# Titan_Servo_v1p01c_r.net
KiCad netlist of a schematic drawn in EAGLE
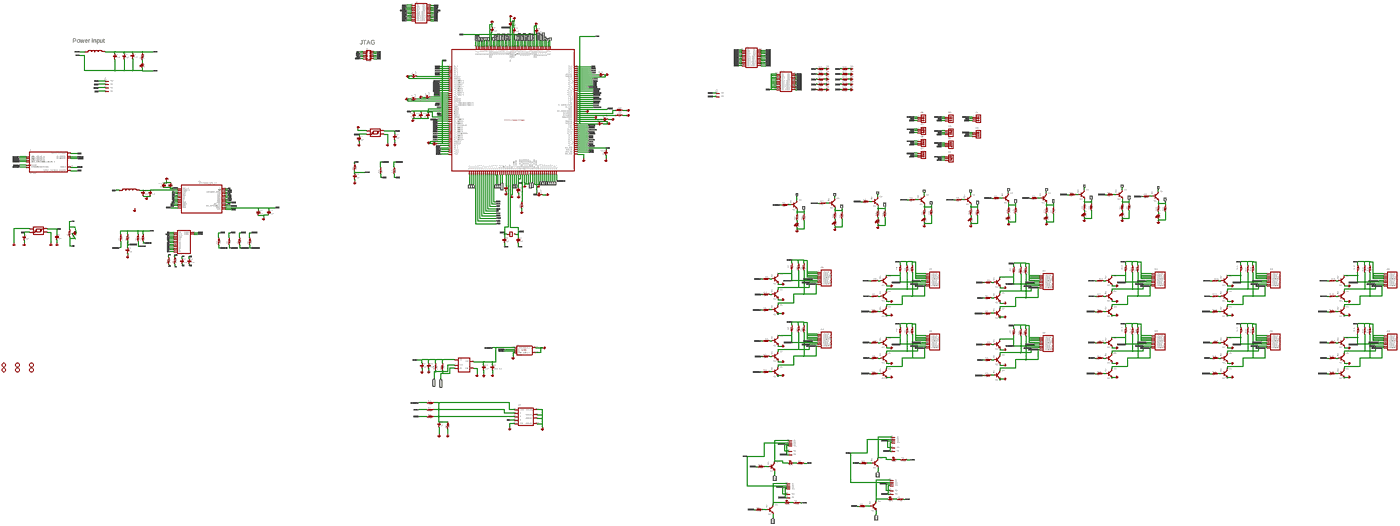
[diagram p0: schematic, sheet 1, overview]
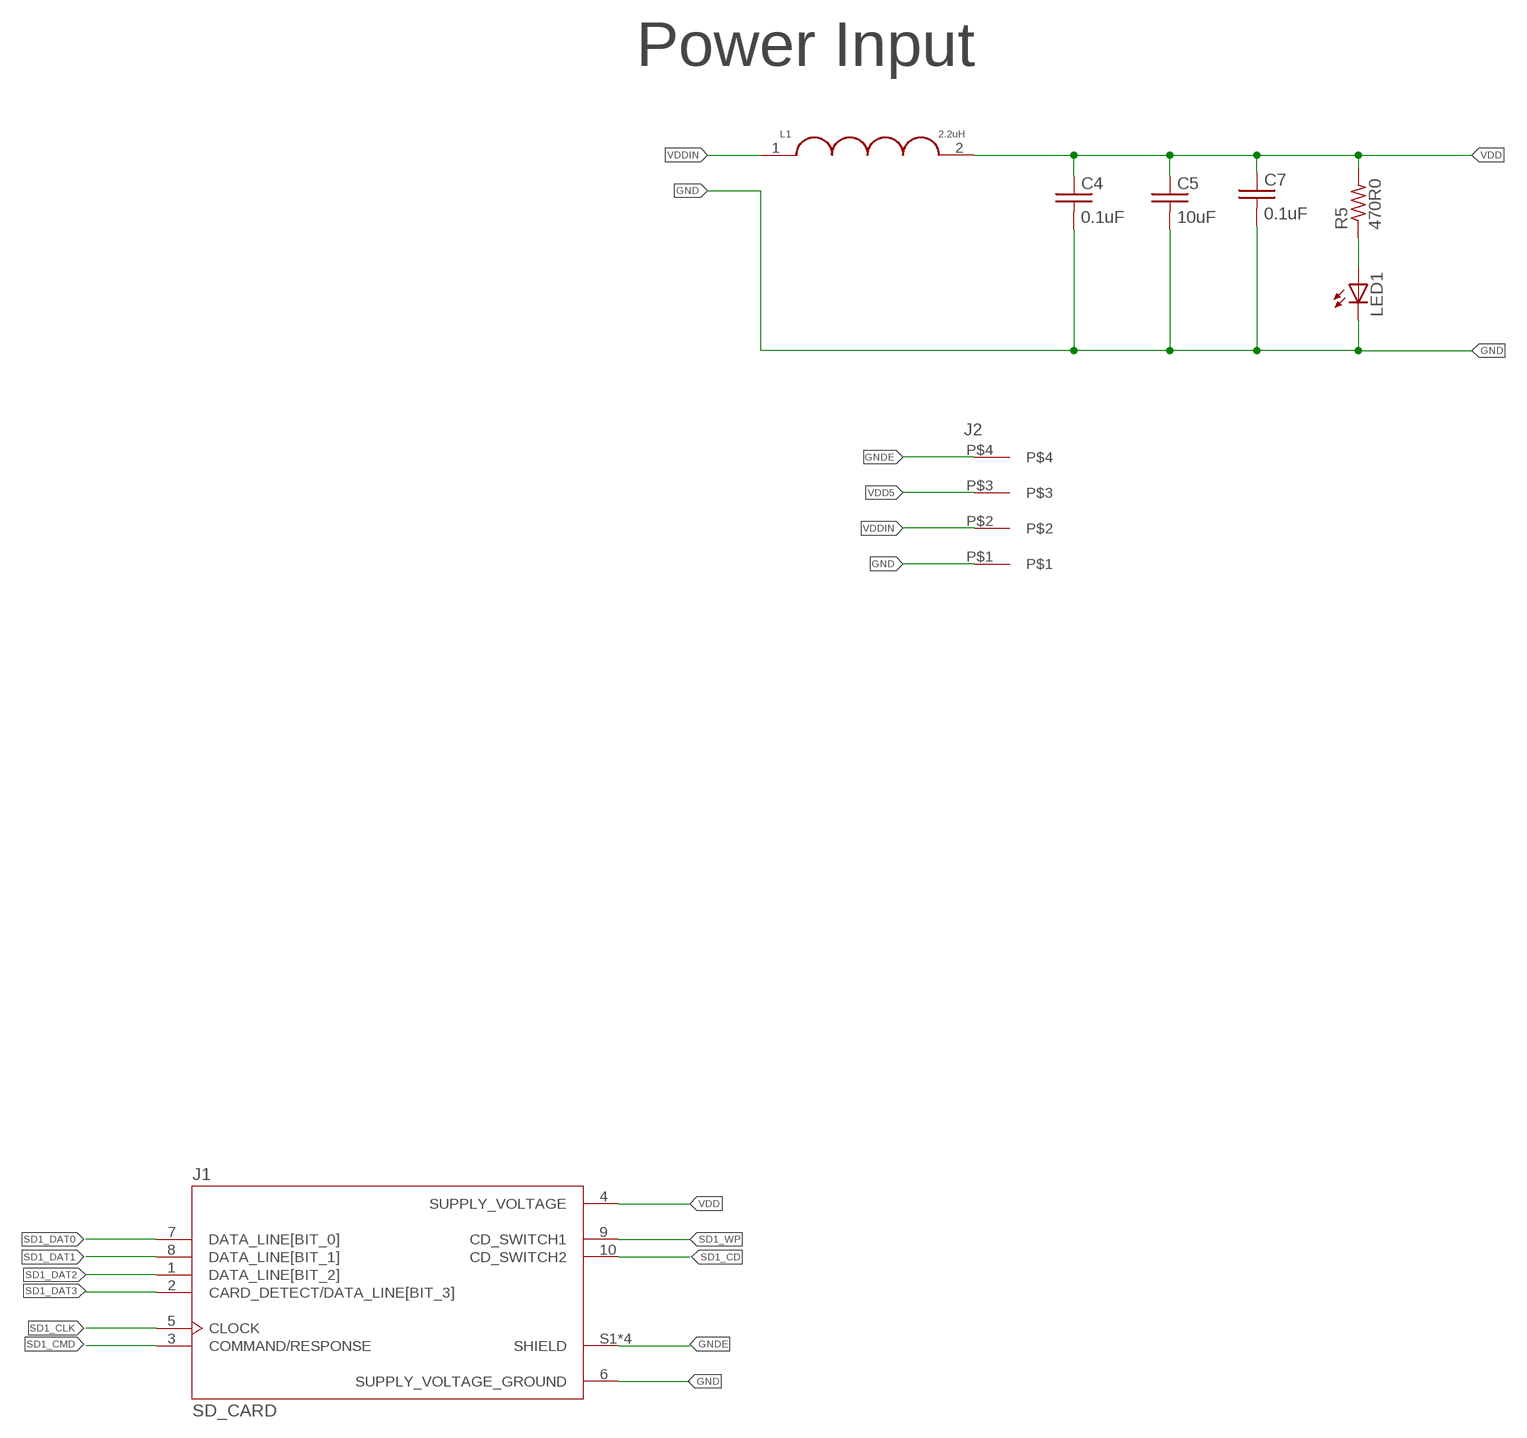
[diagram p1: schematic, sheet 1, part 1 of 9]
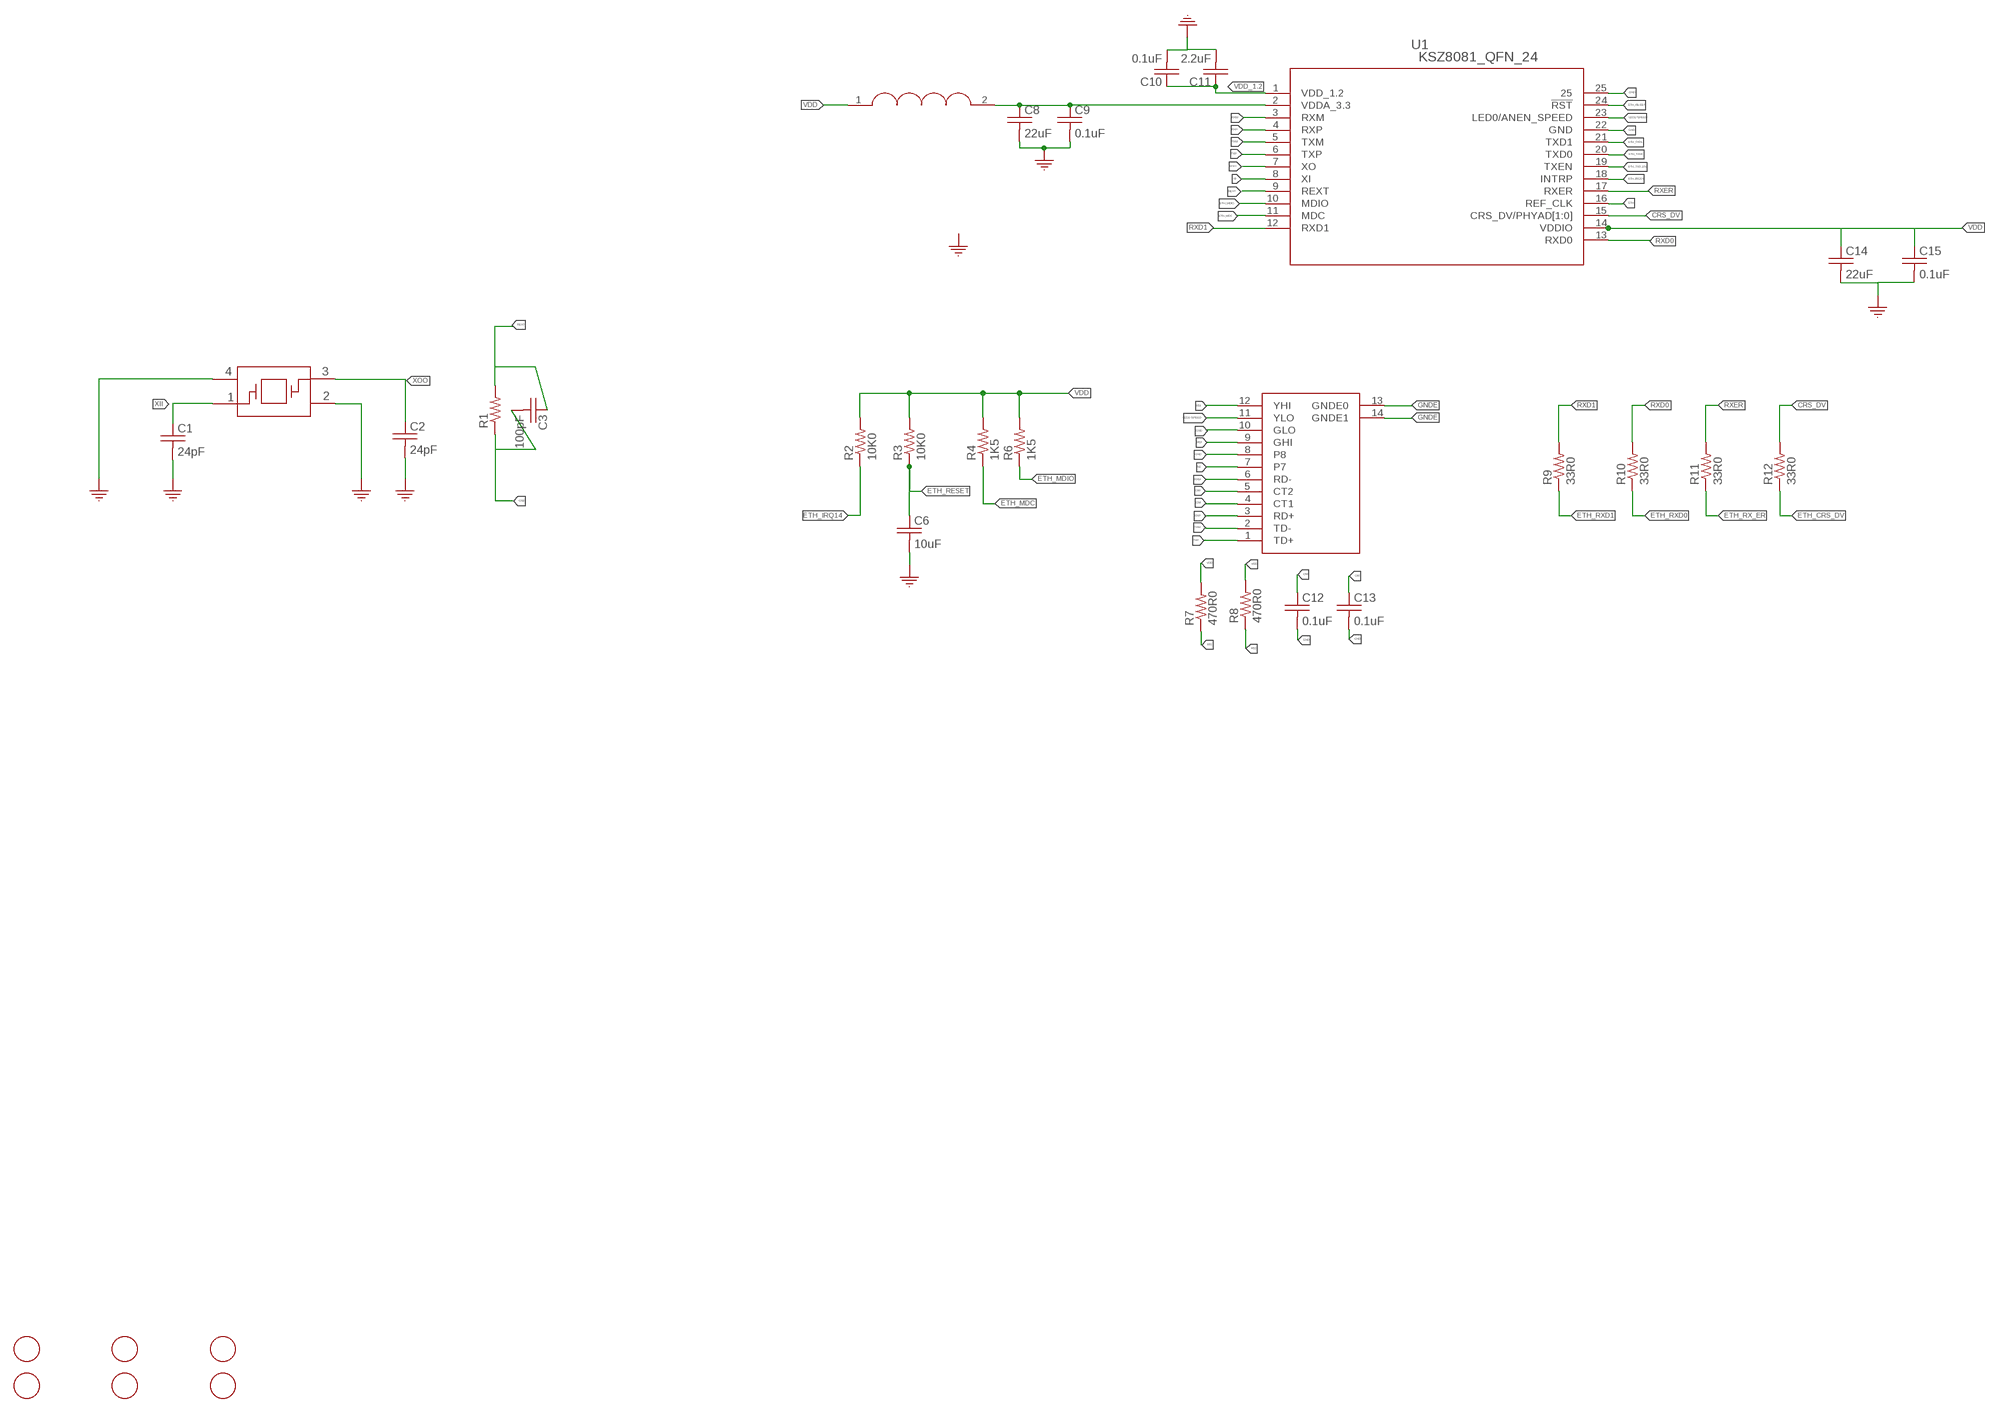
[diagram p2: schematic, sheet 1, part 2 of 9]
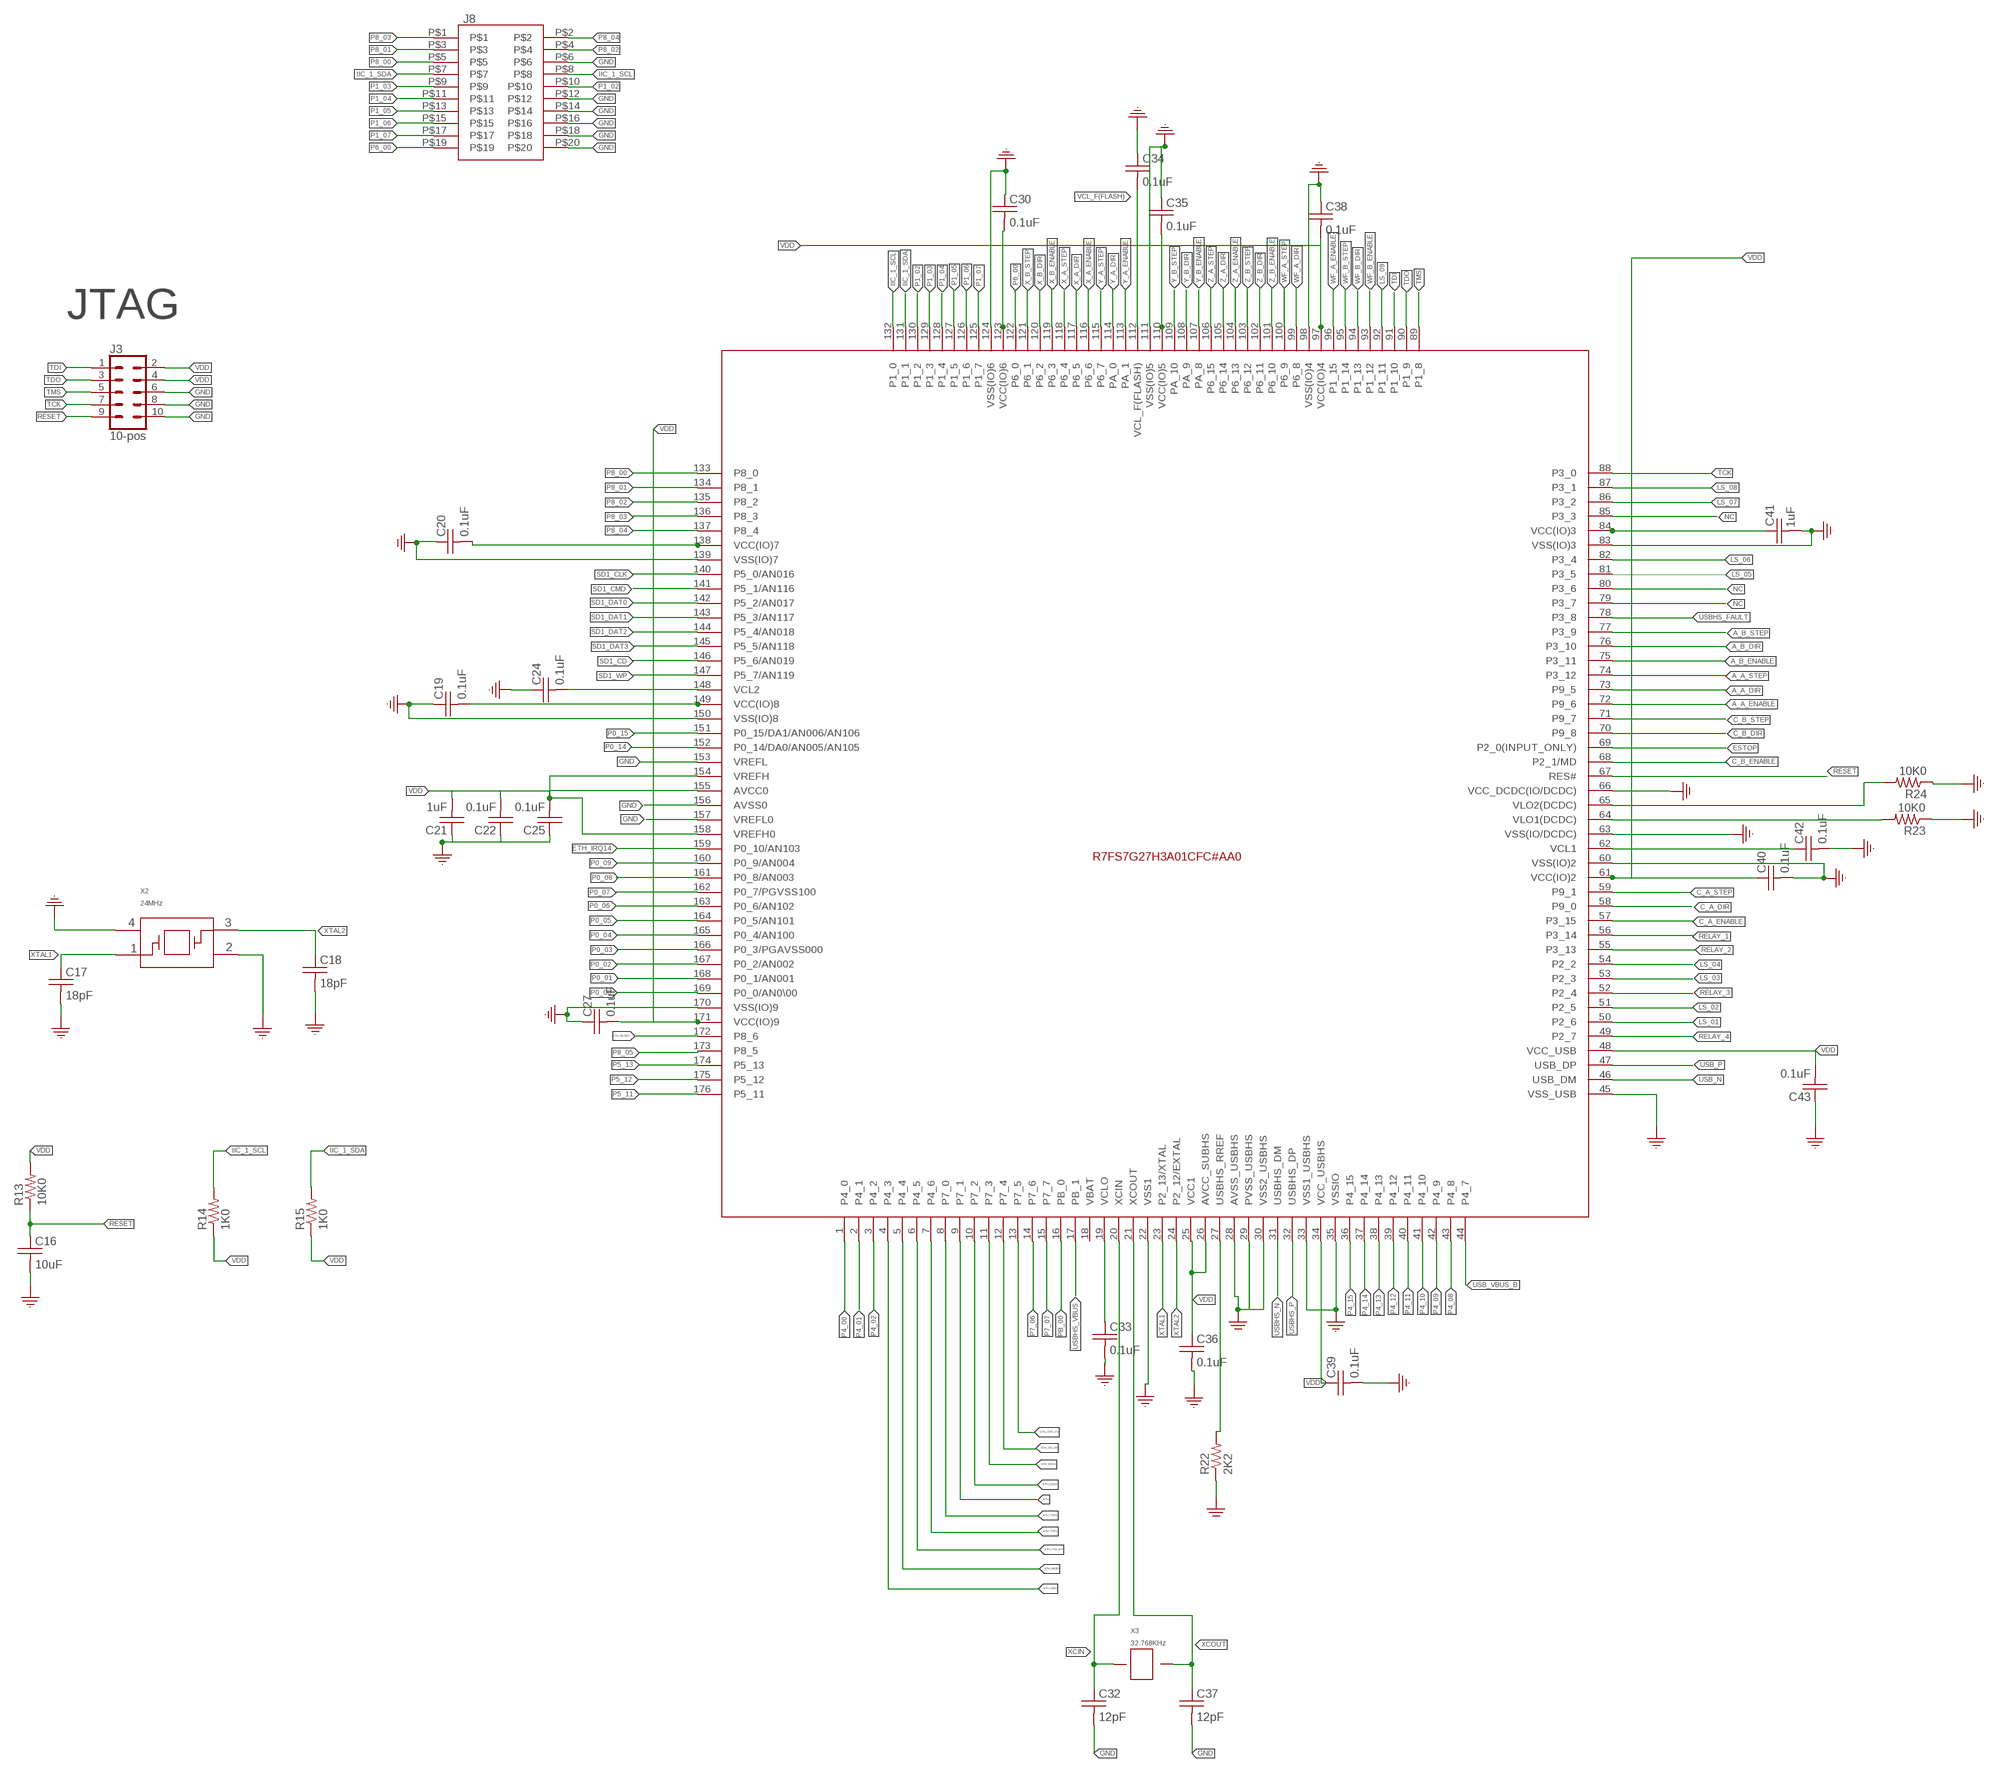
[diagram p3: schematic, sheet 1, part 3 of 9]
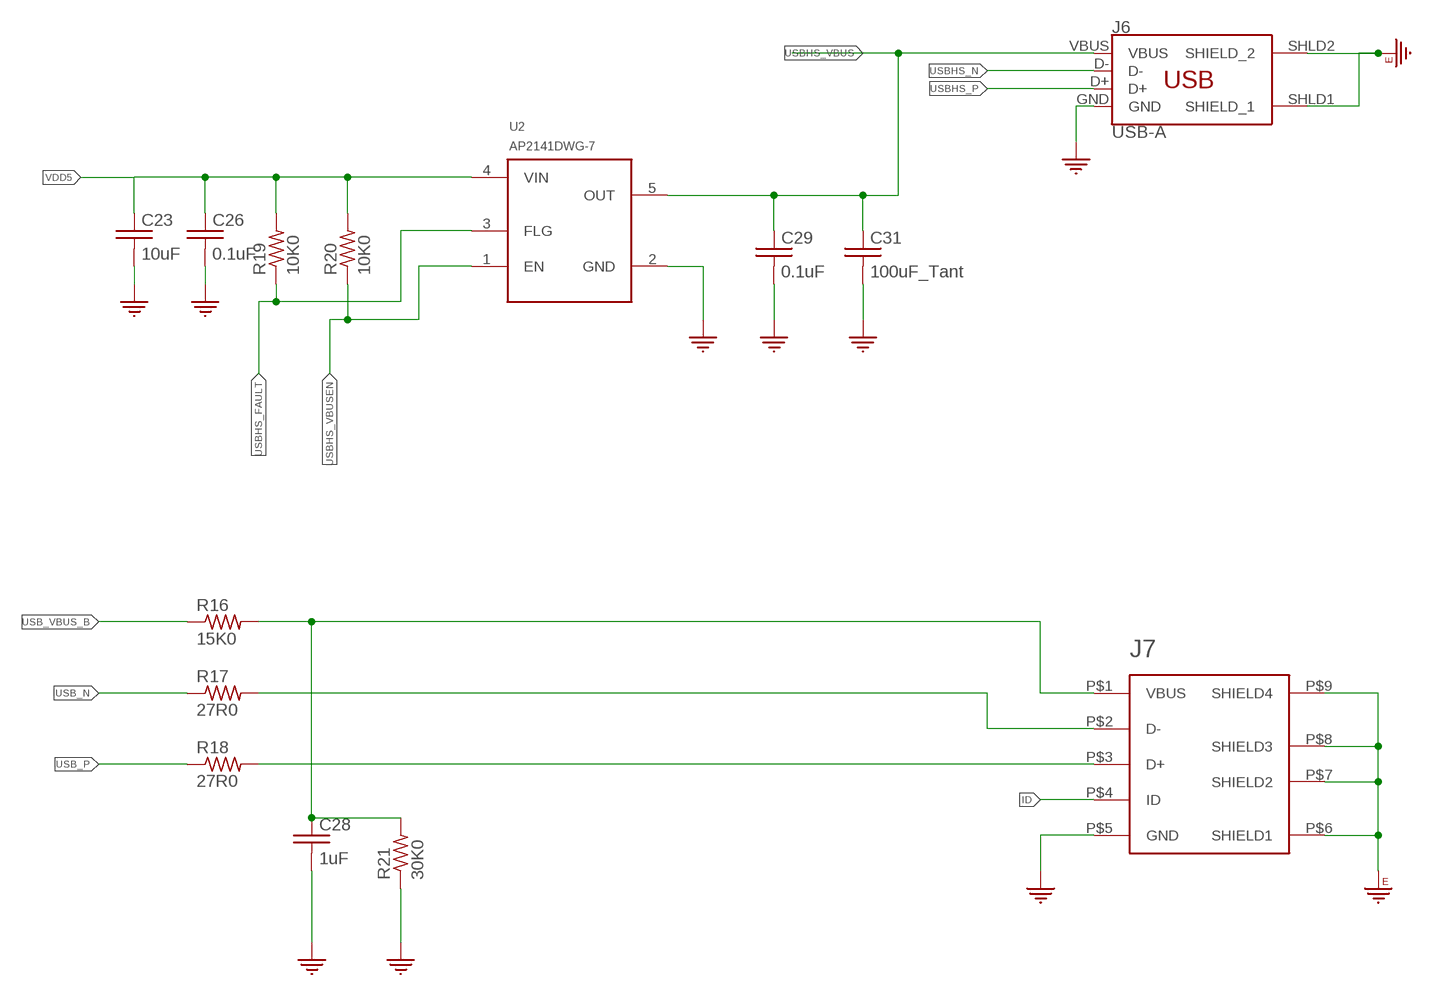
[diagram p4: schematic, sheet 1, part 4 of 9]
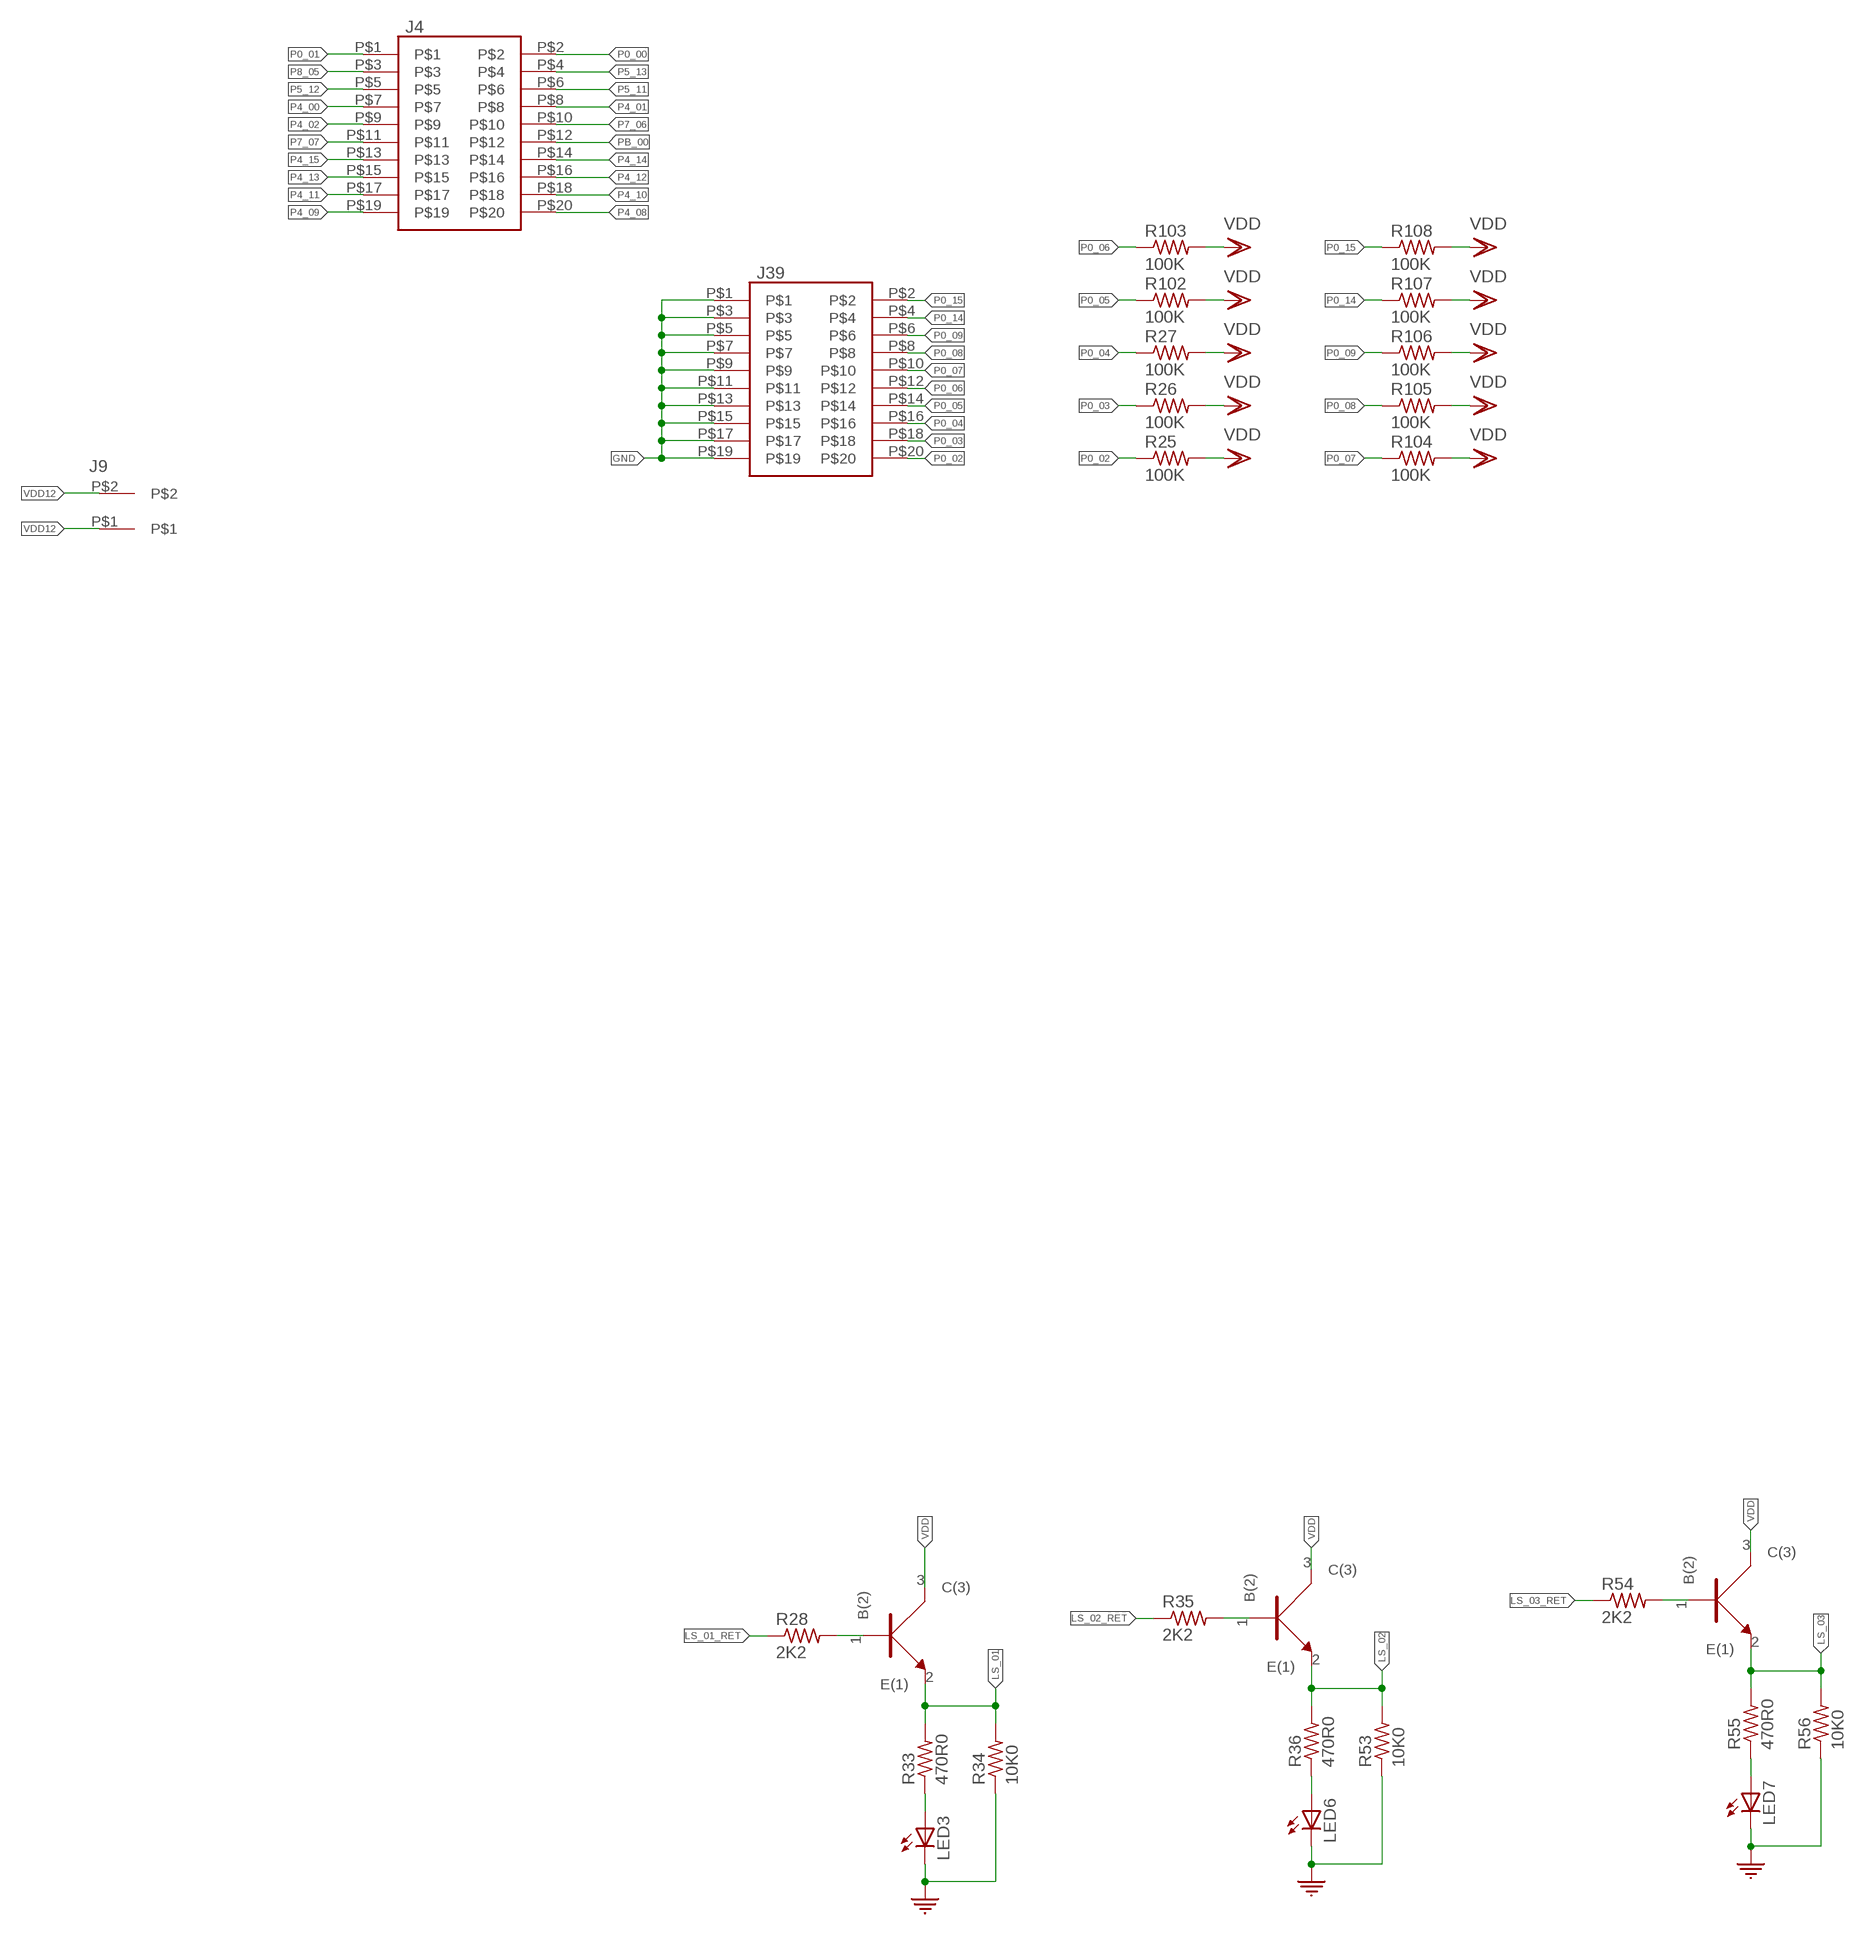
[diagram p5: schematic, sheet 1, part 5 of 9]
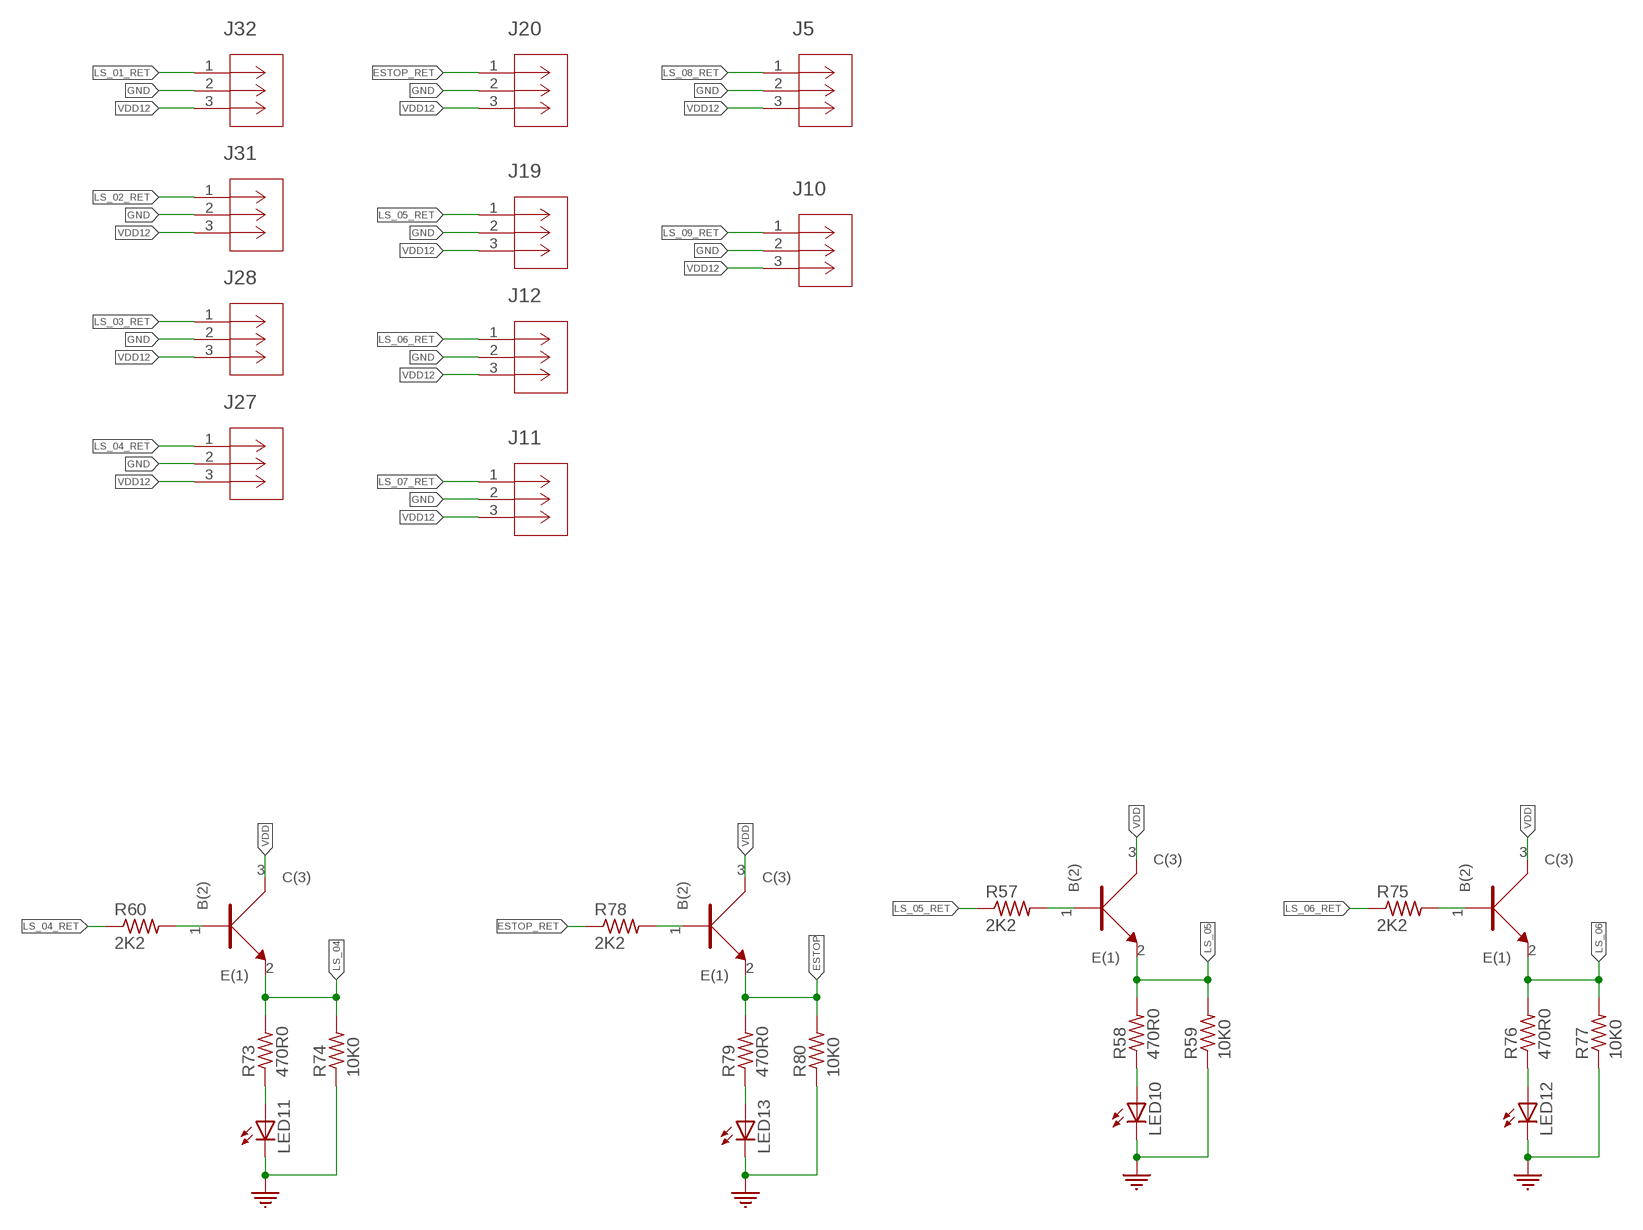
[diagram p6: schematic, sheet 1, part 6 of 9]
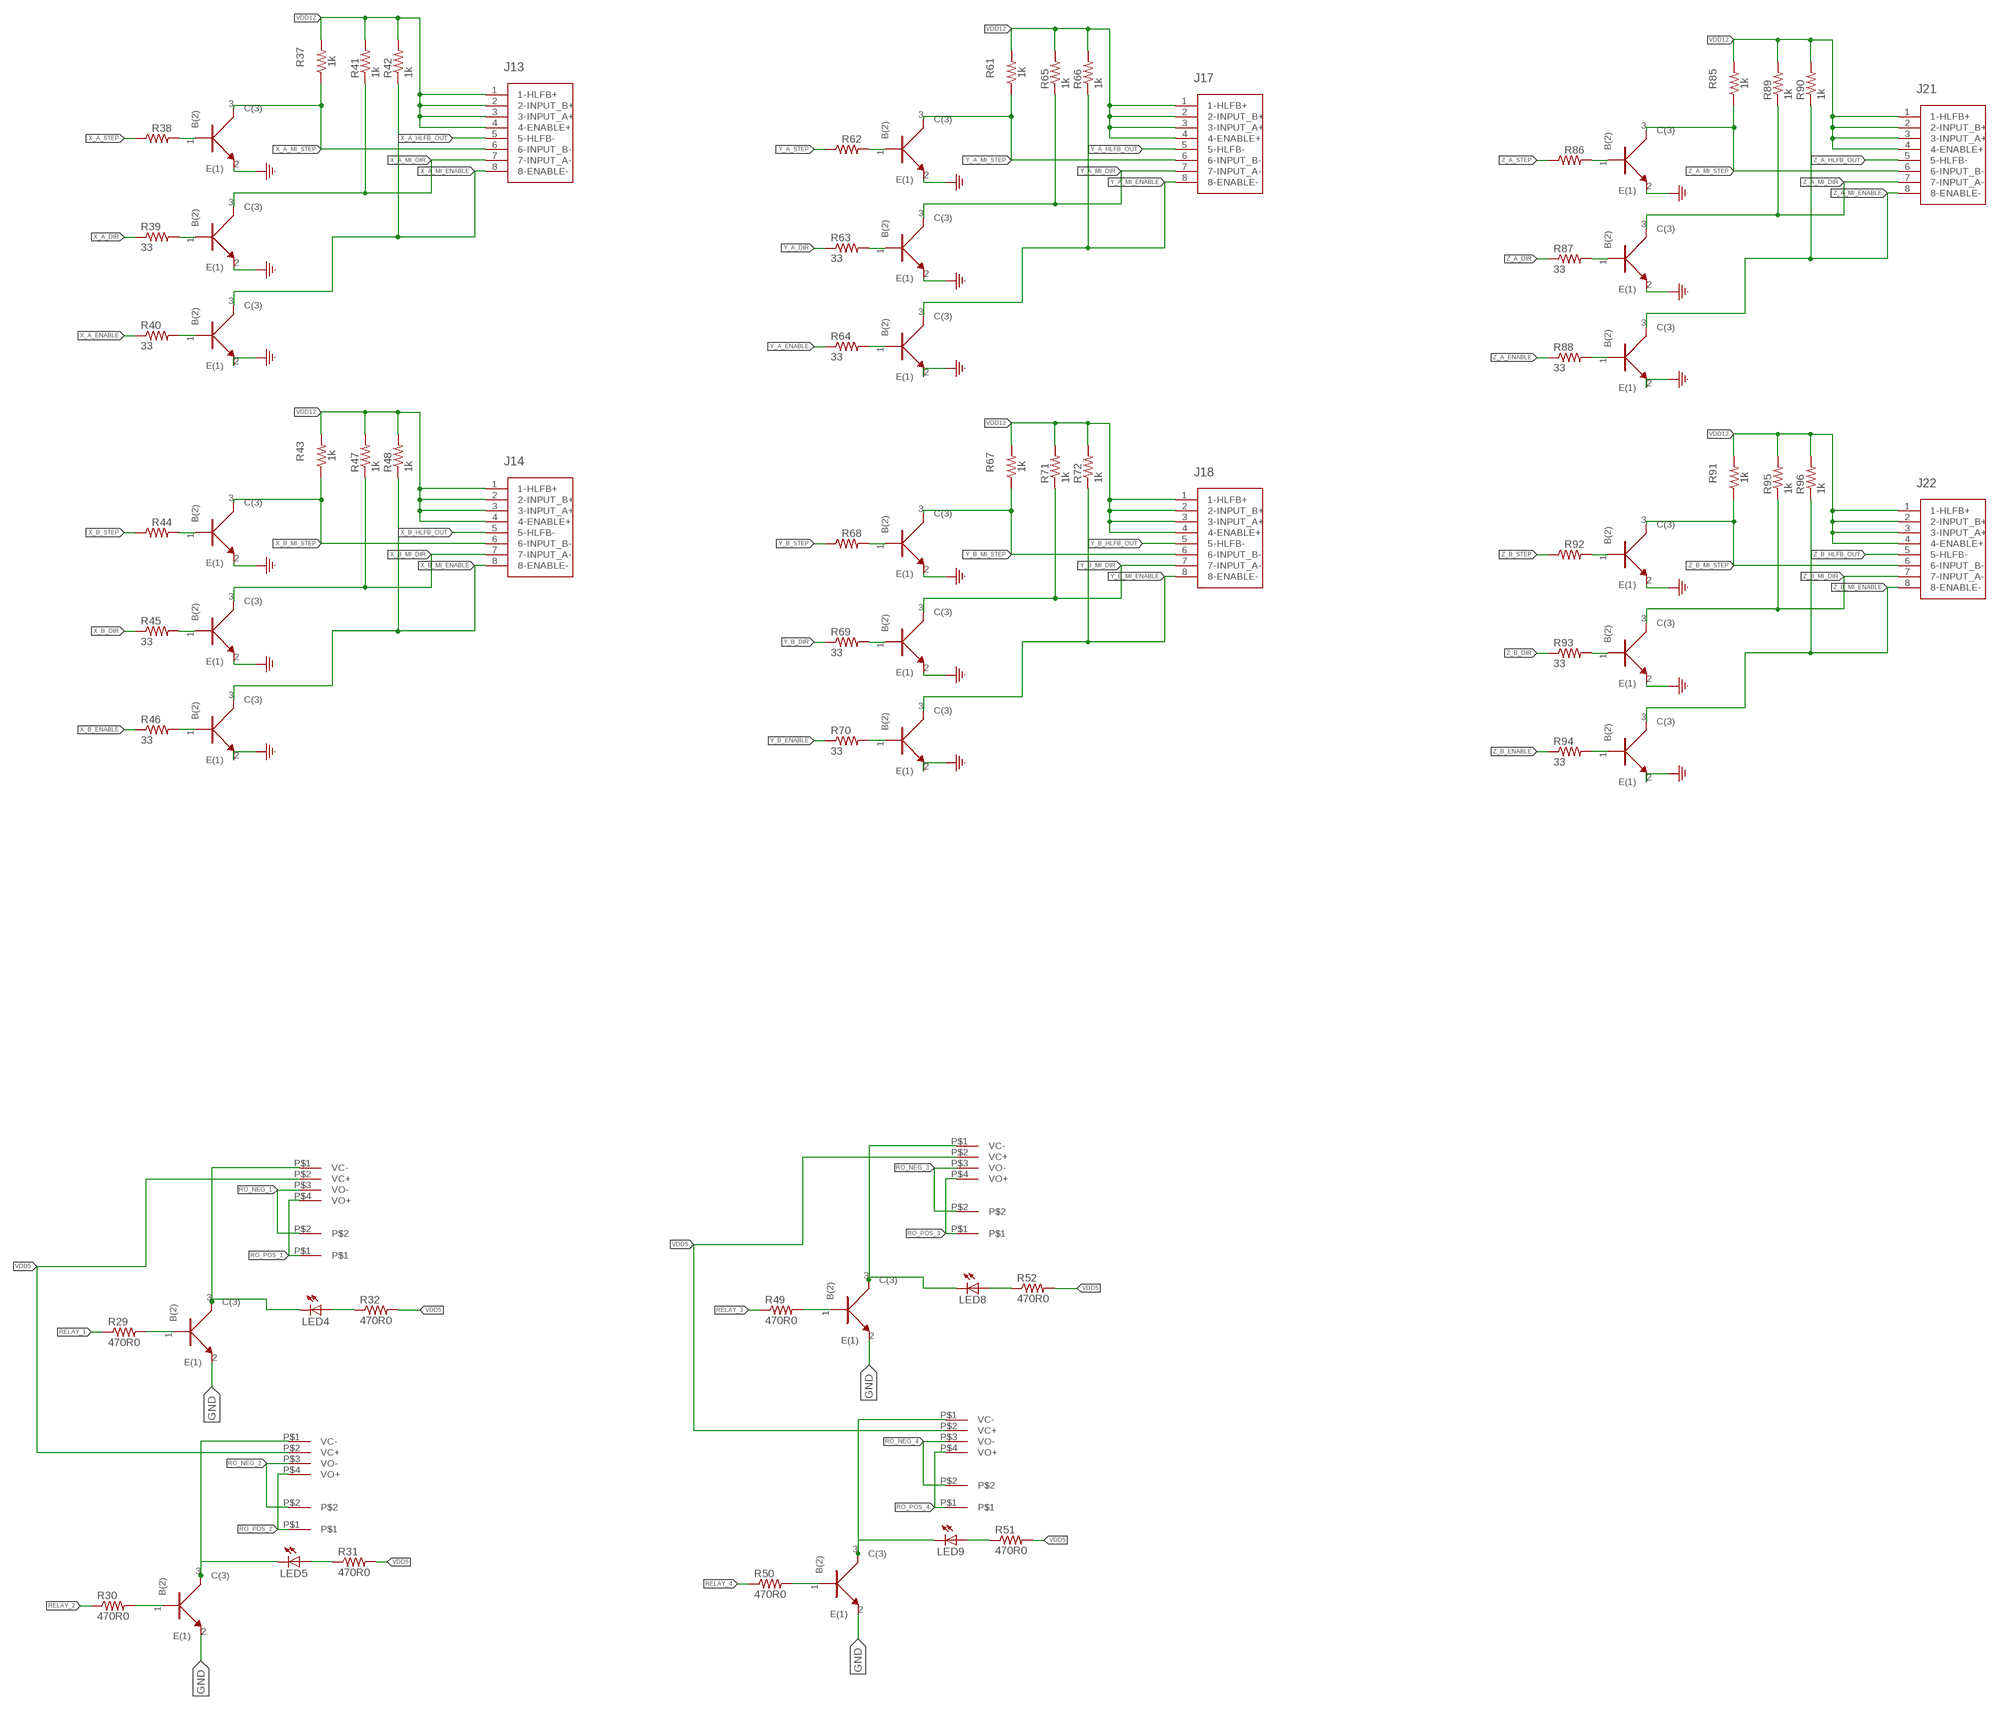
[diagram p7: schematic, sheet 1, part 7 of 9]
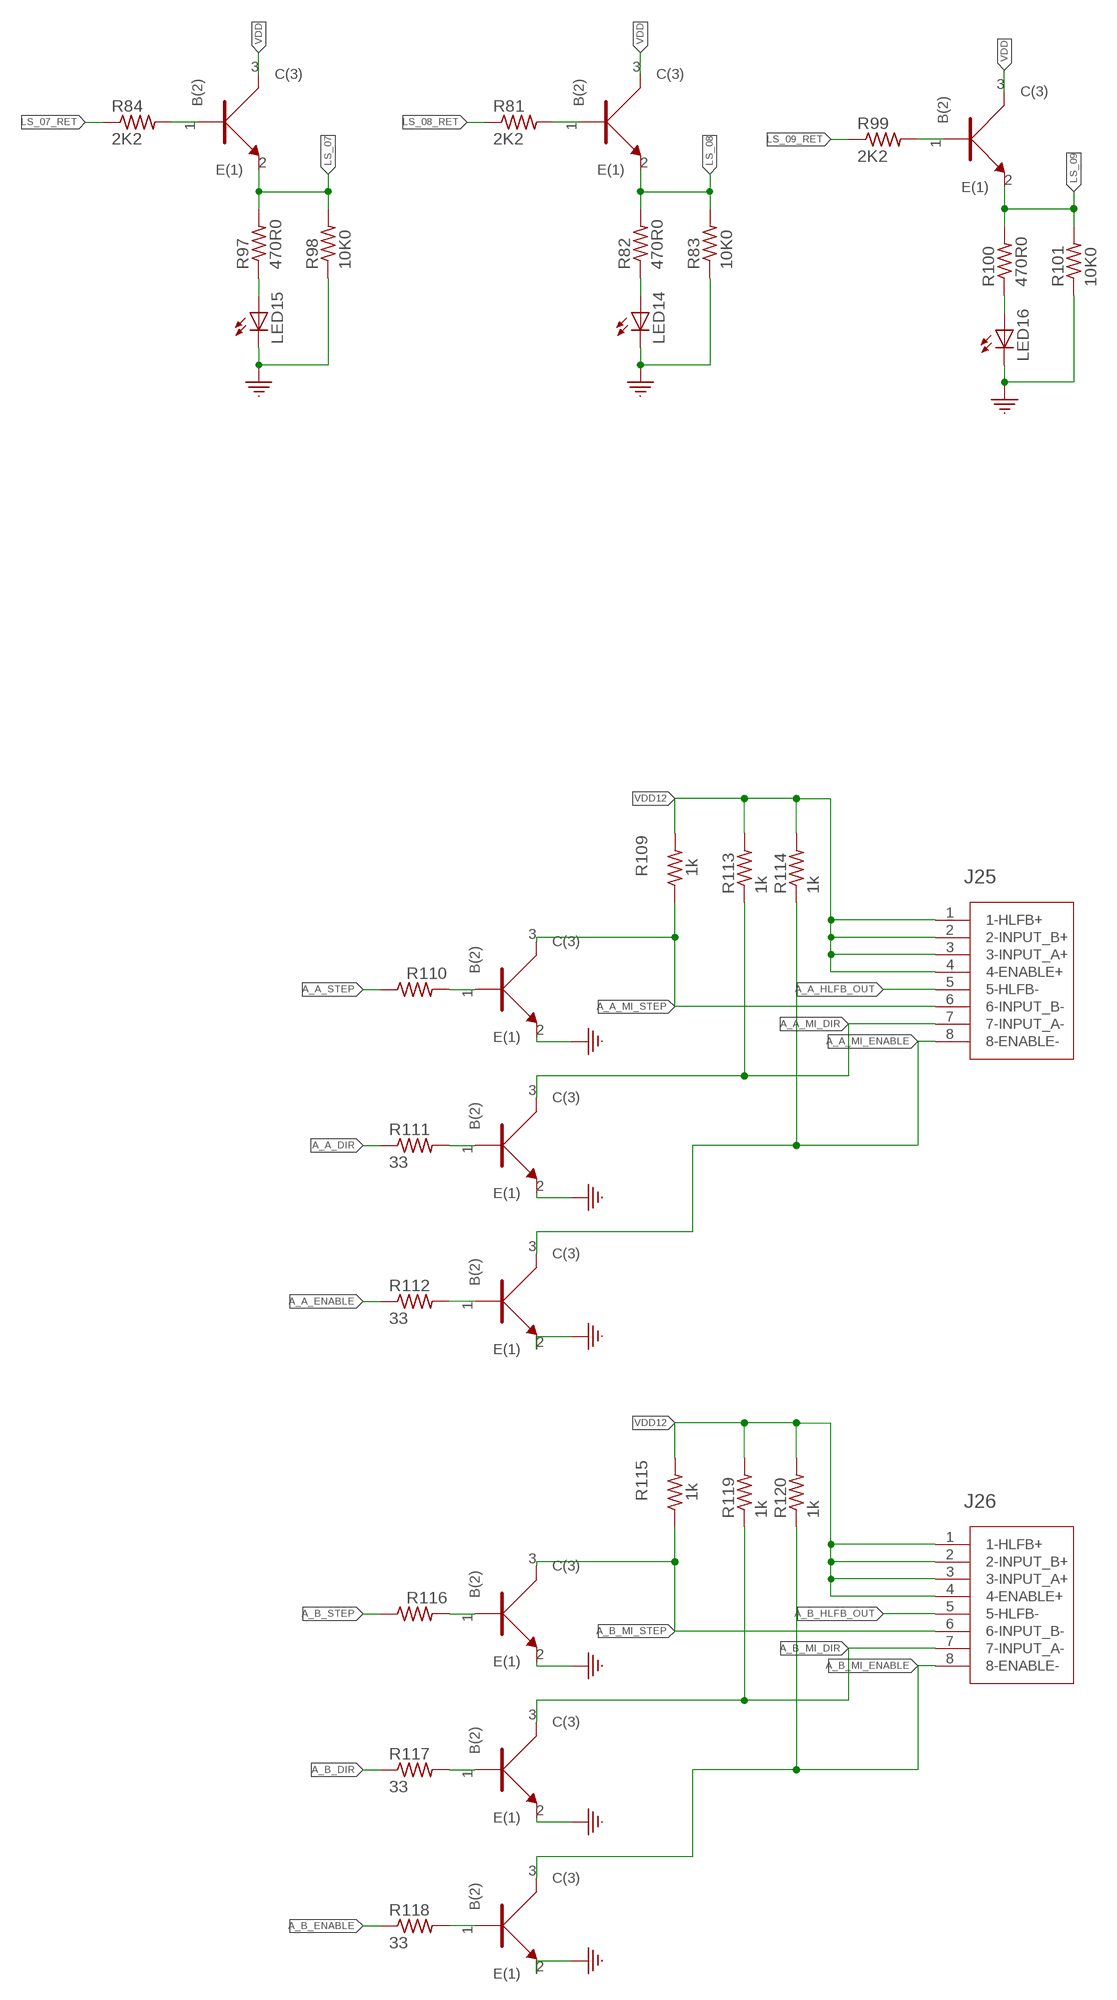
[diagram p8: schematic, sheet 1, part 8 of 9]
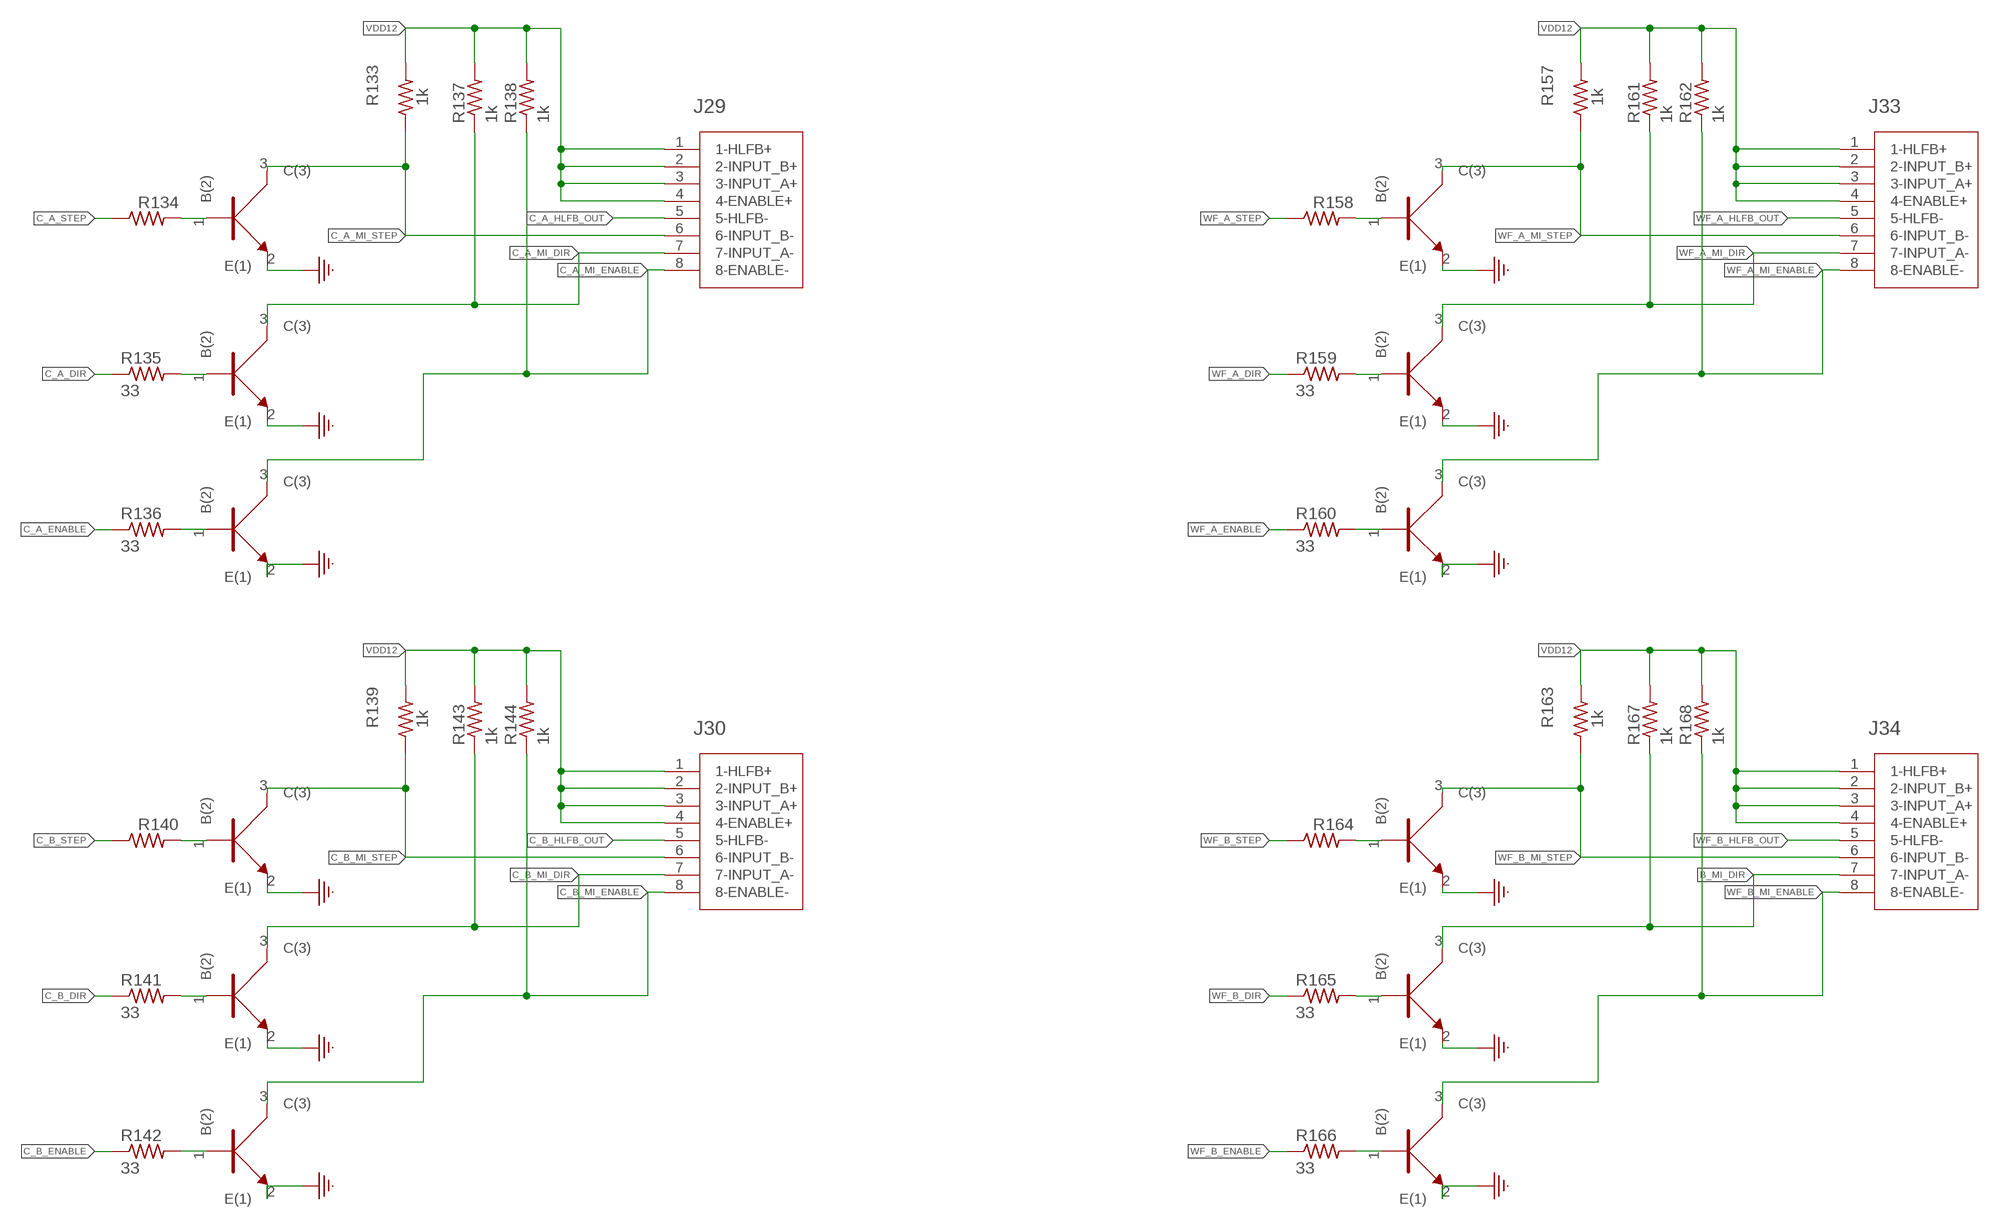
[diagram p9: schematic, sheet 1, part 9 of 9]

(export (version "E")
  (design (tool "Eeschema 10.0.6"))
  (components
    (comp (ref "AFID1")
      (value "FIDUCIAL_1MM")
      (footprint "eagle-import:FIDUCIAL_1MM")
      (libsource (lib "eagle-import") (part "FIDUCIAL_1MM"))
    )
    (comp (ref "AFID2")
      (value "FIDUCIAL_1MM")
      (footprint "eagle-import:FIDUCIAL_1MM")
      (libsource (lib "eagle-import") (part "FIDUCIAL_1MM"))
    )
    (comp (ref "AFID3")
      (value "FIDUCIAL_1MM")
      (footprint "eagle-import:FIDUCIAL_1MM")
      (libsource (lib "eagle-import") (part "FIDUCIAL_1MM"))
    )
    (comp (ref "AFID4")
      (value "FIDUCIAL_1MM")
      (footprint "eagle-import:FIDUCIAL_1MM")
      (libsource (lib "eagle-import") (part "FIDUCIAL_1MM"))
    )
    (comp (ref "AFID5")
      (value "FIDUCIAL_1MM")
      (footprint "eagle-import:FIDUCIAL_1MM")
      (libsource (lib "eagle-import") (part "FIDUCIAL_1MM"))
    )
    (comp (ref "AFID6")
      (value "FIDUCIAL_1MM")
      (footprint "eagle-import:FIDUCIAL_1MM")
      (libsource (lib "eagle-import") (part "FIDUCIAL_1MM"))
    )
    (comp (ref "C1")
      (value "24pF")
      (footprint "eagle-import:0402")
      (fields (field (name "PARTNO") "CC0402GRNPO9BN240"))
      (libsource (lib "eagle-import") (part "C_0402_24PF"))
    )
    (comp (ref "C2")
      (value "24pF")
      (footprint "eagle-import:0402")
      (fields (field (name "PARTNO") "CC0402GRNPO9BN240"))
      (libsource (lib "eagle-import") (part "C_0402_24PF"))
    )
    (comp (ref "C3")
      (value "100pF")
      (footprint "eagle-import:0402")
      (fields (field (name "PARTNO") "CL05C101JB5NNNC"))
      (libsource (lib "eagle-import") (part "C_0402_100PF"))
    )
    (comp (ref "C4")
      (value "0.1uF")
      (footprint "eagle-import:0402")
      (fields (field (name "PARTNO") "CL05F104ZO5NNNC"))
      (libsource (lib "eagle-import") (part "C_0402_0.1UF"))
    )
    (comp (ref "C5")
      (value "10uF")
      (footprint "eagle-import:0402")
      (fields (field (name "PARTNO") "CL05A106MP8NUB8"))
      (libsource (lib "eagle-import") (part "C_0402_10UF"))
    )
    (comp (ref "C6")
      (value "10uF")
      (footprint "eagle-import:0402")
      (fields (field (name "PARTNO") "CL05A106MP8NUB8"))
      (libsource (lib "eagle-import") (part "C_0402_10UF"))
    )
    (comp (ref "C7")
      (value "0.1uF")
      (footprint "eagle-import:0402")
      (fields (field (name "PARTNO") "CL05F104ZO5NNNC"))
      (libsource (lib "eagle-import") (part "C_0402_0.1UF"))
    )
    (comp (ref "C8")
      (value "22uF")
      (footprint "eagle-import:0402")
      (fields (field (name "PARTNO") "CL05A226MQ5N6J8"))
      (libsource (lib "eagle-import") (part "C_0402_22UF"))
    )
    (comp (ref "C9")
      (value "0.1uF")
      (footprint "eagle-import:0402")
      (fields (field (name "PARTNO") "CL05F104ZO5NNNC"))
      (libsource (lib "eagle-import") (part "C_0402_0.1UF"))
    )
    (comp (ref "C10")
      (value "0.1uF")
      (footprint "eagle-import:0402")
      (fields (field (name "PARTNO") "CL05F104ZO5NNNC"))
      (libsource (lib "eagle-import") (part "C_0402_0.1UF"))
    )
    (comp (ref "C11")
      (value "2.2uF")
      (footprint "eagle-import:0402")
      (fields (field (name "PARTNO") "GRM155C81C225ME15D"))
      (libsource (lib "eagle-import") (part "C_0402_2.2UF"))
    )
    (comp (ref "C12")
      (value "0.1uF")
      (footprint "eagle-import:0402")
      (fields (field (name "PARTNO") "CL05F104ZO5NNNC"))
      (libsource (lib "eagle-import") (part "C_0402_0.1UF"))
    )
    (comp (ref "C13")
      (value "0.1uF")
      (footprint "eagle-import:0402")
      (fields (field (name "PARTNO") "CL05F104ZO5NNNC"))
      (libsource (lib "eagle-import") (part "C_0402_0.1UF"))
    )
    (comp (ref "C14")
      (value "22uF")
      (footprint "eagle-import:0402")
      (fields (field (name "PARTNO") "CL05A226MQ5N6J8"))
      (libsource (lib "eagle-import") (part "C_0402_22UF"))
    )
    (comp (ref "C15")
      (value "0.1uF")
      (footprint "eagle-import:0402")
      (fields (field (name "PARTNO") "CL05F104ZO5NNNC"))
      (libsource (lib "eagle-import") (part "C_0402_0.1UF"))
    )
    (comp (ref "C16")
      (value "10uF")
      (footprint "eagle-import:0402")
      (fields (field (name "PARTNO") "CL05A106MP8NUB8"))
      (libsource (lib "eagle-import") (part "C_0402_10UF"))
    )
    (comp (ref "C17")
      (value "18pF")
      (footprint "eagle-import:0402")
      (fields (field (name "PARTNO") "UMK105CG180JV-F"))
      (libsource (lib "eagle-import") (part "C_0402_18PF"))
    )
    (comp (ref "C18")
      (value "18pF")
      (footprint "eagle-import:0402")
      (fields (field (name "PARTNO") "UMK105CG180JV-F"))
      (libsource (lib "eagle-import") (part "C_0402_18PF"))
    )
    (comp (ref "C19")
      (value "0.1uF")
      (footprint "eagle-import:0402")
      (fields (field (name "PARTNO") "CL05F104ZO5NNNC"))
      (libsource (lib "eagle-import") (part "C_0402_0.1UF"))
    )
    (comp (ref "C20")
      (value "0.1uF")
      (footprint "eagle-import:0402")
      (fields (field (name "PARTNO") "CL05F104ZO5NNNC"))
      (libsource (lib "eagle-import") (part "C_0402_0.1UF"))
    )
    (comp (ref "C21")
      (value "1uF")
      (footprint "eagle-import:0402")
      (fields (field (name "PARTNO") "CL05A105KO5NNNC"))
      (libsource (lib "eagle-import") (part "C_0402_1UF"))
    )
    (comp (ref "C22")
      (value "0.1uF")
      (footprint "eagle-import:0402")
      (fields (field (name "PARTNO") "CL05F104ZO5NNNC"))
      (libsource (lib "eagle-import") (part "C_0402_0.1UF"))
    )
    (comp (ref "C23")
      (value "10uF")
      (footprint "eagle-import:0402")
      (fields (field (name "PARTNO") "CL05A106MP8NUB8"))
      (libsource (lib "eagle-import") (part "C_0402_10UF"))
    )
    (comp (ref "C24")
      (value "0.1uF")
      (footprint "eagle-import:0402")
      (fields (field (name "PARTNO") "CL05F104ZO5NNNC"))
      (libsource (lib "eagle-import") (part "C_0402_0.1UF"))
    )
    (comp (ref "C25")
      (value "0.1uF")
      (footprint "eagle-import:0402")
      (fields (field (name "PARTNO") "CL05F104ZO5NNNC"))
      (libsource (lib "eagle-import") (part "C_0402_0.1UF"))
    )
    (comp (ref "C26")
      (value "0.1uF")
      (footprint "eagle-import:0402")
      (fields (field (name "PARTNO") "CL05F104ZO5NNNC"))
      (libsource (lib "eagle-import") (part "C_0402_0.1UF"))
    )
    (comp (ref "C27")
      (value "0.1uF")
      (footprint "eagle-import:0402")
      (fields (field (name "PARTNO") "CL05F104ZO5NNNC"))
      (libsource (lib "eagle-import") (part "C_0402_0.1UF"))
    )
    (comp (ref "C28")
      (value "1uF")
      (footprint "eagle-import:0402")
      (fields (field (name "PARTNO") "CL05A105KO5NNNC"))
      (libsource (lib "eagle-import") (part "C_0402_1UF"))
    )
    (comp (ref "C29")
      (value "0.1uF")
      (footprint "eagle-import:0402")
      (fields (field (name "PARTNO") "CL05F104ZO5NNNC"))
      (libsource (lib "eagle-import") (part "C_0402_0.1UF"))
    )
    (comp (ref "C30")
      (value "0.1uF")
      (footprint "eagle-import:0402")
      (fields (field (name "PARTNO") "CL05F104ZO5NNNC"))
      (libsource (lib "eagle-import") (part "C_0402_0.1UF"))
    )
    (comp (ref "C31")
      (value "100uF_Tant")
      (footprint "eagle-import:C1210")
      (fields (field (name "PARTNO") "TLJT107M010R0900"))
      (libsource (lib "eagle-import") (part "C_1210_100UF_TANT"))
    )
    (comp (ref "C32")
      (value "12pF")
      (footprint "eagle-import:0402")
      (fields (field (name "PARTNO") "CL05C120JB5NNNC"))
      (libsource (lib "eagle-import") (part "C_0402_12PF"))
    )
    (comp (ref "C33")
      (value "0.1uF")
      (footprint "eagle-import:0402")
      (fields (field (name "PARTNO") "CL05F104ZO5NNNC"))
      (libsource (lib "eagle-import") (part "C_0402_0.1UF"))
    )
    (comp (ref "C34")
      (value "0.1uF")
      (footprint "eagle-import:0402")
      (fields (field (name "PARTNO") "CL05F104ZO5NNNC"))
      (libsource (lib "eagle-import") (part "C_0402_0.1UF"))
    )
    (comp (ref "C35")
      (value "0.1uF")
      (footprint "eagle-import:0402")
      (fields (field (name "PARTNO") "CL05F104ZO5NNNC"))
      (libsource (lib "eagle-import") (part "C_0402_0.1UF"))
    )
    (comp (ref "C36")
      (value "0.1uF")
      (footprint "eagle-import:0402")
      (fields (field (name "PARTNO") "CL05F104ZO5NNNC"))
      (libsource (lib "eagle-import") (part "C_0402_0.1UF"))
    )
    (comp (ref "C37")
      (value "12pF")
      (footprint "eagle-import:0402")
      (fields (field (name "PARTNO") "CL05C120JB5NNNC"))
      (libsource (lib "eagle-import") (part "C_0402_12PF"))
    )
    (comp (ref "C38")
      (value "0.1uF")
      (footprint "eagle-import:0402")
      (fields (field (name "PARTNO") "CL05F104ZO5NNNC"))
      (libsource (lib "eagle-import") (part "C_0402_0.1UF"))
    )
    (comp (ref "C39")
      (value "0.1uF")
      (footprint "eagle-import:0402")
      (fields (field (name "PARTNO") "CL05F104ZO5NNNC"))
      (libsource (lib "eagle-import") (part "C_0402_0.1UF"))
    )
    (comp (ref "C40")
      (value "0.1uF")
      (footprint "eagle-import:0402")
      (fields (field (name "PARTNO") "CL05F104ZO5NNNC"))
      (libsource (lib "eagle-import") (part "C_0402_0.1UF"))
    )
    (comp (ref "C41")
      (value "1uF")
      (footprint "eagle-import:0402")
      (fields (field (name "PARTNO") "CL05A105KO5NNNC"))
      (libsource (lib "eagle-import") (part "C_0402_1UF"))
    )
    (comp (ref "C42")
      (value "0.1uF")
      (footprint "eagle-import:0402")
      (fields (field (name "PARTNO") "CL05F104ZO5NNNC"))
      (libsource (lib "eagle-import") (part "C_0402_0.1UF"))
    )
    (comp (ref "C43")
      (value "0.1uF")
      (footprint "eagle-import:0402")
      (fields (field (name "PARTNO") "CL05F104ZO5NNNC"))
      (libsource (lib "eagle-import") (part "C_0402_0.1UF"))
    )
    (comp (ref "FB1")
      (value "FB2_603")
      (footprint "eagle-import:0603")
      (fields (field (name "PARTNO") "BLM18PG121SN1D"))
      (libsource (lib "eagle-import") (part "FB_0603_120_OHM0603"))
    )
    (comp (ref "J1")
      (value "SD_CARD")
      (footprint "eagle-import:SD_CARD")
      (fields (field (name "MF") "Amphenol ICC") (field (name "PARTNO") "114-00841-68"))
      (libsource (lib "eagle-import") (part "SD_CARD_1140084168"))
    )
    (comp (ref "J2")
      (value "4-pos")
      (footprint "eagle-import:1X4_3.81MM_PITCH")
      (fields (field (name "PARTNO") "691322310004"))
      (libsource (lib "eagle-import") (part "3.81MM_1_X_4_RT_ANGLE_PLUG_HEADER"))
    )
    (comp (ref "J3")
      (value "10-pos")
      (footprint "eagle-import:2X5")
      (fields (field (name "PARTNO") "PH2RA-10-UA"))
      (libsource (lib "eagle-import") (part "CONN_05X2_RAPTH"))
    )
    (comp (ref "J4")
      (value "20-pos")
      (footprint "eagle-import:2_X_10_.1_INCH")
      (fields (field (name "PARTNO") "67996-420HLF"))
      (libsource (lib "eagle-import") (part "2_X_10_HEADER_GENERIC"))
    )
    (comp (ref "J5")
      (value "CONN_530470310_PICOBLADE_X_3")
      (footprint "eagle-import:CON_530470310_MOL")
      (fields
        (field (name "MANUFACTURER_PART_NUMBER") "530470310")
        (field (name "COPYRIGHT") "Copyright (C) 2022 Ultra Librarian. All rights reserved.")
      )
      (libsource (lib "eagle-import") (part "CONN_530470310_PICOBLADE_X_3"))
    )
    (comp (ref "J6")
      (value "USB-A")
      (footprint "eagle-import:USB_A_SMT")
      (fields (field (name "PARTNO") "87583-3010RPALF"))
      (libsource (lib "eagle-import") (part "USB_A"))
    )
    (comp (ref "J7")
      (value "USB-B-Micro")
      (footprint "eagle-import:USB_MICRO-B")
      (fields (field (name "PARTNO") "10118192-0002LF"))
      (libsource (lib "eagle-import") (part "USB_MICRO-B"))
    )
    (comp (ref "J8")
      (value "2_X_10_HEADER_GENERIC")
      (footprint "eagle-import:2_X_10_.1_INCH")
      (fields (field (name "PARTNO") "67996-420HLF"))
      (libsource (lib "eagle-import") (part "2_X_10_HEADER_GENERIC"))
    )
    (comp (ref "J9")
      (value "2-pos")
      (footprint "eagle-import:2_3.81MM_PITCH")
      (fields (field (name "PARTNO") "691322310002"))
      (libsource (lib "eagle-import") (part "3.81MM_1_X_2_RT_ANGLE_PLUG_HEADER"))
    )
    (comp (ref "J10")
      (value "CONN_530470310_PICOBLADE_X_3")
      (footprint "eagle-import:CON_530470310_MOL")
      (fields
        (field (name "MANUFACTURER_PART_NUMBER") "530470310")
        (field (name "COPYRIGHT") "Copyright (C) 2022 Ultra Librarian. All rights reserved.")
      )
      (libsource (lib "eagle-import") (part "CONN_530470310_PICOBLADE_X_3"))
    )
    (comp (ref "J11")
      (value "CONN_530470310_PICOBLADE_X_3")
      (footprint "eagle-import:CON_530470310_MOL")
      (fields
        (field (name "MANUFACTURER_PART_NUMBER") "530470310")
        (field (name "COPYRIGHT") "Copyright (C) 2022 Ultra Librarian. All rights reserved.")
      )
      (libsource (lib "eagle-import") (part "CONN_530470310_PICOBLADE_X_3"))
    )
    (comp (ref "J12")
      (value "CONN_530470310_PICOBLADE_X_3")
      (footprint "eagle-import:CON_530470310_MOL")
      (fields
        (field (name "MANUFACTURER_PART_NUMBER") "530470310")
        (field (name "COPYRIGHT") "Copyright (C) 2022 Ultra Librarian. All rights reserved.")
      )
      (libsource (lib "eagle-import") (part "CONN_530470310_PICOBLADE_X_3"))
    )
    (comp (ref "J13")
      (value "TEKNIC_MOTOR_8PIN")
      (footprint "eagle-import:CON_39281083")
      (fields
        (field (name "MANUFACTURER_PART_NUMBER") "39281083")
        (field (name "COPYRIGHT") "Copyright (C) 2022 Ultra Librarian. All rights reserved.")
      )
      (libsource (lib "eagle-import") (part "TEKNIC_MOTOR_8PIN"))
    )
    (comp (ref "J14")
      (value "TEKNIC_MOTOR_8PIN")
      (footprint "eagle-import:CON_39281083")
      (fields
        (field (name "MANUFACTURER_PART_NUMBER") "39281083")
        (field (name "COPYRIGHT") "Copyright (C) 2022 Ultra Librarian. All rights reserved.")
      )
      (libsource (lib "eagle-import") (part "TEKNIC_MOTOR_8PIN"))
    )
    (comp (ref "J15")
      (value "2-pos")
      (footprint "eagle-import:2_3.81MM_PITCH")
      (fields (field (name "PARTNO") "691322310002"))
      (libsource (lib "eagle-import") (part "3.81MM_1_X_2_RT_ANGLE_PLUG_HEADER"))
    )
    (comp (ref "J16")
      (value "2-pos")
      (footprint "eagle-import:2_3.81MM_PITCH")
      (fields (field (name "PARTNO") "691322310002"))
      (libsource (lib "eagle-import") (part "3.81MM_1_X_2_RT_ANGLE_PLUG_HEADER"))
    )
    (comp (ref "J17")
      (value "TEKNIC_MOTOR_8PIN")
      (footprint "eagle-import:CON_39281083")
      (fields
        (field (name "MANUFACTURER_PART_NUMBER") "39281083")
        (field (name "COPYRIGHT") "Copyright (C) 2022 Ultra Librarian. All rights reserved.")
      )
      (libsource (lib "eagle-import") (part "TEKNIC_MOTOR_8PIN"))
    )
    (comp (ref "J18")
      (value "TEKNIC_MOTOR_8PIN")
      (footprint "eagle-import:CON_39281083")
      (fields
        (field (name "MANUFACTURER_PART_NUMBER") "39281083")
        (field (name "COPYRIGHT") "Copyright (C) 2022 Ultra Librarian. All rights reserved.")
      )
      (libsource (lib "eagle-import") (part "TEKNIC_MOTOR_8PIN"))
    )
    (comp (ref "J19")
      (value "CONN_530470310_PICOBLADE_X_3")
      (footprint "eagle-import:CON_530470310_MOL")
      (fields
        (field (name "MANUFACTURER_PART_NUMBER") "530470310")
        (field (name "COPYRIGHT") "Copyright (C) 2022 Ultra Librarian. All rights reserved.")
      )
      (libsource (lib "eagle-import") (part "CONN_530470310_PICOBLADE_X_3"))
    )
    (comp (ref "J20")
      (value "CONN_530470310_PICOBLADE_X_3")
      (footprint "eagle-import:CON_530470310_MOL")
      (fields
        (field (name "MANUFACTURER_PART_NUMBER") "530470310")
        (field (name "COPYRIGHT") "Copyright (C) 2022 Ultra Librarian. All rights reserved.")
      )
      (libsource (lib "eagle-import") (part "CONN_530470310_PICOBLADE_X_3"))
    )
    (comp (ref "J21")
      (value "TEKNIC_MOTOR_8PIN")
      (footprint "eagle-import:CON_39281083")
      (fields
        (field (name "MANUFACTURER_PART_NUMBER") "39281083")
        (field (name "COPYRIGHT") "Copyright (C) 2022 Ultra Librarian. All rights reserved.")
      )
      (libsource (lib "eagle-import") (part "TEKNIC_MOTOR_8PIN"))
    )
    (comp (ref "J22")
      (value "TEKNIC_MOTOR_8PIN")
      (footprint "eagle-import:CON_39281083")
      (fields
        (field (name "MANUFACTURER_PART_NUMBER") "39281083")
        (field (name "COPYRIGHT") "Copyright (C) 2022 Ultra Librarian. All rights reserved.")
      )
      (libsource (lib "eagle-import") (part "TEKNIC_MOTOR_8PIN"))
    )
    (comp (ref "J23")
      (value "2-pos")
      (footprint "eagle-import:2_3.81MM_PITCH")
      (fields (field (name "PARTNO") "691322310002"))
      (libsource (lib "eagle-import") (part "3.81MM_1_X_2_RT_ANGLE_PLUG_HEADER"))
    )
    (comp (ref "J24")
      (value "2-pos")
      (footprint "eagle-import:2_3.81MM_PITCH")
      (fields (field (name "PARTNO") "691322310002"))
      (libsource (lib "eagle-import") (part "3.81MM_1_X_2_RT_ANGLE_PLUG_HEADER"))
    )
    (comp (ref "J25")
      (value "TEKNIC_MOTOR_8PIN")
      (footprint "eagle-import:CON_39281083")
      (fields
        (field (name "MANUFACTURER_PART_NUMBER") "39281083")
        (field (name "COPYRIGHT") "Copyright (C) 2022 Ultra Librarian. All rights reserved.")
      )
      (libsource (lib "eagle-import") (part "TEKNIC_MOTOR_8PIN"))
    )
    (comp (ref "J26")
      (value "TEKNIC_MOTOR_8PIN")
      (footprint "eagle-import:CON_39281083")
      (fields
        (field (name "MANUFACTURER_PART_NUMBER") "39281083")
        (field (name "COPYRIGHT") "Copyright (C) 2022 Ultra Librarian. All rights reserved.")
      )
      (libsource (lib "eagle-import") (part "TEKNIC_MOTOR_8PIN"))
    )
    (comp (ref "J27")
      (value "CONN_530470310_PICOBLADE_X_3")
      (footprint "eagle-import:CON_530470310_MOL")
      (fields
        (field (name "MANUFACTURER_PART_NUMBER") "530470310")
        (field (name "COPYRIGHT") "Copyright (C) 2022 Ultra Librarian. All rights reserved.")
      )
      (libsource (lib "eagle-import") (part "CONN_530470310_PICOBLADE_X_3"))
    )
    (comp (ref "J28")
      (value "CONN_530470310_PICOBLADE_X_3")
      (footprint "eagle-import:CON_530470310_MOL")
      (fields
        (field (name "MANUFACTURER_PART_NUMBER") "530470310")
        (field (name "COPYRIGHT") "Copyright (C) 2022 Ultra Librarian. All rights reserved.")
      )
      (libsource (lib "eagle-import") (part "CONN_530470310_PICOBLADE_X_3"))
    )
    (comp (ref "J29")
      (value "TEKNIC_MOTOR_8PIN")
      (footprint "eagle-import:CON_39281083")
      (fields
        (field (name "MANUFACTURER_PART_NUMBER") "39281083")
        (field (name "COPYRIGHT") "Copyright (C) 2022 Ultra Librarian. All rights reserved.")
      )
      (libsource (lib "eagle-import") (part "TEKNIC_MOTOR_8PIN"))
    )
    (comp (ref "J30")
      (value "TEKNIC_MOTOR_8PIN")
      (footprint "eagle-import:CON_39281083")
      (fields
        (field (name "MANUFACTURER_PART_NUMBER") "39281083")
        (field (name "COPYRIGHT") "Copyright (C) 2022 Ultra Librarian. All rights reserved.")
      )
      (libsource (lib "eagle-import") (part "TEKNIC_MOTOR_8PIN"))
    )
    (comp (ref "J31")
      (value "CONN_530470310_PICOBLADE_X_3")
      (footprint "eagle-import:CON_530470310_MOL")
      (fields
        (field (name "MANUFACTURER_PART_NUMBER") "530470310")
        (field (name "COPYRIGHT") "Copyright (C) 2022 Ultra Librarian. All rights reserved.")
      )
      (libsource (lib "eagle-import") (part "CONN_530470310_PICOBLADE_X_3"))
    )
    (comp (ref "J32")
      (value "CONN_530470310_PICOBLADE_X_3")
      (footprint "eagle-import:CON_530470310_MOL")
      (fields
        (field (name "MANUFACTURER_PART_NUMBER") "530470310")
        (field (name "COPYRIGHT") "Copyright (C) 2022 Ultra Librarian. All rights reserved.")
      )
      (libsource (lib "eagle-import") (part "CONN_530470310_PICOBLADE_X_3"))
    )
    (comp (ref "J33")
      (value "TEKNIC_MOTOR_8PIN")
      (footprint "eagle-import:CON_39281083")
      (fields
        (field (name "MANUFACTURER_PART_NUMBER") "39281083")
        (field (name "COPYRIGHT") "Copyright (C) 2022 Ultra Librarian. All rights reserved.")
      )
      (libsource (lib "eagle-import") (part "TEKNIC_MOTOR_8PIN"))
    )
    (comp (ref "J34")
      (value "TEKNIC_MOTOR_8PIN")
      (footprint "eagle-import:CON_39281083")
      (fields
        (field (name "MANUFACTURER_PART_NUMBER") "39281083")
        (field (name "COPYRIGHT") "Copyright (C) 2022 Ultra Librarian. All rights reserved.")
      )
      (libsource (lib "eagle-import") (part "TEKNIC_MOTOR_8PIN"))
    )
    (comp (ref "J39")
      (value "2_X_10_HEADER_GENERIC")
      (footprint "eagle-import:2_X_10_.1_INCH")
      (fields (field (name "PARTNO") "67996-420HLF"))
      (libsource (lib "eagle-import") (part "2_X_10_HEADER_GENERIC"))
    )
    (comp (ref "L1")
      (value "2.2uH")
      (footprint "eagle-import:1008")
      (fields (field (name "PARTNO") "LQM2HPN2R2MG0L"))
      (libsource (lib "eagle-import") (part "INDUCTOR_1008_2.2_MH_1.3A"))
    )
    (comp (ref "LED1")
      (value "Green")
      (footprint "eagle-import:0805")
      (fields (field (name "PARTNO") "LG R971-KN-1"))
      (libsource (lib "eagle-import") (part "LED_0805_GREEN"))
    )
    (comp (ref "LED3")
      (value "Green")
      (footprint "eagle-import:0805")
      (fields (field (name "PARTNO") "LG R971-KN-1"))
      (libsource (lib "eagle-import") (part "LED_0805_GREEN"))
    )
    (comp (ref "LED4")
      (value "Green")
      (footprint "eagle-import:0805")
      (fields (field (name "PARTNO") "LG R971-KN-1"))
      (libsource (lib "eagle-import") (part "LED_0805_GREEN"))
    )
    (comp (ref "LED5")
      (value "Green")
      (footprint "eagle-import:0805")
      (fields (field (name "PARTNO") "LG R971-KN-1"))
      (libsource (lib "eagle-import") (part "LED_0805_GREEN"))
    )
    (comp (ref "LED6")
      (value "Green")
      (footprint "eagle-import:0805")
      (fields (field (name "PARTNO") "LG R971-KN-1"))
      (libsource (lib "eagle-import") (part "LED_0805_GREEN"))
    )
    (comp (ref "LED7")
      (value "Green")
      (footprint "eagle-import:0805")
      (fields (field (name "PARTNO") "LG R971-KN-1"))
      (libsource (lib "eagle-import") (part "LED_0805_GREEN"))
    )
    (comp (ref "LED8")
      (value "Green")
      (footprint "eagle-import:0805")
      (fields (field (name "PARTNO") "LG R971-KN-1"))
      (libsource (lib "eagle-import") (part "LED_0805_GREEN"))
    )
    (comp (ref "LED9")
      (value "Green")
      (footprint "eagle-import:0805")
      (fields (field (name "PARTNO") "LG R971-KN-1"))
      (libsource (lib "eagle-import") (part "LED_0805_GREEN"))
    )
    (comp (ref "LED10")
      (value "Green")
      (footprint "eagle-import:0805")
      (fields (field (name "PARTNO") "LG R971-KN-1"))
      (libsource (lib "eagle-import") (part "LED_0805_GREEN"))
    )
    (comp (ref "LED11")
      (value "Green")
      (footprint "eagle-import:0805")
      (fields (field (name "PARTNO") "LG R971-KN-1"))
      (libsource (lib "eagle-import") (part "LED_0805_GREEN"))
    )
    (comp (ref "LED12")
      (value "Green")
      (footprint "eagle-import:0805")
      (fields (field (name "PARTNO") "LG R971-KN-1"))
      (libsource (lib "eagle-import") (part "LED_0805_GREEN"))
    )
    (comp (ref "LED13")
      (value "Green")
      (footprint "eagle-import:0805")
      (fields (field (name "PARTNO") "LG R971-KN-1"))
      (libsource (lib "eagle-import") (part "LED_0805_GREEN"))
    )
    (comp (ref "LED14")
      (value "Green")
      (footprint "eagle-import:0805")
      (fields (field (name "PARTNO") "LG R971-KN-1"))
      (libsource (lib "eagle-import") (part "LED_0805_GREEN"))
    )
    (comp (ref "LED15")
      (value "Green")
      (footprint "eagle-import:0805")
      (fields (field (name "PARTNO") "LG R971-KN-1"))
      (libsource (lib "eagle-import") (part "LED_0805_GREEN"))
    )
    (comp (ref "LED16")
      (value "Green")
      (footprint "eagle-import:0805")
      (fields (field (name "PARTNO") "LG R971-KN-1"))
      (libsource (lib "eagle-import") (part "LED_0805_GREEN"))
    )
    (comp (ref "R1")
      (value "6K49")
      (footprint "eagle-import:0402")
      (fields (field (name "PARTNO") "RMCF0402FT6K49"))
      (libsource (lib "eagle-import") (part "R_0402_6K49"))
    )
    (comp (ref "R2")
      (value "10K0")
      (footprint "eagle-import:0402")
      (fields (field (name "PARTNO") "RMCF0402JT10K0"))
      (libsource (lib "eagle-import") (part "R_0402_10K0"))
    )
    (comp (ref "R3")
      (value "10K0")
      (footprint "eagle-import:0402")
      (fields (field (name "PARTNO") "RMCF0402JT10K0"))
      (libsource (lib "eagle-import") (part "R_0402_10K0"))
    )
    (comp (ref "R4")
      (value "1K5")
      (footprint "eagle-import:0402")
      (fields (field (name "PARTNO") "RMCF0402JT1K50"))
      (libsource (lib "eagle-import") (part "R_0402_1K5"))
    )
    (comp (ref "R5")
      (value "470R0")
      (footprint "eagle-import:0402")
      (fields (field (name "PARTNO") "RMCF0402JT470R"))
      (libsource (lib "eagle-import") (part "R_0402_470R0"))
    )
    (comp (ref "R6")
      (value "1K5")
      (footprint "eagle-import:0402")
      (fields (field (name "PARTNO") "RMCF0402JT1K50"))
      (libsource (lib "eagle-import") (part "R_0402_1K5"))
    )
    (comp (ref "R7")
      (value "470R0")
      (footprint "eagle-import:0402")
      (fields (field (name "PARTNO") "RMCF0402JT470R"))
      (libsource (lib "eagle-import") (part "R_0402_470R0"))
    )
    (comp (ref "R8")
      (value "470R0")
      (footprint "eagle-import:0402")
      (fields (field (name "PARTNO") "RMCF0402JT470R"))
      (libsource (lib "eagle-import") (part "R_0402_470R0"))
    )
    (comp (ref "R9")
      (value "33R0")
      (footprint "eagle-import:0402")
      (fields (field (name "PARTNO") "RMCF0402JT33R0"))
      (libsource (lib "eagle-import") (part "R_0402_33R0"))
    )
    (comp (ref "R10")
      (value "33R0")
      (footprint "eagle-import:0402")
      (fields (field (name "PARTNO") "RMCF0402JT33R0"))
      (libsource (lib "eagle-import") (part "R_0402_33R0"))
    )
    (comp (ref "R11")
      (value "33R0")
      (footprint "eagle-import:0402")
      (fields (field (name "PARTNO") "RMCF0402JT33R0"))
      (libsource (lib "eagle-import") (part "R_0402_33R0"))
    )
    (comp (ref "R12")
      (value "33R0")
      (footprint "eagle-import:0402")
      (fields (field (name "PARTNO") "RMCF0402JT33R0"))
      (libsource (lib "eagle-import") (part "R_0402_33R0"))
    )
    (comp (ref "R13")
      (value "10K0")
      (footprint "eagle-import:0402")
      (fields (field (name "PARTNO") "RMCF0402JT10K0"))
      (libsource (lib "eagle-import") (part "R_0402_10K0"))
    )
    (comp (ref "R14")
      (value "1K0")
      (footprint "eagle-import:0402")
      (fields (field (name "PARTNO") "CRG0402J1K0"))
      (libsource (lib "eagle-import") (part "R_0402_1K0"))
    )
    (comp (ref "R15")
      (value "1K0")
      (footprint "eagle-import:0402")
      (fields (field (name "PARTNO") "CRG0402J1K0"))
      (libsource (lib "eagle-import") (part "R_0402_1K0"))
    )
    (comp (ref "R16")
      (value "15K0")
      (footprint "eagle-import:0402")
      (fields (field (name "PARTNO") "RMCF0402JT15K0"))
      (libsource (lib "eagle-import") (part "R_0402_15K0"))
    )
    (comp (ref "R17")
      (value "27R0")
      (footprint "eagle-import:0402")
      (fields (field (name "PARTNO") "RMCF0402JT27R0"))
      (libsource (lib "eagle-import") (part "R_0402_27R0"))
    )
    (comp (ref "R18")
      (value "27R0")
      (footprint "eagle-import:0402")
      (fields (field (name "PARTNO") "RMCF0402JT27R0"))
      (libsource (lib "eagle-import") (part "R_0402_27R0"))
    )
    (comp (ref "R19")
      (value "10K0")
      (footprint "eagle-import:0402")
      (fields (field (name "PARTNO") "RMCF0402JT10K0"))
      (libsource (lib "eagle-import") (part "R_0402_10K0"))
    )
    (comp (ref "R20")
      (value "10K0")
      (footprint "eagle-import:0402")
      (fields (field (name "PARTNO") "RMCF0402JT10K0"))
      (libsource (lib "eagle-import") (part "R_0402_10K0"))
    )
    (comp (ref "R21")
      (value "30K0")
      (footprint "eagle-import:0402")
      (fields (field (name "PARTNO") "RC0402JR-0730KL"))
      (libsource (lib "eagle-import") (part "R_0402_30K0"))
    )
    (comp (ref "R22")
      (value "2K2")
      (footprint "eagle-import:0402")
      (fields (field (name "PARTNO") "RMCF0402JT2K20"))
      (libsource (lib "eagle-import") (part "R_0402_2K2"))
    )
    (comp (ref "R23")
      (value "10K0")
      (footprint "eagle-import:0402")
      (fields (field (name "PARTNO") "RMCF0402JT10K0"))
      (libsource (lib "eagle-import") (part "R_0402_10K0"))
    )
    (comp (ref "R24")
      (value "10K0")
      (footprint "eagle-import:0402")
      (fields (field (name "PARTNO") "RMCF0402JT10K0"))
      (libsource (lib "eagle-import") (part "R_0402_10K0"))
    )
    (comp (ref "R25")
      (value "100K")
      (footprint "eagle-import:0402")
      (libsource (lib "eagle-import") (part "R_0402"))
    )
    (comp (ref "R26")
      (value "100K")
      (footprint "eagle-import:0402")
      (libsource (lib "eagle-import") (part "R_0402"))
    )
    (comp (ref "R27")
      (value "100K")
      (footprint "eagle-import:0402")
      (libsource (lib "eagle-import") (part "R_0402"))
    )
    (comp (ref "R28")
      (value "2K2")
      (footprint "eagle-import:0402")
      (libsource (lib "eagle-import") (part "R_0402"))
    )
    (comp (ref "R29")
      (value "470R0")
      (footprint "eagle-import:0402")
      (libsource (lib "eagle-import") (part "R_0402"))
    )
    (comp (ref "R30")
      (value "470R0")
      (footprint "eagle-import:0402")
      (libsource (lib "eagle-import") (part "R_0402"))
    )
    (comp (ref "R31")
      (value "470R0")
      (footprint "eagle-import:0402")
      (fields (field (name "PARTNO") "RMCF0402JT470R"))
      (libsource (lib "eagle-import") (part "R_0402_470R0"))
    )
    (comp (ref "R32")
      (value "470R0")
      (footprint "eagle-import:0402")
      (fields (field (name "PARTNO") "RMCF0402JT470R"))
      (libsource (lib "eagle-import") (part "R_0402_470R0"))
    )
    (comp (ref "R33")
      (value "470R0")
      (footprint "eagle-import:0402")
      (fields (field (name "PARTNO") "RMCF0402JT470R"))
      (libsource (lib "eagle-import") (part "R_0402_470R0"))
    )
    (comp (ref "R34")
      (value "10K0")
      (footprint "eagle-import:0402")
      (fields (field (name "PARTNO") "RMCF0402JT10K0"))
      (libsource (lib "eagle-import") (part "R_0402_10K0"))
    )
    (comp (ref "R35")
      (value "2K2")
      (footprint "eagle-import:0402")
      (libsource (lib "eagle-import") (part "R_0402"))
    )
    (comp (ref "R36")
      (value "470R0")
      (footprint "eagle-import:0402")
      (fields (field (name "PARTNO") "RMCF0402JT470R"))
      (libsource (lib "eagle-import") (part "R_0402_470R0"))
    )
    (comp (ref "R37")
      (value "1k")
      (footprint "eagle-import:0805")
      (libsource (lib "eagle-import") (part "R_0805"))
    )
    (comp (ref "R38")
      (value "33")
      (footprint "eagle-import:0805")
      (libsource (lib "eagle-import") (part "R_0805"))
    )
    (comp (ref "R39")
      (value "33")
      (footprint "eagle-import:0805")
      (libsource (lib "eagle-import") (part "R_0805"))
    )
    (comp (ref "R40")
      (value "33")
      (footprint "eagle-import:0805")
      (libsource (lib "eagle-import") (part "R_0805"))
    )
    (comp (ref "R41")
      (value "1k")
      (footprint "eagle-import:0805")
      (libsource (lib "eagle-import") (part "R_0805"))
    )
    (comp (ref "R42")
      (value "1k")
      (footprint "eagle-import:0805")
      (libsource (lib "eagle-import") (part "R_0805"))
    )
    (comp (ref "R43")
      (value "1k")
      (footprint "eagle-import:0805")
      (libsource (lib "eagle-import") (part "R_0805"))
    )
    (comp (ref "R44")
      (value "33")
      (footprint "eagle-import:0805")
      (libsource (lib "eagle-import") (part "R_0805"))
    )
    (comp (ref "R45")
      (value "33")
      (footprint "eagle-import:0805")
      (libsource (lib "eagle-import") (part "R_0805"))
    )
    (comp (ref "R46")
      (value "33")
      (footprint "eagle-import:0805")
      (libsource (lib "eagle-import") (part "R_0805"))
    )
    (comp (ref "R47")
      (value "1k")
      (footprint "eagle-import:0805")
      (libsource (lib "eagle-import") (part "R_0805"))
    )
    (comp (ref "R48")
      (value "1k")
      (footprint "eagle-import:0805")
      (libsource (lib "eagle-import") (part "R_0805"))
    )
    (comp (ref "R49")
      (value "470R0")
      (footprint "eagle-import:0402")
      (libsource (lib "eagle-import") (part "R_0402"))
    )
    (comp (ref "R50")
      (value "470R0")
      (footprint "eagle-import:0402")
      (libsource (lib "eagle-import") (part "R_0402"))
    )
    (comp (ref "R51")
      (value "470R0")
      (footprint "eagle-import:0402")
      (fields (field (name "PARTNO") "RMCF0402JT470R"))
      (libsource (lib "eagle-import") (part "R_0402_470R0"))
    )
    (comp (ref "R52")
      (value "470R0")
      (footprint "eagle-import:0402")
      (fields (field (name "PARTNO") "RMCF0402JT470R"))
      (libsource (lib "eagle-import") (part "R_0402_470R0"))
    )
    (comp (ref "R53")
      (value "10K0")
      (footprint "eagle-import:0402")
      (fields (field (name "PARTNO") "RMCF0402JT10K0"))
      (libsource (lib "eagle-import") (part "R_0402_10K0"))
    )
    (comp (ref "R54")
      (value "2K2")
      (footprint "eagle-import:0402")
      (libsource (lib "eagle-import") (part "R_0402"))
    )
    (comp (ref "R55")
      (value "470R0")
      (footprint "eagle-import:0402")
      (fields (field (name "PARTNO") "RMCF0402JT470R"))
      (libsource (lib "eagle-import") (part "R_0402_470R0"))
    )
    (comp (ref "R56")
      (value "10K0")
      (footprint "eagle-import:0402")
      (fields (field (name "PARTNO") "RMCF0402JT10K0"))
      (libsource (lib "eagle-import") (part "R_0402_10K0"))
    )
    (comp (ref "R57")
      (value "2K2")
      (footprint "eagle-import:0402")
      (libsource (lib "eagle-import") (part "R_0402"))
    )
    (comp (ref "R58")
      (value "470R0")
      (footprint "eagle-import:0402")
      (fields (field (name "PARTNO") "RMCF0402JT470R"))
      (libsource (lib "eagle-import") (part "R_0402_470R0"))
    )
    (comp (ref "R59")
      (value "10K0")
      (footprint "eagle-import:0402")
      (fields (field (name "PARTNO") "RMCF0402JT10K0"))
      (libsource (lib "eagle-import") (part "R_0402_10K0"))
    )
    (comp (ref "R60")
      (value "2K2")
      (footprint "eagle-import:0402")
      (libsource (lib "eagle-import") (part "R_0402"))
    )
    (comp (ref "R61")
      (value "1k")
      (footprint "eagle-import:0805")
      (libsource (lib "eagle-import") (part "R_0805"))
    )
    (comp (ref "R62")
      (value "33")
      (footprint "eagle-import:0805")
      (libsource (lib "eagle-import") (part "R_0805"))
    )
    (comp (ref "R63")
      (value "33")
      (footprint "eagle-import:0805")
      (libsource (lib "eagle-import") (part "R_0805"))
    )
    (comp (ref "R64")
      (value "33")
      (footprint "eagle-import:0805")
      (libsource (lib "eagle-import") (part "R_0805"))
    )
    (comp (ref "R65")
      (value "1k")
      (footprint "eagle-import:0805")
      (libsource (lib "eagle-import") (part "R_0805"))
    )
    (comp (ref "R66")
      (value "1k")
      (footprint "eagle-import:0805")
      (libsource (lib "eagle-import") (part "R_0805"))
    )
    (comp (ref "R67")
      (value "1k")
      (footprint "eagle-import:0805")
      (libsource (lib "eagle-import") (part "R_0805"))
    )
    (comp (ref "R68")
      (value "33")
      (footprint "eagle-import:0805")
      (libsource (lib "eagle-import") (part "R_0805"))
    )
    (comp (ref "R69")
      (value "33")
      (footprint "eagle-import:0805")
      (libsource (lib "eagle-import") (part "R_0805"))
    )
    (comp (ref "R70")
      (value "33")
      (footprint "eagle-import:0805")
      (libsource (lib "eagle-import") (part "R_0805"))
    )
    (comp (ref "R71")
      (value "1k")
      (footprint "eagle-import:0805")
      (libsource (lib "eagle-import") (part "R_0805"))
    )
    (comp (ref "R72")
      (value "1k")
      (footprint "eagle-import:0805")
      (libsource (lib "eagle-import") (part "R_0805"))
    )
    (comp (ref "R73")
      (value "470R0")
      (footprint "eagle-import:0402")
      (fields (field (name "PARTNO") "RMCF0402JT470R"))
      (libsource (lib "eagle-import") (part "R_0402_470R0"))
    )
    (comp (ref "R74")
      (value "10K0")
      (footprint "eagle-import:0402")
      (fields (field (name "PARTNO") "RMCF0402JT10K0"))
      (libsource (lib "eagle-import") (part "R_0402_10K0"))
    )
    (comp (ref "R75")
      (value "2K2")
      (footprint "eagle-import:0402")
      (libsource (lib "eagle-import") (part "R_0402"))
    )
    (comp (ref "R76")
      (value "470R0")
      (footprint "eagle-import:0402")
      (fields (field (name "PARTNO") "RMCF0402JT470R"))
      (libsource (lib "eagle-import") (part "R_0402_470R0"))
    )
    (comp (ref "R77")
      (value "10K0")
      (footprint "eagle-import:0402")
      (fields (field (name "PARTNO") "RMCF0402JT10K0"))
      (libsource (lib "eagle-import") (part "R_0402_10K0"))
    )
    (comp (ref "R78")
      (value "2K2")
      (footprint "eagle-import:0402")
      (libsource (lib "eagle-import") (part "R_0402"))
    )
    (comp (ref "R79")
      (value "470R0")
      (footprint "eagle-import:0402")
      (fields (field (name "PARTNO") "RMCF0402JT470R"))
      (libsource (lib "eagle-import") (part "R_0402_470R0"))
    )
    (comp (ref "R80")
      (value "10K0")
      (footprint "eagle-import:0402")
      (fields (field (name "PARTNO") "RMCF0402JT10K0"))
      (libsource (lib "eagle-import") (part "R_0402_10K0"))
    )
    (comp (ref "R81")
      (value "2K2")
      (footprint "eagle-import:0402")
      (libsource (lib "eagle-import") (part "R_0402"))
    )
    (comp (ref "R82")
      (value "470R0")
      (footprint "eagle-import:0402")
      (fields (field (name "PARTNO") "RMCF0402JT470R"))
      (libsource (lib "eagle-import") (part "R_0402_470R0"))
    )
    (comp (ref "R83")
      (value "10K0")
      (footprint "eagle-import:0402")
      (fields (field (name "PARTNO") "RMCF0402JT10K0"))
      (libsource (lib "eagle-import") (part "R_0402_10K0"))
    )
    (comp (ref "R84")
      (value "2K2")
      (footprint "eagle-import:0402")
      (libsource (lib "eagle-import") (part "R_0402"))
    )
    (comp (ref "R85")
      (value "1k")
      (footprint "eagle-import:0805")
      (libsource (lib "eagle-import") (part "R_0805"))
    )
    (comp (ref "R86")
      (value "33")
      (footprint "eagle-import:0805")
      (libsource (lib "eagle-import") (part "R_0805"))
    )
    (comp (ref "R87")
      (value "33")
      (footprint "eagle-import:0805")
      (libsource (lib "eagle-import") (part "R_0805"))
    )
    (comp (ref "R88")
      (value "33")
      (footprint "eagle-import:0805")
      (libsource (lib "eagle-import") (part "R_0805"))
    )
    (comp (ref "R89")
      (value "1k")
      (footprint "eagle-import:0805")
      (libsource (lib "eagle-import") (part "R_0805"))
    )
    (comp (ref "R90")
      (value "1k")
      (footprint "eagle-import:0805")
      (libsource (lib "eagle-import") (part "R_0805"))
    )
    (comp (ref "R91")
      (value "1k")
      (footprint "eagle-import:0805")
      (libsource (lib "eagle-import") (part "R_0805"))
    )
    (comp (ref "R92")
      (value "33")
      (footprint "eagle-import:0805")
      (libsource (lib "eagle-import") (part "R_0805"))
    )
    (comp (ref "R93")
      (value "33")
      (footprint "eagle-import:0805")
      (libsource (lib "eagle-import") (part "R_0805"))
    )
    (comp (ref "R94")
      (value "33")
      (footprint "eagle-import:0805")
      (libsource (lib "eagle-import") (part "R_0805"))
    )
    (comp (ref "R95")
      (value "1k")
      (footprint "eagle-import:0805")
      (libsource (lib "eagle-import") (part "R_0805"))
    )
    (comp (ref "R96")
      (value "1k")
      (footprint "eagle-import:0805")
      (libsource (lib "eagle-import") (part "R_0805"))
    )
    (comp (ref "R97")
      (value "470R0")
      (footprint "eagle-import:0402")
      (fields (field (name "PARTNO") "RMCF0402JT470R"))
      (libsource (lib "eagle-import") (part "R_0402_470R0"))
    )
    (comp (ref "R98")
      (value "10K0")
      (footprint "eagle-import:0402")
      (fields (field (name "PARTNO") "RMCF0402JT10K0"))
      (libsource (lib "eagle-import") (part "R_0402_10K0"))
    )
    (comp (ref "R99")
      (value "2K2")
      (footprint "eagle-import:0402")
      (libsource (lib "eagle-import") (part "R_0402"))
    )
    (comp (ref "R100")
      (value "470R0")
      (footprint "eagle-import:0402")
      (fields (field (name "PARTNO") "RMCF0402JT470R"))
      (libsource (lib "eagle-import") (part "R_0402_470R0"))
    )
    (comp (ref "R101")
      (value "10K0")
      (footprint "eagle-import:0402")
      (fields (field (name "PARTNO") "RMCF0402JT10K0"))
      (libsource (lib "eagle-import") (part "R_0402_10K0"))
    )
    (comp (ref "R102")
      (value "100K")
      (footprint "eagle-import:0402")
      (libsource (lib "eagle-import") (part "R_0402"))
    )
    (comp (ref "R103")
      (value "100K")
      (footprint "eagle-import:0402")
      (libsource (lib "eagle-import") (part "R_0402"))
    )
    (comp (ref "R104")
      (value "100K")
      (footprint "eagle-import:0402")
      (libsource (lib "eagle-import") (part "R_0402"))
    )
    (comp (ref "R105")
      (value "100K")
      (footprint "eagle-import:0402")
      (libsource (lib "eagle-import") (part "R_0402"))
    )
    (comp (ref "R106")
      (value "100K")
      (footprint "eagle-import:0402")
      (libsource (lib "eagle-import") (part "R_0402"))
    )
    (comp (ref "R107")
      (value "100K")
      (footprint "eagle-import:0402")
      (libsource (lib "eagle-import") (part "R_0402"))
    )
    (comp (ref "R108")
      (value "100K")
      (footprint "eagle-import:0402")
      (libsource (lib "eagle-import") (part "R_0402"))
    )
    (comp (ref "R109")
      (value "1k")
      (footprint "eagle-import:0805")
      (libsource (lib "eagle-import") (part "R_0805"))
    )
    (comp (ref "R110")
      (value "33")
      (footprint "eagle-import:0805")
      (libsource (lib "eagle-import") (part "R_0805"))
    )
    (comp (ref "R111")
      (value "33")
      (footprint "eagle-import:0805")
      (libsource (lib "eagle-import") (part "R_0805"))
    )
    (comp (ref "R112")
      (value "33")
      (footprint "eagle-import:0805")
      (libsource (lib "eagle-import") (part "R_0805"))
    )
    (comp (ref "R113")
      (value "1k")
      (footprint "eagle-import:0805")
      (libsource (lib "eagle-import") (part "R_0805"))
    )
    (comp (ref "R114")
      (value "1k")
      (footprint "eagle-import:0805")
      (libsource (lib "eagle-import") (part "R_0805"))
    )
    (comp (ref "R115")
      (value "1k")
      (footprint "eagle-import:0805")
      (libsource (lib "eagle-import") (part "R_0805"))
    )
    (comp (ref "R116")
      (value "33")
      (footprint "eagle-import:0805")
      (libsource (lib "eagle-import") (part "R_0805"))
    )
    (comp (ref "R117")
      (value "33")
      (footprint "eagle-import:0805")
      (libsource (lib "eagle-import") (part "R_0805"))
    )
    (comp (ref "R118")
      (value "33")
      (footprint "eagle-import:0805")
      (libsource (lib "eagle-import") (part "R_0805"))
    )
    (comp (ref "R119")
      (value "1k")
      (footprint "eagle-import:0805")
      (libsource (lib "eagle-import") (part "R_0805"))
    )
    (comp (ref "R120")
      (value "1k")
      (footprint "eagle-import:0805")
      (libsource (lib "eagle-import") (part "R_0805"))
    )
    (comp (ref "R133")
      (value "1k")
      (footprint "eagle-import:0805")
      (libsource (lib "eagle-import") (part "R_0805"))
    )
    (comp (ref "R134")
      (value "33")
      (footprint "eagle-import:0805")
      (libsource (lib "eagle-import") (part "R_0805"))
    )
    (comp (ref "R135")
      (value "33")
      (footprint "eagle-import:0805")
      (libsource (lib "eagle-import") (part "R_0805"))
    )
    (comp (ref "R136")
      (value "33")
      (footprint "eagle-import:0805")
      (libsource (lib "eagle-import") (part "R_0805"))
    )
    (comp (ref "R137")
      (value "1k")
      (footprint "eagle-import:0805")
      (libsource (lib "eagle-import") (part "R_0805"))
    )
    (comp (ref "R138")
      (value "1k")
      (footprint "eagle-import:0805")
      (libsource (lib "eagle-import") (part "R_0805"))
    )
    (comp (ref "R139")
      (value "1k")
      (footprint "eagle-import:0805")
      (libsource (lib "eagle-import") (part "R_0805"))
    )
    (comp (ref "R140")
      (value "33")
      (footprint "eagle-import:0805")
      (libsource (lib "eagle-import") (part "R_0805"))
    )
    (comp (ref "R141")
      (value "33")
      (footprint "eagle-import:0805")
      (libsource (lib "eagle-import") (part "R_0805"))
    )
    (comp (ref "R142")
      (value "33")
      (footprint "eagle-import:0805")
      (libsource (lib "eagle-import") (part "R_0805"))
    )
    (comp (ref "R143")
      (value "1k")
      (footprint "eagle-import:0805")
      (libsource (lib "eagle-import") (part "R_0805"))
    )
    (comp (ref "R144")
      (value "1k")
      (footprint "eagle-import:0805")
      (libsource (lib "eagle-import") (part "R_0805"))
    )
    (comp (ref "R157")
      (value "1k")
      (footprint "eagle-import:0805")
      (libsource (lib "eagle-import") (part "R_0805"))
    )
    (comp (ref "R158")
      (value "33")
      (footprint "eagle-import:0805")
      (libsource (lib "eagle-import") (part "R_0805"))
    )
    (comp (ref "R159")
      (value "33")
      (footprint "eagle-import:0805")
      (libsource (lib "eagle-import") (part "R_0805"))
    )
    (comp (ref "R160")
      (value "33")
      (footprint "eagle-import:0805")
      (libsource (lib "eagle-import") (part "R_0805"))
    )
    (comp (ref "R161")
      (value "1k")
      (footprint "eagle-import:0805")
      (libsource (lib "eagle-import") (part "R_0805"))
    )
    (comp (ref "R162")
      (value "1k")
      (footprint "eagle-import:0805")
      (libsource (lib "eagle-import") (part "R_0805"))
    )
    (comp (ref "R163")
      (value "1k")
      (footprint "eagle-import:0805")
      (libsource (lib "eagle-import") (part "R_0805"))
    )
    (comp (ref "R164")
      (value "33")
      (footprint "eagle-import:0805")
      (libsource (lib "eagle-import") (part "R_0805"))
    )
    (comp (ref "R165")
      (value "33")
      (footprint "eagle-import:0805")
      (libsource (lib "eagle-import") (part "R_0805"))
    )
    (comp (ref "R166")
      (value "33")
      (footprint "eagle-import:0805")
      (libsource (lib "eagle-import") (part "R_0805"))
    )
    (comp (ref "R167")
      (value "1k")
      (footprint "eagle-import:0805")
      (libsource (lib "eagle-import") (part "R_0805"))
    )
    (comp (ref "R168")
      (value "1k")
      (footprint "eagle-import:0805")
      (libsource (lib "eagle-import") (part "R_0805"))
    )
    (comp (ref "RJ1")
      (value "RJ45")
      (footprint "eagle-import:RJ45_TH_ELEC")
      (fields (field (name "PARTNO") "13F-64GYD2PL2NL"))
      (libsource (lib "eagle-import") (part "RJ45_WITH_ELEC"))
    )
    (comp (ref "U$1")
      (value "RELAY_KYOTO_KF0604D")
      (footprint "eagle-import:RELAY_KYOTO_KF0604D")
      (libsource (lib "eagle-import") (part "RELAY_KYOTO_KF0604D"))
    )
    (comp (ref "U$2")
      (value "RELAY_KYOTO_KF0604D")
      (footprint "eagle-import:RELAY_KYOTO_KF0604D")
      (libsource (lib "eagle-import") (part "RELAY_KYOTO_KF0604D"))
    )
    (comp (ref "U$7")
      (value "RELAY_KYOTO_KF0604D")
      (footprint "eagle-import:RELAY_KYOTO_KF0604D")
      (libsource (lib "eagle-import") (part "RELAY_KYOTO_KF0604D"))
    )
    (comp (ref "U$8")
      (value "RELAY_KYOTO_KF0604D")
      (footprint "eagle-import:RELAY_KYOTO_KF0604D")
      (libsource (lib "eagle-import") (part "RELAY_KYOTO_KF0604D"))
    )
    (comp (ref "U1")
      (value "KSZ8081_QFN_24")
      (footprint "eagle-import:QFN-24-M")
      (fields (field (name "PARTNO") "KSZ8081RNACA"))
      (libsource (lib "eagle-import") (part "KSZ8081RNACAQFN-24-M"))
    )
    (comp (ref "U2")
      (value "AP2151DWG-7")
      (footprint "eagle-import:SOT-23-5")
      (fields (field (name "PARTNO") "AP2151WG-7"))
      (libsource (lib "eagle-import") (part "AP2151DWG-7"))
    )
    (comp (ref "U3")
      (value "S7G2LQFP176")
      (footprint "eagle-import:LQFP176_24X24")
      (fields (field (name "PARTNO") "R7FS7G27H3A01CFC#AA0"))
      (libsource (lib "eagle-import") (part "RENESAS_S7G2_X_176"))
    )
    (comp (ref "U5")
      (value "NPN")
      (footprint "eagle-import:SOT323")
      (fields (field (name "PARTNO") "BC846BW_NPN"))
      (libsource (lib "eagle-import") (part "BC846BW"))
    )
    (comp (ref "U6")
      (value "NPN")
      (footprint "eagle-import:SOT323")
      (fields (field (name "PARTNO") "BC846BW_NPN"))
      (libsource (lib "eagle-import") (part "BC846BW"))
    )
    (comp (ref "U7")
      (value "NPN")
      (footprint "eagle-import:SOT323")
      (fields (field (name "PARTNO") "BC846BW_NPN"))
      (libsource (lib "eagle-import") (part "BC846BW"))
    )
    (comp (ref "U8")
      (value "NPN")
      (footprint "eagle-import:SOT323")
      (fields (field (name "PARTNO") "BC846BW_NPN"))
      (libsource (lib "eagle-import") (part "BC846BW"))
    )
    (comp (ref "U9")
      (value "NPN")
      (footprint "eagle-import:SOT323")
      (fields (field (name "PARTNO") "BC846BW_NPN"))
      (libsource (lib "eagle-import") (part "BC846BW"))
    )
    (comp (ref "U10")
      (value "NPN")
      (footprint "eagle-import:SOT323")
      (fields (field (name "PARTNO") "BC846BW_NPN"))
      (libsource (lib "eagle-import") (part "BC846BW"))
    )
    (comp (ref "U11")
      (value "NPN")
      (footprint "eagle-import:SOT323")
      (fields (field (name "PARTNO") "BC846BW_NPN"))
      (libsource (lib "eagle-import") (part "BC846BW"))
    )
    (comp (ref "U12")
      (value "NPN")
      (footprint "eagle-import:SOT323")
      (fields (field (name "PARTNO") "BC846BW_NPN"))
      (libsource (lib "eagle-import") (part "BC846BW"))
    )
    (comp (ref "U13")
      (value "NPN")
      (footprint "eagle-import:SOT323")
      (fields (field (name "PARTNO") "BC846BW_NPN"))
      (libsource (lib "eagle-import") (part "BC846BW"))
    )
    (comp (ref "U14")
      (value "NPN")
      (footprint "eagle-import:SOT323")
      (fields (field (name "PARTNO") "BC846BW_NPN"))
      (libsource (lib "eagle-import") (part "BC846BW"))
    )
    (comp (ref "U15")
      (value "NPN")
      (footprint "eagle-import:SOT323")
      (fields (field (name "PARTNO") "BC846BW_NPN"))
      (libsource (lib "eagle-import") (part "BC846BW"))
    )
    (comp (ref "U16")
      (value "NPN")
      (footprint "eagle-import:SOT323")
      (fields (field (name "PARTNO") "BC846BW_NPN"))
      (libsource (lib "eagle-import") (part "BC846BW"))
    )
    (comp (ref "U17")
      (value "NPN")
      (footprint "eagle-import:SOT323")
      (fields (field (name "PARTNO") "BC846BW_NPN"))
      (libsource (lib "eagle-import") (part "BC846BW"))
    )
    (comp (ref "U18")
      (value "NPN")
      (footprint "eagle-import:SOT323")
      (fields (field (name "PARTNO") "BC846BW_NPN"))
      (libsource (lib "eagle-import") (part "BC846BW"))
    )
    (comp (ref "U19")
      (value "NPN")
      (footprint "eagle-import:SOT323")
      (fields (field (name "PARTNO") "BC846BW_NPN"))
      (libsource (lib "eagle-import") (part "BC846BW"))
    )
    (comp (ref "U20")
      (value "NPN")
      (footprint "eagle-import:SOT323")
      (fields (field (name "PARTNO") "BC846BW_NPN"))
      (libsource (lib "eagle-import") (part "BC846BW"))
    )
    (comp (ref "U21")
      (value "NPN")
      (footprint "eagle-import:SOT323")
      (fields (field (name "PARTNO") "BC846BW_NPN"))
      (libsource (lib "eagle-import") (part "BC846BW"))
    )
    (comp (ref "U22")
      (value "NPN")
      (footprint "eagle-import:SOT323")
      (fields (field (name "PARTNO") "BC846BW_NPN"))
      (libsource (lib "eagle-import") (part "BC846BW"))
    )
    (comp (ref "U23")
      (value "NPN")
      (footprint "eagle-import:SOT323")
      (fields (field (name "PARTNO") "BC846BW_NPN"))
      (libsource (lib "eagle-import") (part "BC846BW"))
    )
    (comp (ref "U24")
      (value "NPN")
      (footprint "eagle-import:SOT323")
      (fields (field (name "PARTNO") "BC846BW_NPN"))
      (libsource (lib "eagle-import") (part "BC846BW"))
    )
    (comp (ref "U25")
      (value "NPN")
      (footprint "eagle-import:SOT323")
      (fields (field (name "PARTNO") "BC846BW_NPN"))
      (libsource (lib "eagle-import") (part "BC846BW"))
    )
    (comp (ref "U26")
      (value "NPN")
      (footprint "eagle-import:SOT323")
      (fields (field (name "PARTNO") "BC846BW_NPN"))
      (libsource (lib "eagle-import") (part "BC846BW"))
    )
    (comp (ref "U27")
      (value "NPN")
      (footprint "eagle-import:SOT323")
      (fields (field (name "PARTNO") "BC846BW_NPN"))
      (libsource (lib "eagle-import") (part "BC846BW"))
    )
    (comp (ref "U28")
      (value "NPN")
      (footprint "eagle-import:SOT323")
      (fields (field (name "PARTNO") "BC846BW_NPN"))
      (libsource (lib "eagle-import") (part "BC846BW"))
    )
    (comp (ref "U29")
      (value "NPN")
      (footprint "eagle-import:SOT323")
      (fields (field (name "PARTNO") "BC846BW_NPN"))
      (libsource (lib "eagle-import") (part "BC846BW"))
    )
    (comp (ref "U30")
      (value "NPN")
      (footprint "eagle-import:SOT323")
      (fields (field (name "PARTNO") "BC846BW_NPN"))
      (libsource (lib "eagle-import") (part "BC846BW"))
    )
    (comp (ref "U34")
      (value "NPN")
      (footprint "eagle-import:SOT323")
      (fields (field (name "PARTNO") "BC846BW_NPN"))
      (libsource (lib "eagle-import") (part "BC846BW"))
    )
    (comp (ref "U35")
      (value "NPN")
      (footprint "eagle-import:SOT323")
      (fields (field (name "PARTNO") "BC846BW_NPN"))
      (libsource (lib "eagle-import") (part "BC846BW"))
    )
    (comp (ref "U36")
      (value "NPN")
      (footprint "eagle-import:SOT323")
      (fields (field (name "PARTNO") "BC846BW_NPN"))
      (libsource (lib "eagle-import") (part "BC846BW"))
    )
    (comp (ref "U37")
      (value "NPN")
      (footprint "eagle-import:SOT323")
      (fields (field (name "PARTNO") "BC846BW_NPN"))
      (libsource (lib "eagle-import") (part "BC846BW"))
    )
    (comp (ref "U38")
      (value "NPN")
      (footprint "eagle-import:SOT323")
      (fields (field (name "PARTNO") "BC846BW_NPN"))
      (libsource (lib "eagle-import") (part "BC846BW"))
    )
    (comp (ref "U39")
      (value "NPN")
      (footprint "eagle-import:SOT323")
      (fields (field (name "PARTNO") "BC846BW_NPN"))
      (libsource (lib "eagle-import") (part "BC846BW"))
    )
    (comp (ref "U46")
      (value "NPN")
      (footprint "eagle-import:SOT323")
      (fields (field (name "PARTNO") "BC846BW_NPN"))
      (libsource (lib "eagle-import") (part "BC846BW"))
    )
    (comp (ref "U47")
      (value "NPN")
      (footprint "eagle-import:SOT323")
      (fields (field (name "PARTNO") "BC846BW_NPN"))
      (libsource (lib "eagle-import") (part "BC846BW"))
    )
    (comp (ref "U48")
      (value "NPN")
      (footprint "eagle-import:SOT323")
      (fields (field (name "PARTNO") "BC846BW_NPN"))
      (libsource (lib "eagle-import") (part "BC846BW"))
    )
    (comp (ref "U49")
      (value "NPN")
      (footprint "eagle-import:SOT323")
      (fields (field (name "PARTNO") "BC846BW_NPN"))
      (libsource (lib "eagle-import") (part "BC846BW"))
    )
    (comp (ref "U50")
      (value "NPN")
      (footprint "eagle-import:SOT323")
      (fields (field (name "PARTNO") "BC846BW_NPN"))
      (libsource (lib "eagle-import") (part "BC846BW"))
    )
    (comp (ref "U51")
      (value "NPN")
      (footprint "eagle-import:SOT323")
      (fields (field (name "PARTNO") "BC846BW_NPN"))
      (libsource (lib "eagle-import") (part "BC846BW"))
    )
    (comp (ref "U58")
      (value "NPN")
      (footprint "eagle-import:SOT323")
      (fields (field (name "PARTNO") "BC846BW_NPN"))
      (libsource (lib "eagle-import") (part "BC846BW"))
    )
    (comp (ref "U59")
      (value "NPN")
      (footprint "eagle-import:SOT323")
      (fields (field (name "PARTNO") "BC846BW_NPN"))
      (libsource (lib "eagle-import") (part "BC846BW"))
    )
    (comp (ref "U60")
      (value "NPN")
      (footprint "eagle-import:SOT323")
      (fields (field (name "PARTNO") "BC846BW_NPN"))
      (libsource (lib "eagle-import") (part "BC846BW"))
    )
    (comp (ref "U61")
      (value "NPN")
      (footprint "eagle-import:SOT323")
      (fields (field (name "PARTNO") "BC846BW_NPN"))
      (libsource (lib "eagle-import") (part "BC846BW"))
    )
    (comp (ref "U62")
      (value "NPN")
      (footprint "eagle-import:SOT323")
      (fields (field (name "PARTNO") "BC846BW_NPN"))
      (libsource (lib "eagle-import") (part "BC846BW"))
    )
    (comp (ref "U63")
      (value "NPN")
      (footprint "eagle-import:SOT323")
      (fields (field (name "PARTNO") "BC846BW_NPN"))
      (libsource (lib "eagle-import") (part "BC846BW"))
    )
    (comp (ref "U70")
      (value "NPN")
      (footprint "eagle-import:SOT323")
      (fields (field (name "PARTNO") "BC846BW_NPN"))
      (libsource (lib "eagle-import") (part "BC846BW"))
    )
    (comp (ref "U71")
      (value "NPN")
      (footprint "eagle-import:SOT323")
      (fields (field (name "PARTNO") "BC846BW_NPN"))
      (libsource (lib "eagle-import") (part "BC846BW"))
    )
    (comp (ref "U72")
      (value "NPN")
      (footprint "eagle-import:SOT323")
      (fields (field (name "PARTNO") "BC846BW_NPN"))
      (libsource (lib "eagle-import") (part "BC846BW"))
    )
    (comp (ref "U73")
      (value "NPN")
      (footprint "eagle-import:SOT323")
      (fields (field (name "PARTNO") "BC846BW_NPN"))
      (libsource (lib "eagle-import") (part "BC846BW"))
    )
    (comp (ref "U74")
      (value "NPN")
      (footprint "eagle-import:SOT323")
      (fields (field (name "PARTNO") "BC846BW_NPN"))
      (libsource (lib "eagle-import") (part "BC846BW"))
    )
    (comp (ref "U75")
      (value "NPN")
      (footprint "eagle-import:SOT323")
      (fields (field (name "PARTNO") "BC846BW_NPN"))
      (libsource (lib "eagle-import") (part "BC846BW"))
    )
    (comp (ref "X1")
      (value "25MHz")
      (footprint "eagle-import:SMD_3225")
      (fields (field (name "PARTNO") "FA-238 25.0000MB-B3"))
      (libsource (lib "eagle-import") (part "XTAL_25_MHZ"))
    )
    (comp (ref "X2")
      (value "24MHz")
      (footprint "eagle-import:SMD_3225")
      (fields (field (name "PARTNO") "FA-238 24.0000MB-C3 "))
      (libsource (lib "eagle-import") (part "XTAL_24_MHZ"))
    )
    (comp (ref "X3")
      (value "32.768KHz")
      (footprint "eagle-import:SMD_X_2_PADS")
      (fields (field (name "PARTNO") "ABS07-32.768KHZ-T"))
      (libsource (lib "eagle-import") (part "XTAL_32.768KHZ"))
    )
  )
  (nets
    (net (code "1") (name "A_A_DIR") (class "Default")
      (node (ref "R111") (pin "1") (pinfunction "1_1") (pintype "passive"))
      (node (ref "U3") (pin "73") (pinfunction "P9_5_73") (pintype "bidirectional"))
    )
    (net (code "2") (name "A_A_ENABLE") (class "Default")
      (node (ref "R112") (pin "1") (pinfunction "1_1") (pintype "passive"))
      (node (ref "U3") (pin "72") (pinfunction "P9_6_72") (pintype "bidirectional"))
    )
    (net (code "3") (name "A_A_HLFB_OUT") (class "Default")
      (node (ref "J25") (pin "5") (pinfunction "5-HLFB-_5") (pintype "passive"))
    )
    (net (code "4") (name "A_A_MI_DIR") (class "Default")
      (node (ref "J25") (pin "7") (pinfunction "7-INPUT_A-_7") (pintype "passive"))
      (node (ref "R113") (pin "1") (pinfunction "1_1") (pintype "passive"))
      (node (ref "U47") (pin "3") (pinfunction "C(3)_3") (pintype "input"))
    )
    (net (code "5") (name "A_A_MI_ENABLE") (class "Default")
      (node (ref "J25") (pin "8") (pinfunction "8-ENABLE-_8") (pintype "passive"))
      (node (ref "R114") (pin "1") (pinfunction "1_1") (pintype "passive"))
      (node (ref "U48") (pin "3") (pinfunction "C(3)_3") (pintype "input"))
    )
    (net (code "6") (name "A_A_MI_STEP") (class "Default")
      (node (ref "J25") (pin "6") (pinfunction "6-INPUT_B-_6") (pintype "passive"))
      (node (ref "R109") (pin "1") (pinfunction "1_1") (pintype "passive"))
      (node (ref "U46") (pin "3") (pinfunction "C(3)_3") (pintype "input"))
    )
    (net (code "7") (name "A_A_STEP") (class "Default")
      (node (ref "R110") (pin "1") (pinfunction "1_1") (pintype "passive"))
      (node (ref "U3") (pin "74") (pinfunction "P3_12_74") (pintype "bidirectional"))
    )
    (net (code "8") (name "A_B_DIR") (class "Default")
      (node (ref "R117") (pin "1") (pinfunction "1_1") (pintype "passive"))
      (node (ref "U3") (pin "76") (pinfunction "P3_10_76") (pintype "bidirectional"))
    )
    (net (code "9") (name "A_B_ENABLE") (class "Default")
      (node (ref "R118") (pin "1") (pinfunction "1_1") (pintype "passive"))
      (node (ref "U3") (pin "75") (pinfunction "P3_11_75") (pintype "bidirectional"))
    )
    (net (code "10") (name "A_B_HLFB_OUT") (class "Default")
      (node (ref "J26") (pin "5") (pinfunction "5-HLFB-_5") (pintype "passive"))
    )
    (net (code "11") (name "A_B_MI_DIR") (class "Default")
      (node (ref "J26") (pin "7") (pinfunction "7-INPUT_A-_7") (pintype "passive"))
      (node (ref "R119") (pin "1") (pinfunction "1_1") (pintype "passive"))
      (node (ref "U50") (pin "3") (pinfunction "C(3)_3") (pintype "input"))
    )
    (net (code "12") (name "A_B_MI_ENABLE") (class "Default")
      (node (ref "J26") (pin "8") (pinfunction "8-ENABLE-_8") (pintype "passive"))
      (node (ref "R120") (pin "1") (pinfunction "1_1") (pintype "passive"))
      (node (ref "U51") (pin "3") (pinfunction "C(3)_3") (pintype "input"))
    )
    (net (code "13") (name "A_B_MI_STEP") (class "Default")
      (node (ref "J26") (pin "6") (pinfunction "6-INPUT_B-_6") (pintype "passive"))
      (node (ref "R115") (pin "1") (pinfunction "1_1") (pintype "passive"))
      (node (ref "U49") (pin "3") (pinfunction "C(3)_3") (pintype "input"))
    )
    (net (code "14") (name "A_B_STEP") (class "Default")
      (node (ref "R116") (pin "1") (pinfunction "1_1") (pintype "passive"))
      (node (ref "U3") (pin "77") (pinfunction "P3_9_77") (pintype "bidirectional"))
    )
    (net (code "15") (name "B_MI_DIR") (class "Default")
      (node (ref "J34") (pin "7") (pinfunction "7-INPUT_A-_7") (pintype "passive"))
      (node (ref "R167") (pin "1") (pinfunction "1_1") (pintype "passive"))
      (node (ref "U74") (pin "3") (pinfunction "C(3)_3") (pintype "input"))
    )
    (net (code "16") (name "C58") (class "Default")
      (node (ref "C12") (pin "P$1") (pinfunction "1_P$1") (pintype "passive"))
      (node (ref "RJ1") (pin "4") (pinfunction "CT1_4") (pintype "bidirectional"))
    )
    (net (code "17") (name "C60") (class "Default")
      (node (ref "C13") (pin "P$1") (pinfunction "1_P$1") (pintype "passive"))
      (node (ref "RJ1") (pin "5") (pinfunction "CT2_5") (pintype "bidirectional"))
    )
    (net (code "18") (name "CRS_DV") (class "Default")
      (node (ref "R12") (pin "P$2") (pinfunction "2_P$2") (pintype "passive"))
      (node (ref "U1") (pin "15") (pinfunction "CRS_DV/PHYAD[1:0]_15") (pintype "bidirectional"))
    )
    (net (code "19") (name "C_A_DIR") (class "Default")
      (node (ref "R135") (pin "1") (pinfunction "1_1") (pintype "passive"))
      (node (ref "U3") (pin "58") (pinfunction "P9_0_58") (pintype "bidirectional"))
    )
    (net (code "20") (name "C_A_ENABLE") (class "Default")
      (node (ref "R136") (pin "1") (pinfunction "1_1") (pintype "passive"))
      (node (ref "U3") (pin "57") (pinfunction "P3_15_57") (pintype "bidirectional"))
    )
    (net (code "21") (name "C_A_HLFB_OUT") (class "Default")
      (node (ref "J29") (pin "5") (pinfunction "5-HLFB-_5") (pintype "passive"))
    )
    (net (code "22") (name "C_A_MI_DIR") (class "Default")
      (node (ref "J29") (pin "7") (pinfunction "7-INPUT_A-_7") (pintype "passive"))
      (node (ref "R137") (pin "1") (pinfunction "1_1") (pintype "passive"))
      (node (ref "U59") (pin "3") (pinfunction "C(3)_3") (pintype "input"))
    )
    (net (code "23") (name "C_A_MI_ENABLE") (class "Default")
      (node (ref "J29") (pin "8") (pinfunction "8-ENABLE-_8") (pintype "passive"))
      (node (ref "R138") (pin "1") (pinfunction "1_1") (pintype "passive"))
      (node (ref "U60") (pin "3") (pinfunction "C(3)_3") (pintype "input"))
    )
    (net (code "24") (name "C_A_MI_STEP") (class "Default")
      (node (ref "J29") (pin "6") (pinfunction "6-INPUT_B-_6") (pintype "passive"))
      (node (ref "R133") (pin "1") (pinfunction "1_1") (pintype "passive"))
      (node (ref "U58") (pin "3") (pinfunction "C(3)_3") (pintype "input"))
    )
    (net (code "25") (name "C_A_STEP") (class "Default")
      (node (ref "R134") (pin "1") (pinfunction "1_1") (pintype "passive"))
      (node (ref "U3") (pin "59") (pinfunction "P9_1_59") (pintype "bidirectional"))
    )
    (net (code "26") (name "C_B_DIR") (class "Default")
      (node (ref "R141") (pin "1") (pinfunction "1_1") (pintype "passive"))
      (node (ref "U3") (pin "70") (pinfunction "P9_8_70") (pintype "bidirectional"))
    )
    (net (code "27") (name "C_B_ENABLE") (class "Default")
      (node (ref "R142") (pin "1") (pinfunction "1_1") (pintype "passive"))
      (node (ref "U3") (pin "68") (pinfunction "P2_1/MD_68") (pintype "bidirectional"))
    )
    (net (code "28") (name "C_B_HLFB_OUT") (class "Default")
      (node (ref "J30") (pin "5") (pinfunction "5-HLFB-_5") (pintype "passive"))
    )
    (net (code "29") (name "C_B_MI_DIR") (class "Default")
      (node (ref "J30") (pin "7") (pinfunction "7-INPUT_A-_7") (pintype "passive"))
      (node (ref "R143") (pin "1") (pinfunction "1_1") (pintype "passive"))
      (node (ref "U62") (pin "3") (pinfunction "C(3)_3") (pintype "input"))
    )
    (net (code "30") (name "C_B_MI_ENABLE") (class "Default")
      (node (ref "J30") (pin "8") (pinfunction "8-ENABLE-_8") (pintype "passive"))
      (node (ref "R144") (pin "1") (pinfunction "1_1") (pintype "passive"))
      (node (ref "U63") (pin "3") (pinfunction "C(3)_3") (pintype "input"))
    )
    (net (code "31") (name "C_B_MI_STEP") (class "Default")
      (node (ref "J30") (pin "6") (pinfunction "6-INPUT_B-_6") (pintype "passive"))
      (node (ref "R139") (pin "1") (pinfunction "1_1") (pintype "passive"))
      (node (ref "U61") (pin "3") (pinfunction "C(3)_3") (pintype "input"))
    )
    (net (code "32") (name "C_B_STEP") (class "Default")
      (node (ref "R140") (pin "1") (pinfunction "1_1") (pintype "passive"))
      (node (ref "U3") (pin "71") (pinfunction "P9_7_71") (pintype "bidirectional"))
    )
    (net (code "33") (name "ESTOP") (class "Default")
      (node (ref "R79") (pin "P$2") (pinfunction "2_P$2") (pintype "passive"))
      (node (ref "R80") (pin "P$2") (pinfunction "2_P$2") (pintype "passive"))
      (node (ref "U21") (pin "2") (pinfunction "E(1)_2") (pintype "output"))
      (node (ref "U3") (pin "69") (pinfunction "P2_0(INPUT_ONLY)_69") (pintype "bidirectional"))
    )
    (net (code "34") (name "ESTOP_RET") (class "Default")
      (node (ref "J20") (pin "1") (pinfunction "1_1") (pintype "passive"))
      (node (ref "R78") (pin "P$1") (pinfunction "1_P$1") (pintype "passive"))
    )
    (net (code "35") (name "ETH") (class "Default")
      (node (ref "U1") (pin "16") (pinfunction "REF_CLK_16") (pintype "bidirectional"))
      (node (ref "U3") (pin "9") (pinfunction "P7_1_9") (pintype "bidirectional"))
    )
    (net (code "36") (name "ETH_CRS_DV") (class "Default")
      (node (ref "R12") (pin "P$1") (pinfunction "1_P$1") (pintype "passive"))
      (node (ref "U3") (pin "13") (pinfunction "P7_5_13") (pintype "bidirectional"))
    )
    (net (code "37") (name "ETH_IRQ14") (class "Default")
      (node (ref "R2") (pin "P$1") (pinfunction "1_P$1") (pintype "passive"))
      (node (ref "U1") (pin "18") (pinfunction "INTRP_18") (pintype "bidirectional"))
      (node (ref "U3") (pin "159") (pinfunction "P0_10/AN103_159") (pintype "bidirectional"))
    )
    (net (code "38") (name "ETH_MDC") (class "Default")
      (node (ref "R4") (pin "P$1") (pinfunction "1_P$1") (pintype "passive"))
      (node (ref "U1") (pin "11") (pinfunction "MDC_11") (pintype "input"))
      (node (ref "U3") (pin "4") (pinfunction "P4_3_4") (pintype "bidirectional"))
    )
    (net (code "39") (name "ETH_MDIO") (class "Default")
      (node (ref "R6") (pin "P$1") (pinfunction "1_P$1") (pintype "passive"))
      (node (ref "U1") (pin "10") (pinfunction "MDIO_10") (pintype "bidirectional"))
      (node (ref "U3") (pin "5") (pinfunction "P4_4_5") (pintype "bidirectional"))
    )
    (net (code "40") (name "ETH_RESET") (class "Default")
      (node (ref "C6") (pin "P$1") (pinfunction "1_P$1") (pintype "passive"))
      (node (ref "R3") (pin "P$1") (pinfunction "1_P$1") (pintype "passive"))
      (node (ref "U1") (pin "24") (pinfunction "~{RST}_24") (pintype "input"))
      (node (ref "U3") (pin "172") (pinfunction "P8_6_172") (pintype "bidirectional"))
    )
    (net (code "41") (name "ETH_RXD0") (class "Default")
      (node (ref "R10") (pin "P$1") (pinfunction "1_P$1") (pintype "passive"))
      (node (ref "U3") (pin "10") (pinfunction "P7_2_10") (pintype "bidirectional"))
    )
    (net (code "42") (name "ETH_RXD1") (class "Default")
      (node (ref "R9") (pin "P$1") (pinfunction "1_P$1") (pintype "passive"))
      (node (ref "U3") (pin "11") (pinfunction "P7_3_11") (pintype "bidirectional"))
    )
    (net (code "43") (name "ETH_RX_ER") (class "Default")
      (node (ref "R11") (pin "P$1") (pinfunction "1_P$1") (pintype "passive"))
      (node (ref "U3") (pin "12") (pinfunction "P7_4_12") (pintype "bidirectional"))
    )
    (net (code "44") (name "ETH_TXD0") (class "Default")
      (node (ref "U1") (pin "20") (pinfunction "TXD0_20") (pintype "input"))
      (node (ref "U3") (pin "8") (pinfunction "P7_0_8") (pintype "bidirectional"))
    )
    (net (code "45") (name "ETH_TXD1") (class "Default")
      (node (ref "U1") (pin "21") (pinfunction "TXD1_21") (pintype "bidirectional"))
      (node (ref "U3") (pin "7") (pinfunction "P4_6_7") (pintype "bidirectional"))
    )
    (net (code "46") (name "ETH_TXD_EN") (class "Default")
      (node (ref "U1") (pin "19") (pinfunction "TXEN_19") (pintype "input"))
      (node (ref "U3") (pin "6") (pinfunction "P4_5_6") (pintype "bidirectional"))
    )
    (net (code "47") (name "GND") (class "Default")
      (node (ref "C1") (pin "P$2") (pinfunction "2_P$2") (pintype "passive"))
      (node (ref "C10") (pin "P$2") (pinfunction "2_P$2") (pintype "passive"))
      (node (ref "C11") (pin "P$2") (pinfunction "2_P$2") (pintype "passive"))
      (node (ref "C12") (pin "P$2") (pinfunction "2_P$2") (pintype "passive"))
      (node (ref "C13") (pin "P$2") (pinfunction "2_P$2") (pintype "passive"))
      (node (ref "C14") (pin "P$2") (pinfunction "2_P$2") (pintype "passive"))
      (node (ref "C15") (pin "P$2") (pinfunction "2_P$2") (pintype "passive"))
      (node (ref "C16") (pin "P$2") (pinfunction "2_P$2") (pintype "passive"))
      (node (ref "C17") (pin "P$2") (pinfunction "2_P$2") (pintype "passive"))
      (node (ref "C18") (pin "P$2") (pinfunction "2_P$2") (pintype "passive"))
      (node (ref "C19") (pin "P$1") (pinfunction "1_P$1") (pintype "passive"))
      (node (ref "C2") (pin "P$2") (pinfunction "2_P$2") (pintype "passive"))
      (node (ref "C20") (pin "P$1") (pinfunction "1_P$1") (pintype "passive"))
      (node (ref "C21") (pin "P$1") (pinfunction "1_P$1") (pintype "passive"))
      (node (ref "C22") (pin "P$1") (pinfunction "1_P$1") (pintype "passive"))
      (node (ref "C23") (pin "P$2") (pinfunction "2_P$2") (pintype "passive"))
      (node (ref "C24") (pin "P$1") (pinfunction "1_P$1") (pintype "passive"))
      (node (ref "C25") (pin "P$1") (pinfunction "1_P$1") (pintype "passive"))
      (node (ref "C26") (pin "P$2") (pinfunction "2_P$2") (pintype "passive"))
      (node (ref "C27") (pin "P$1") (pinfunction "1_P$1") (pintype "passive"))
      (node (ref "C28") (pin "P$2") (pinfunction "2_P$2") (pintype "passive"))
      (node (ref "C29") (pin "P$2") (pinfunction "2_P$2") (pintype "passive"))
      (node (ref "C3") (pin "P$2") (pinfunction "2_P$2") (pintype "passive"))
      (node (ref "C30") (pin "P$1") (pinfunction "1_P$1") (pintype "passive"))
      (node (ref "C31") (pin "2") (pinfunction "2_2") (pintype "passive"))
      (node (ref "C32") (pin "P$2") (pinfunction "2_P$2") (pintype "passive"))
      (node (ref "C33") (pin "P$2") (pinfunction "2_P$2") (pintype "passive"))
      (node (ref "C34") (pin "P$1") (pinfunction "1_P$1") (pintype "passive"))
      (node (ref "C35") (pin "P$1") (pinfunction "1_P$1") (pintype "passive"))
      (node (ref "C36") (pin "P$2") (pinfunction "2_P$2") (pintype "passive"))
      (node (ref "C37") (pin "P$2") (pinfunction "2_P$2") (pintype "passive"))
      (node (ref "C38") (pin "P$1") (pinfunction "1_P$1") (pintype "passive"))
      (node (ref "C39") (pin "P$2") (pinfunction "2_P$2") (pintype "passive"))
      (node (ref "C4") (pin "P$2") (pinfunction "2_P$2") (pintype "passive"))
      (node (ref "C40") (pin "P$2") (pinfunction "2_P$2") (pintype "passive"))
      (node (ref "C41") (pin "P$2") (pinfunction "2_P$2") (pintype "passive"))
      (node (ref "C42") (pin "P$2") (pinfunction "2_P$2") (pintype "passive"))
      (node (ref "C43") (pin "P$1") (pinfunction "1_P$1") (pintype "passive"))
      (node (ref "C5") (pin "P$2") (pinfunction "2_P$2") (pintype "passive"))
      (node (ref "C6") (pin "P$2") (pinfunction "2_P$2") (pintype "passive"))
      (node (ref "C7") (pin "P$2") (pinfunction "2_P$2") (pintype "passive"))
      (node (ref "C8") (pin "P$2") (pinfunction "2_P$2") (pintype "passive"))
      (node (ref "C9") (pin "P$2") (pinfunction "2_P$2") (pintype "passive"))
      (node (ref "J1") (pin "6") (pinfunction "SUPPLY_VOLTAGE_GROUND_6") (pintype "power_in"))
      (node (ref "J10") (pin "2") (pinfunction "2_2") (pintype "passive"))
      (node (ref "J11") (pin "2") (pinfunction "2_2") (pintype "passive"))
      (node (ref "J12") (pin "2") (pinfunction "2_2") (pintype "passive"))
      (node (ref "J19") (pin "2") (pinfunction "2_2") (pintype "passive"))
      (node (ref "J2") (pin "P$1") (pinfunction "P$1_P$1") (pintype "bidirectional"))
      (node (ref "J20") (pin "2") (pinfunction "2_2") (pintype "passive"))
      (node (ref "J27") (pin "2") (pinfunction "2_2") (pintype "passive"))
      (node (ref "J28") (pin "2") (pinfunction "2_2") (pintype "passive"))
      (node (ref "J3") (pin "10") (pinfunction "10_10") (pintype "passive"))
      (node (ref "J3") (pin "6") (pinfunction "6_6") (pintype "passive"))
      (node (ref "J3") (pin "8") (pinfunction "8_8") (pintype "passive"))
      (node (ref "J31") (pin "2") (pinfunction "2_2") (pintype "passive"))
      (node (ref "J32") (pin "2") (pinfunction "2_2") (pintype "passive"))
      (node (ref "J39") (pin "P$1") (pinfunction "P$1_P$1") (pintype "bidirectional"))
      (node (ref "J39") (pin "P$11") (pinfunction "P$11_P$11") (pintype "bidirectional"))
      (node (ref "J39") (pin "P$13") (pinfunction "P$13_P$13") (pintype "bidirectional"))
      (node (ref "J39") (pin "P$15") (pinfunction "P$15_P$15") (pintype "bidirectional"))
      (node (ref "J39") (pin "P$17") (pinfunction "P$17_P$17") (pintype "bidirectional"))
      (node (ref "J39") (pin "P$19") (pinfunction "P$19_P$19") (pintype "bidirectional"))
      (node (ref "J39") (pin "P$3") (pinfunction "P$3_P$3") (pintype "bidirectional"))
      (node (ref "J39") (pin "P$5") (pinfunction "P$5_P$5") (pintype "bidirectional"))
      (node (ref "J39") (pin "P$7") (pinfunction "P$7_P$7") (pintype "bidirectional"))
      (node (ref "J39") (pin "P$9") (pinfunction "P$9_P$9") (pintype "bidirectional"))
      (node (ref "J5") (pin "2") (pinfunction "2_2") (pintype "passive"))
      (node (ref "J6") (pin "GND") (pinfunction "GND_GND") (pintype "power_in"))
      (node (ref "J7") (pin "P$5") (pinfunction "GND_P$5") (pintype "bidirectional"))
      (node (ref "J8") (pin "P$12") (pinfunction "P$12_P$12") (pintype "bidirectional"))
      (node (ref "J8") (pin "P$14") (pinfunction "P$14_P$14") (pintype "bidirectional"))
      (node (ref "J8") (pin "P$16") (pinfunction "P$16_P$16") (pintype "bidirectional"))
      (node (ref "J8") (pin "P$18") (pinfunction "P$18_P$18") (pintype "bidirectional"))
      (node (ref "J8") (pin "P$20") (pinfunction "P$20_P$20") (pintype "bidirectional"))
      (node (ref "J8") (pin "P$6") (pinfunction "P$6_P$6") (pintype "bidirectional"))
      (node (ref "LED1") (pin "2") (pinfunction "C_2") (pintype "passive"))
      (node (ref "LED10") (pin "2") (pinfunction "C_2") (pintype "passive"))
      (node (ref "LED11") (pin "2") (pinfunction "C_2") (pintype "passive"))
      (node (ref "LED12") (pin "2") (pinfunction "C_2") (pintype "passive"))
      (node (ref "LED13") (pin "2") (pinfunction "C_2") (pintype "passive"))
      (node (ref "LED14") (pin "2") (pinfunction "C_2") (pintype "passive"))
      (node (ref "LED15") (pin "2") (pinfunction "C_2") (pintype "passive"))
      (node (ref "LED16") (pin "2") (pinfunction "C_2") (pintype "passive"))
      (node (ref "LED3") (pin "2") (pinfunction "C_2") (pintype "passive"))
      (node (ref "LED6") (pin "2") (pinfunction "C_2") (pintype "passive"))
      (node (ref "LED7") (pin "2") (pinfunction "C_2") (pintype "passive"))
      (node (ref "R1") (pin "P$1") (pinfunction "1_P$1") (pintype "passive"))
      (node (ref "R101") (pin "P$1") (pinfunction "1_P$1") (pintype "passive"))
      (node (ref "R21") (pin "P$1") (pinfunction "1_P$1") (pintype "passive"))
      (node (ref "R22") (pin "P$1") (pinfunction "1_P$1") (pintype "passive"))
      (node (ref "R23") (pin "P$1") (pinfunction "1_P$1") (pintype "passive"))
      (node (ref "R24") (pin "P$1") (pinfunction "1_P$1") (pintype "passive"))
      (node (ref "R34") (pin "P$1") (pinfunction "1_P$1") (pintype "passive"))
      (node (ref "R53") (pin "P$1") (pinfunction "1_P$1") (pintype "passive"))
      (node (ref "R56") (pin "P$1") (pinfunction "1_P$1") (pintype "passive"))
      (node (ref "R59") (pin "P$1") (pinfunction "1_P$1") (pintype "passive"))
      (node (ref "R74") (pin "P$1") (pinfunction "1_P$1") (pintype "passive"))
      (node (ref "R77") (pin "P$1") (pinfunction "1_P$1") (pintype "passive"))
      (node (ref "R80") (pin "P$1") (pinfunction "1_P$1") (pintype "passive"))
      (node (ref "R83") (pin "P$1") (pinfunction "1_P$1") (pintype "passive"))
      (node (ref "R98") (pin "P$1") (pinfunction "1_P$1") (pintype "passive"))
      (node (ref "RJ1") (pin "10") (pinfunction "GLO_10") (pintype "bidirectional"))
      (node (ref "RJ1") (pin "8") (pinfunction "P8_8") (pintype "bidirectional"))
      (node (ref "U1") (pin "22") (pinfunction "GND_22") (pintype "power_in"))
      (node (ref "U1") (pin "25") (pinfunction "25_25") (pintype "passive"))
      (node (ref "U10") (pin "2") (pinfunction "E(1)_2") (pintype "output"))
      (node (ref "U11") (pin "2") (pinfunction "E(1)_2") (pintype "output"))
      (node (ref "U12") (pin "2") (pinfunction "E(1)_2") (pintype "output"))
      (node (ref "U13") (pin "2") (pinfunction "E(1)_2") (pintype "output"))
      (node (ref "U14") (pin "2") (pinfunction "E(1)_2") (pintype "output"))
      (node (ref "U15") (pin "2") (pinfunction "E(1)_2") (pintype "output"))
      (node (ref "U16") (pin "2") (pinfunction "E(1)_2") (pintype "output"))
      (node (ref "U17") (pin "2") (pinfunction "E(1)_2") (pintype "output"))
      (node (ref "U2") (pin "2") (pinfunction "GND_2") (pintype "input"))
      (node (ref "U22") (pin "2") (pinfunction "E(1)_2") (pintype "output"))
      (node (ref "U23") (pin "2") (pinfunction "E(1)_2") (pintype "output"))
      (node (ref "U24") (pin "2") (pinfunction "E(1)_2") (pintype "output"))
      (node (ref "U25") (pin "2") (pinfunction "E(1)_2") (pintype "output"))
      (node (ref "U26") (pin "2") (pinfunction "E(1)_2") (pintype "output"))
      (node (ref "U27") (pin "2") (pinfunction "E(1)_2") (pintype "output"))
      (node (ref "U3") (pin "111") (pinfunction "VSS(IO)5_111") (pintype "bidirectional"))
      (node (ref "U3") (pin "124") (pinfunction "VSS(IO)6_124") (pintype "bidirectional"))
      (node (ref "U3") (pin "139") (pinfunction "VSS(IO)7_139") (pintype "bidirectional"))
      (node (ref "U3") (pin "150") (pinfunction "VSS(IO)8_150") (pintype "bidirectional"))
      (node (ref "U3") (pin "153") (pinfunction "VREFL_153") (pintype "bidirectional"))
      (node (ref "U3") (pin "156") (pinfunction "AVSS0_156") (pintype "bidirectional"))
      (node (ref "U3") (pin "157") (pinfunction "VREFL0_157") (pintype "bidirectional"))
      (node (ref "U3") (pin "170") (pinfunction "VSS(IO)9_170") (pintype "bidirectional"))
      (node (ref "U3") (pin "22") (pinfunction "VSS1_22") (pintype "bidirectional"))
      (node (ref "U3") (pin "28") (pinfunction "AVSS_USBHS_28") (pintype "bidirectional"))
      (node (ref "U3") (pin "29") (pinfunction "PVSS_USBHS_29") (pintype "bidirectional"))
      (node (ref "U3") (pin "30") (pinfunction "VSS2_USBHS_30") (pintype "bidirectional"))
      (node (ref "U3") (pin "33") (pinfunction "VSS1_USBHS_33") (pintype "bidirectional"))
      (node (ref "U3") (pin "35") (pinfunction "VSSIO_35") (pintype "bidirectional"))
      (node (ref "U3") (pin "45") (pinfunction "VSS_USB_45") (pintype "bidirectional"))
      (node (ref "U3") (pin "60") (pinfunction "VSS(IO)2_60") (pintype "bidirectional"))
      (node (ref "U3") (pin "63") (pinfunction "VSS(IO/DCDC)_63") (pintype "bidirectional"))
      (node (ref "U3") (pin "66") (pinfunction "VCC_DCDC(IO/DCDC)_66") (pintype "bidirectional"))
      (node (ref "U3") (pin "83") (pinfunction "VSS(IO)3_83") (pintype "bidirectional"))
      (node (ref "U3") (pin "98") (pinfunction "VSS(IO)4_98") (pintype "bidirectional"))
      (node (ref "U34") (pin "2") (pinfunction "E(1)_2") (pintype "output"))
      (node (ref "U35") (pin "2") (pinfunction "E(1)_2") (pintype "output"))
      (node (ref "U36") (pin "2") (pinfunction "E(1)_2") (pintype "output"))
      (node (ref "U37") (pin "2") (pinfunction "E(1)_2") (pintype "output"))
      (node (ref "U38") (pin "2") (pinfunction "E(1)_2") (pintype "output"))
      (node (ref "U39") (pin "2") (pinfunction "E(1)_2") (pintype "output"))
      (node (ref "U46") (pin "2") (pinfunction "E(1)_2") (pintype "output"))
      (node (ref "U47") (pin "2") (pinfunction "E(1)_2") (pintype "output"))
      (node (ref "U48") (pin "2") (pinfunction "E(1)_2") (pintype "output"))
      (node (ref "U49") (pin "2") (pinfunction "E(1)_2") (pintype "output"))
      (node (ref "U50") (pin "2") (pinfunction "E(1)_2") (pintype "output"))
      (node (ref "U51") (pin "2") (pinfunction "E(1)_2") (pintype "output"))
      (node (ref "U58") (pin "2") (pinfunction "E(1)_2") (pintype "output"))
      (node (ref "U59") (pin "2") (pinfunction "E(1)_2") (pintype "output"))
      (node (ref "U6") (pin "2") (pinfunction "E(1)_2") (pintype "output"))
      (node (ref "U60") (pin "2") (pinfunction "E(1)_2") (pintype "output"))
      (node (ref "U61") (pin "2") (pinfunction "E(1)_2") (pintype "output"))
      (node (ref "U62") (pin "2") (pinfunction "E(1)_2") (pintype "output"))
      (node (ref "U63") (pin "2") (pinfunction "E(1)_2") (pintype "output"))
      (node (ref "U7") (pin "2") (pinfunction "E(1)_2") (pintype "output"))
      (node (ref "U70") (pin "2") (pinfunction "E(1)_2") (pintype "output"))
      (node (ref "U71") (pin "2") (pinfunction "E(1)_2") (pintype "output"))
      (node (ref "U72") (pin "2") (pinfunction "E(1)_2") (pintype "output"))
      (node (ref "U73") (pin "2") (pinfunction "E(1)_2") (pintype "output"))
      (node (ref "U74") (pin "2") (pinfunction "E(1)_2") (pintype "output"))
      (node (ref "U75") (pin "2") (pinfunction "E(1)_2") (pintype "output"))
      (node (ref "X1") (pin "2") (pinfunction "2_2") (pintype "bidirectional"))
      (node (ref "X1") (pin "4") (pinfunction "4_4") (pintype "bidirectional"))
      (node (ref "X2") (pin "2") (pinfunction "2_2") (pintype "bidirectional"))
      (node (ref "X2") (pin "4") (pinfunction "4_4") (pintype "bidirectional"))
    )
    (net (code "48") (name "GNDE") (class "Default")
      (node (ref "J1") (pin "S1") (pinfunction "SHIELD_S1") (pintype "passive"))
      (node (ref "J1") (pin "S2") (pinfunction "SHIELD_S2") (pintype "passive"))
      (node (ref "J1") (pin "S3") (pinfunction "SHIELD_S3") (pintype "passive"))
      (node (ref "J1") (pin "S4") (pinfunction "SHIELD_S4") (pintype "passive"))
      (node (ref "J2") (pin "P$4") (pinfunction "P$4_P$4") (pintype "bidirectional"))
      (node (ref "J6") (pin "SHLD1") (pinfunction "SHIELD_1_SHLD1") (pintype "bidirectional"))
      (node (ref "J6") (pin "SHLD2") (pinfunction "SHIELD_2_SHLD2") (pintype "bidirectional"))
      (node (ref "J7") (pin "P$6") (pinfunction "SHIELD1_P$6") (pintype "bidirectional"))
      (node (ref "J7") (pin "P$7") (pinfunction "SHIELD2_P$7") (pintype "bidirectional"))
      (node (ref "J7") (pin "P$8") (pinfunction "SHIELD3_P$8") (pintype "bidirectional"))
      (node (ref "J7") (pin "P$9") (pinfunction "SHIELD4_P$9") (pintype "bidirectional"))
      (node (ref "RJ1") (pin "13") (pinfunction "GNDE0_13") (pintype "bidirectional"))
      (node (ref "RJ1") (pin "14") (pinfunction "GNDE1_14") (pintype "bidirectional"))
    )
    (net (code "49") (name "ID") (class "Default")
      (node (ref "J7") (pin "P$4") (pinfunction "ID_P$4") (pintype "bidirectional"))
    )
    (net (code "50") (name "IIC_1_SCL") (class "Default")
      (node (ref "J8") (pin "P$8") (pinfunction "P$8_P$8") (pintype "bidirectional"))
      (node (ref "R14") (pin "P$2") (pinfunction "2_P$2") (pintype "passive"))
      (node (ref "U3") (pin "132") (pinfunction "P1_0_132") (pintype "bidirectional"))
    )
    (net (code "51") (name "IIC_1_SDA") (class "Default")
      (node (ref "J8") (pin "P$7") (pinfunction "P$7_P$7") (pintype "bidirectional"))
      (node (ref "R15") (pin "P$2") (pinfunction "2_P$2") (pintype "passive"))
      (node (ref "U3") (pin "131") (pinfunction "P1_1_131") (pintype "bidirectional"))
    )
    (net (code "52") (name "LED1{slash}SPEED") (class "Default")
      (node (ref "RJ1") (pin "11") (pinfunction "YLO_11") (pintype "bidirectional"))
      (node (ref "U1") (pin "23") (pinfunction "LED0/ANEN_SPEED_23") (pintype "bidirectional"))
    )
    (net (code "53") (name "LS_01") (class "Default")
      (node (ref "R33") (pin "P$2") (pinfunction "2_P$2") (pintype "passive"))
      (node (ref "R34") (pin "P$2") (pinfunction "2_P$2") (pintype "passive"))
      (node (ref "U3") (pin "50") (pinfunction "P2_6_50") (pintype "bidirectional"))
      (node (ref "U5") (pin "2") (pinfunction "E(1)_2") (pintype "output"))
    )
    (net (code "54") (name "LS_01_RET") (class "Default")
      (node (ref "J32") (pin "1") (pinfunction "1_1") (pintype "passive"))
      (node (ref "R28") (pin "P$1") (pinfunction "1_P$1") (pintype "passive"))
    )
    (net (code "55") (name "LS_02") (class "Default")
      (node (ref "R36") (pin "P$2") (pinfunction "2_P$2") (pintype "passive"))
      (node (ref "R53") (pin "P$2") (pinfunction "2_P$2") (pintype "passive"))
      (node (ref "U3") (pin "51") (pinfunction "P2_5_51") (pintype "bidirectional"))
      (node (ref "U8") (pin "2") (pinfunction "E(1)_2") (pintype "output"))
    )
    (net (code "56") (name "LS_02_RET") (class "Default")
      (node (ref "J31") (pin "1") (pinfunction "1_1") (pintype "passive"))
      (node (ref "R35") (pin "P$1") (pinfunction "1_P$1") (pintype "passive"))
    )
    (net (code "57") (name "LS_03") (class "Default")
      (node (ref "R55") (pin "P$2") (pinfunction "2_P$2") (pintype "passive"))
      (node (ref "R56") (pin "P$2") (pinfunction "2_P$2") (pintype "passive"))
      (node (ref "U3") (pin "53") (pinfunction "P2_3_53") (pintype "bidirectional"))
      (node (ref "U9") (pin "2") (pinfunction "E(1)_2") (pintype "output"))
    )
    (net (code "58") (name "LS_03_RET") (class "Default")
      (node (ref "J28") (pin "1") (pinfunction "1_1") (pintype "passive"))
      (node (ref "R54") (pin "P$1") (pinfunction "1_P$1") (pintype "passive"))
    )
    (net (code "59") (name "LS_04") (class "Default")
      (node (ref "R73") (pin "P$2") (pinfunction "2_P$2") (pintype "passive"))
      (node (ref "R74") (pin "P$2") (pinfunction "2_P$2") (pintype "passive"))
      (node (ref "U19") (pin "2") (pinfunction "E(1)_2") (pintype "output"))
      (node (ref "U3") (pin "54") (pinfunction "P2_2_54") (pintype "bidirectional"))
    )
    (net (code "60") (name "LS_04_RET") (class "Default")
      (node (ref "J27") (pin "1") (pinfunction "1_1") (pintype "passive"))
      (node (ref "R60") (pin "P$1") (pinfunction "1_P$1") (pintype "passive"))
    )
    (net (code "61") (name "LS_05") (class "Default")
      (node (ref "R58") (pin "P$2") (pinfunction "2_P$2") (pintype "passive"))
      (node (ref "R59") (pin "P$2") (pinfunction "2_P$2") (pintype "passive"))
      (node (ref "U18") (pin "2") (pinfunction "E(1)_2") (pintype "output"))
      (node (ref "U3") (pin "81") (pinfunction "P3_5_81") (pintype "bidirectional"))
    )
    (net (code "62") (name "LS_05_RET") (class "Default")
      (node (ref "J19") (pin "1") (pinfunction "1_1") (pintype "passive"))
      (node (ref "R57") (pin "P$1") (pinfunction "1_P$1") (pintype "passive"))
    )
    (net (code "63") (name "LS_06") (class "Default")
      (node (ref "R76") (pin "P$2") (pinfunction "2_P$2") (pintype "passive"))
      (node (ref "R77") (pin "P$2") (pinfunction "2_P$2") (pintype "passive"))
      (node (ref "U20") (pin "2") (pinfunction "E(1)_2") (pintype "output"))
      (node (ref "U3") (pin "82") (pinfunction "P3_4_82") (pintype "bidirectional"))
    )
    (net (code "64") (name "LS_06_RET") (class "Default")
      (node (ref "J12") (pin "1") (pinfunction "1_1") (pintype "passive"))
      (node (ref "R75") (pin "P$1") (pinfunction "1_P$1") (pintype "passive"))
    )
    (net (code "65") (name "LS_07") (class "Default")
      (node (ref "R97") (pin "P$2") (pinfunction "2_P$2") (pintype "passive"))
      (node (ref "R98") (pin "P$2") (pinfunction "2_P$2") (pintype "passive"))
      (node (ref "U29") (pin "2") (pinfunction "E(1)_2") (pintype "output"))
      (node (ref "U3") (pin "86") (pinfunction "P3_2_86") (pintype "bidirectional"))
    )
    (net (code "66") (name "LS_07_RET") (class "Default")
      (node (ref "J11") (pin "1") (pinfunction "1_1") (pintype "passive"))
      (node (ref "R84") (pin "P$1") (pinfunction "1_P$1") (pintype "passive"))
    )
    (net (code "67") (name "LS_08") (class "Default")
      (node (ref "R82") (pin "P$2") (pinfunction "2_P$2") (pintype "passive"))
      (node (ref "R83") (pin "P$2") (pinfunction "2_P$2") (pintype "passive"))
      (node (ref "U28") (pin "2") (pinfunction "E(1)_2") (pintype "output"))
      (node (ref "U3") (pin "87") (pinfunction "P3_1_87") (pintype "bidirectional"))
    )
    (net (code "68") (name "LS_08_RET") (class "Default")
      (node (ref "J5") (pin "1") (pinfunction "1_1") (pintype "passive"))
      (node (ref "R81") (pin "P$1") (pinfunction "1_P$1") (pintype "passive"))
    )
    (net (code "69") (name "LS_09") (class "Default")
      (node (ref "R100") (pin "P$2") (pinfunction "2_P$2") (pintype "passive"))
      (node (ref "R101") (pin "P$2") (pinfunction "2_P$2") (pintype "passive"))
      (node (ref "U3") (pin "92") (pinfunction "P1_11_92") (pintype "bidirectional"))
      (node (ref "U30") (pin "2") (pinfunction "E(1)_2") (pintype "output"))
    )
    (net (code "70") (name "LS_09_RET") (class "Default")
      (node (ref "J10") (pin "1") (pinfunction "1_1") (pintype "passive"))
      (node (ref "R99") (pin "P$1") (pinfunction "1_P$1") (pintype "passive"))
    )
    (net (code "71") (name "NC") (class "Default")
      (node (ref "RJ1") (pin "7") (pinfunction "P7_7") (pintype "bidirectional"))
      (node (ref "U3") (pin "79") (pinfunction "P3_7_79") (pintype "bidirectional"))
      (node (ref "U3") (pin "80") (pinfunction "P3_6_80") (pintype "bidirectional"))
      (node (ref "U3") (pin "85") (pinfunction "P3_3_85") (pintype "bidirectional"))
    )
    (net (code "72") (name "Net-(C8-1)") (class "Default")
      (node (ref "C8") (pin "P$1") (pinfunction "1_P$1") (pintype "passive"))
      (node (ref "C9") (pin "P$1") (pinfunction "1_P$1") (pintype "passive"))
      (node (ref "FB1") (pin "2") (pinfunction "P$2_2") (pintype "bidirectional"))
      (node (ref "U1") (pin "2") (pinfunction "VDDA_3.3_2") (pintype "power_in"))
    )
    (net (code "73") (name "Net-(C24-2)") (class "Default")
      (node (ref "C24") (pin "P$2") (pinfunction "2_P$2") (pintype "passive"))
      (node (ref "U3") (pin "148") (pinfunction "VCL2_148") (pintype "bidirectional"))
    )
    (net (code "74") (name "Net-(C28-1)") (class "Default")
      (node (ref "C28") (pin "P$1") (pinfunction "1_P$1") (pintype "passive"))
      (node (ref "J7") (pin "P$1") (pinfunction "VBUS_P$1") (pintype "bidirectional"))
      (node (ref "R16") (pin "P$2") (pinfunction "2_P$2") (pintype "passive"))
      (node (ref "R21") (pin "P$2") (pinfunction "2_P$2") (pintype "passive"))
    )
    (net (code "75") (name "Net-(C33-1)") (class "Default")
      (node (ref "C33") (pin "P$1") (pinfunction "1_P$1") (pintype "passive"))
      (node (ref "U3") (pin "19") (pinfunction "VCLO_19") (pintype "bidirectional"))
    )
    (net (code "76") (name "Net-(C42-1)") (class "Default")
      (node (ref "C42") (pin "P$1") (pinfunction "1_P$1") (pintype "passive"))
      (node (ref "U3") (pin "62") (pinfunction "VCL1_62") (pintype "bidirectional"))
    )
    (net (code "77") (name "Net-(J7-D+)") (class "Default")
      (node (ref "J7") (pin "P$3") (pinfunction "D+_P$3") (pintype "bidirectional"))
      (node (ref "R18") (pin "P$2") (pinfunction "2_P$2") (pintype "passive"))
    )
    (net (code "78") (name "Net-(J7-D-)") (class "Default")
      (node (ref "J7") (pin "P$2") (pinfunction "D-_P$2") (pintype "bidirectional"))
      (node (ref "R17") (pin "P$2") (pinfunction "2_P$2") (pintype "passive"))
    )
    (net (code "79") (name "Net-(LED1-A)") (class "Default")
      (node (ref "LED1") (pin "1") (pinfunction "A_1") (pintype "passive"))
      (node (ref "R5") (pin "P$1") (pinfunction "1_P$1") (pintype "passive"))
    )
    (net (code "80") (name "Net-(LED3-A)") (class "Default")
      (node (ref "LED3") (pin "1") (pinfunction "A_1") (pintype "passive"))
      (node (ref "R33") (pin "P$1") (pinfunction "1_P$1") (pintype "passive"))
    )
    (net (code "81") (name "Net-(LED4-A)") (class "Default")
      (node (ref "LED4") (pin "1") (pinfunction "A_1") (pintype "passive"))
      (node (ref "R32") (pin "P$1") (pinfunction "1_P$1") (pintype "passive"))
    )
    (net (code "82") (name "Net-(LED4-C)") (class "Default")
      (node (ref "LED4") (pin "2") (pinfunction "C_2") (pintype "passive"))
      (node (ref "U$1") (pin "P$1") (pinfunction "VC-_P$1") (pintype "bidirectional"))
      (node (ref "U6") (pin "3") (pinfunction "C(3)_3") (pintype "input"))
    )
    (net (code "83") (name "Net-(LED5-A)") (class "Default")
      (node (ref "LED5") (pin "1") (pinfunction "A_1") (pintype "passive"))
      (node (ref "R31") (pin "P$1") (pinfunction "1_P$1") (pintype "passive"))
    )
    (net (code "84") (name "Net-(LED5-C)") (class "Default")
      (node (ref "LED5") (pin "2") (pinfunction "C_2") (pintype "passive"))
      (node (ref "U$2") (pin "P$1") (pinfunction "VC-_P$1") (pintype "bidirectional"))
      (node (ref "U7") (pin "3") (pinfunction "C(3)_3") (pintype "input"))
    )
    (net (code "85") (name "Net-(LED6-A)") (class "Default")
      (node (ref "LED6") (pin "1") (pinfunction "A_1") (pintype "passive"))
      (node (ref "R36") (pin "P$1") (pinfunction "1_P$1") (pintype "passive"))
    )
    (net (code "86") (name "Net-(LED7-A)") (class "Default")
      (node (ref "LED7") (pin "1") (pinfunction "A_1") (pintype "passive"))
      (node (ref "R55") (pin "P$1") (pinfunction "1_P$1") (pintype "passive"))
    )
    (net (code "87") (name "Net-(LED8-A)") (class "Default")
      (node (ref "LED8") (pin "1") (pinfunction "A_1") (pintype "passive"))
      (node (ref "R52") (pin "P$1") (pinfunction "1_P$1") (pintype "passive"))
    )
    (net (code "88") (name "Net-(LED8-C)") (class "Default")
      (node (ref "LED8") (pin "2") (pinfunction "C_2") (pintype "passive"))
      (node (ref "U$7") (pin "P$1") (pinfunction "VC-_P$1") (pintype "bidirectional"))
      (node (ref "U16") (pin "3") (pinfunction "C(3)_3") (pintype "input"))
    )
    (net (code "89") (name "Net-(LED9-A)") (class "Default")
      (node (ref "LED9") (pin "1") (pinfunction "A_1") (pintype "passive"))
      (node (ref "R51") (pin "P$1") (pinfunction "1_P$1") (pintype "passive"))
    )
    (net (code "90") (name "Net-(LED9-C)") (class "Default")
      (node (ref "LED9") (pin "2") (pinfunction "C_2") (pintype "passive"))
      (node (ref "U$8") (pin "P$1") (pinfunction "VC-_P$1") (pintype "bidirectional"))
      (node (ref "U17") (pin "3") (pinfunction "C(3)_3") (pintype "input"))
    )
    (net (code "91") (name "Net-(LED10-A)") (class "Default")
      (node (ref "LED10") (pin "1") (pinfunction "A_1") (pintype "passive"))
      (node (ref "R58") (pin "P$1") (pinfunction "1_P$1") (pintype "passive"))
    )
    (net (code "92") (name "Net-(LED11-A)") (class "Default")
      (node (ref "LED11") (pin "1") (pinfunction "A_1") (pintype "passive"))
      (node (ref "R73") (pin "P$1") (pinfunction "1_P$1") (pintype "passive"))
    )
    (net (code "93") (name "Net-(LED12-A)") (class "Default")
      (node (ref "LED12") (pin "1") (pinfunction "A_1") (pintype "passive"))
      (node (ref "R76") (pin "P$1") (pinfunction "1_P$1") (pintype "passive"))
    )
    (net (code "94") (name "Net-(LED13-A)") (class "Default")
      (node (ref "LED13") (pin "1") (pinfunction "A_1") (pintype "passive"))
      (node (ref "R79") (pin "P$1") (pinfunction "1_P$1") (pintype "passive"))
    )
    (net (code "95") (name "Net-(LED14-A)") (class "Default")
      (node (ref "LED14") (pin "1") (pinfunction "A_1") (pintype "passive"))
      (node (ref "R82") (pin "P$1") (pinfunction "1_P$1") (pintype "passive"))
    )
    (net (code "96") (name "Net-(LED15-A)") (class "Default")
      (node (ref "LED15") (pin "1") (pinfunction "A_1") (pintype "passive"))
      (node (ref "R97") (pin "P$1") (pinfunction "1_P$1") (pintype "passive"))
    )
    (net (code "97") (name "Net-(LED16-A)") (class "Default")
      (node (ref "LED16") (pin "1") (pinfunction "A_1") (pintype "passive"))
      (node (ref "R100") (pin "P$1") (pinfunction "1_P$1") (pintype "passive"))
    )
    (net (code "98") (name "Net-(R22-2)") (class "Default")
      (node (ref "R22") (pin "P$2") (pinfunction "2_P$2") (pintype "passive"))
      (node (ref "U3") (pin "27") (pinfunction "USBHS_RREF_27") (pintype "bidirectional"))
    )
    (net (code "99") (name "Net-(R23-2)") (class "Default")
      (node (ref "R23") (pin "P$2") (pinfunction "2_P$2") (pintype "passive"))
      (node (ref "U3") (pin "64") (pinfunction "VLO1(DCDC)_64") (pintype "bidirectional"))
    )
    (net (code "100") (name "Net-(R24-2)") (class "Default")
      (node (ref "R24") (pin "P$2") (pinfunction "2_P$2") (pintype "passive"))
      (node (ref "U3") (pin "65") (pinfunction "VLO2(DCDC)_65") (pintype "bidirectional"))
    )
    (net (code "101") (name "Net-(R28-2)") (class "Default")
      (node (ref "R28") (pin "P$2") (pinfunction "2_P$2") (pintype "passive"))
      (node (ref "U5") (pin "1") (pinfunction "B(2)_1") (pintype "input"))
    )
    (net (code "102") (name "Net-(R29-2)") (class "Default")
      (node (ref "R29") (pin "P$2") (pinfunction "2_P$2") (pintype "passive"))
      (node (ref "U6") (pin "1") (pinfunction "B(2)_1") (pintype "input"))
    )
    (net (code "103") (name "Net-(R30-2)") (class "Default")
      (node (ref "R30") (pin "P$2") (pinfunction "2_P$2") (pintype "passive"))
      (node (ref "U7") (pin "1") (pinfunction "B(2)_1") (pintype "input"))
    )
    (net (code "104") (name "Net-(R35-2)") (class "Default")
      (node (ref "R35") (pin "P$2") (pinfunction "2_P$2") (pintype "passive"))
      (node (ref "U8") (pin "1") (pinfunction "B(2)_1") (pintype "input"))
    )
    (net (code "105") (name "Net-(R49-2)") (class "Default")
      (node (ref "R49") (pin "P$2") (pinfunction "2_P$2") (pintype "passive"))
      (node (ref "U16") (pin "1") (pinfunction "B(2)_1") (pintype "input"))
    )
    (net (code "106") (name "Net-(R50-2)") (class "Default")
      (node (ref "R50") (pin "P$2") (pinfunction "2_P$2") (pintype "passive"))
      (node (ref "U17") (pin "1") (pinfunction "B(2)_1") (pintype "input"))
    )
    (net (code "107") (name "Net-(R54-2)") (class "Default")
      (node (ref "R54") (pin "P$2") (pinfunction "2_P$2") (pintype "passive"))
      (node (ref "U9") (pin "1") (pinfunction "B(2)_1") (pintype "input"))
    )
    (net (code "108") (name "Net-(R57-2)") (class "Default")
      (node (ref "R57") (pin "P$2") (pinfunction "2_P$2") (pintype "passive"))
      (node (ref "U18") (pin "1") (pinfunction "B(2)_1") (pintype "input"))
    )
    (net (code "109") (name "Net-(R60-2)") (class "Default")
      (node (ref "R60") (pin "P$2") (pinfunction "2_P$2") (pintype "passive"))
      (node (ref "U19") (pin "1") (pinfunction "B(2)_1") (pintype "input"))
    )
    (net (code "110") (name "Net-(R75-2)") (class "Default")
      (node (ref "R75") (pin "P$2") (pinfunction "2_P$2") (pintype "passive"))
      (node (ref "U20") (pin "1") (pinfunction "B(2)_1") (pintype "input"))
    )
    (net (code "111") (name "Net-(R78-2)") (class "Default")
      (node (ref "R78") (pin "P$2") (pinfunction "2_P$2") (pintype "passive"))
      (node (ref "U21") (pin "1") (pinfunction "B(2)_1") (pintype "input"))
    )
    (net (code "112") (name "Net-(R81-2)") (class "Default")
      (node (ref "R81") (pin "P$2") (pinfunction "2_P$2") (pintype "passive"))
      (node (ref "U28") (pin "1") (pinfunction "B(2)_1") (pintype "input"))
    )
    (net (code "113") (name "Net-(R84-2)") (class "Default")
      (node (ref "R84") (pin "P$2") (pinfunction "2_P$2") (pintype "passive"))
      (node (ref "U29") (pin "1") (pinfunction "B(2)_1") (pintype "input"))
    )
    (net (code "114") (name "Net-(R99-2)") (class "Default")
      (node (ref "R99") (pin "P$2") (pinfunction "2_P$2") (pintype "passive"))
      (node (ref "U30") (pin "1") (pinfunction "B(2)_1") (pintype "input"))
    )
    (net (code "115") (name "Net-(U10-B(2))") (class "Default")
      (node (ref "R38") (pin "2") (pinfunction "2_2") (pintype "passive"))
      (node (ref "U10") (pin "1") (pinfunction "B(2)_1") (pintype "input"))
    )
    (net (code "116") (name "Net-(U11-B(2))") (class "Default")
      (node (ref "R39") (pin "2") (pinfunction "2_2") (pintype "passive"))
      (node (ref "U11") (pin "1") (pinfunction "B(2)_1") (pintype "input"))
    )
    (net (code "117") (name "Net-(U12-B(2))") (class "Default")
      (node (ref "R40") (pin "2") (pinfunction "2_2") (pintype "passive"))
      (node (ref "U12") (pin "1") (pinfunction "B(2)_1") (pintype "input"))
    )
    (net (code "118") (name "Net-(U13-B(2))") (class "Default")
      (node (ref "R44") (pin "2") (pinfunction "2_2") (pintype "passive"))
      (node (ref "U13") (pin "1") (pinfunction "B(2)_1") (pintype "input"))
    )
    (net (code "119") (name "Net-(U14-B(2))") (class "Default")
      (node (ref "R45") (pin "2") (pinfunction "2_2") (pintype "passive"))
      (node (ref "U14") (pin "1") (pinfunction "B(2)_1") (pintype "input"))
    )
    (net (code "120") (name "Net-(U15-B(2))") (class "Default")
      (node (ref "R46") (pin "2") (pinfunction "2_2") (pintype "passive"))
      (node (ref "U15") (pin "1") (pinfunction "B(2)_1") (pintype "input"))
    )
    (net (code "121") (name "Net-(U22-B(2))") (class "Default")
      (node (ref "R62") (pin "2") (pinfunction "2_2") (pintype "passive"))
      (node (ref "U22") (pin "1") (pinfunction "B(2)_1") (pintype "input"))
    )
    (net (code "122") (name "Net-(U23-B(2))") (class "Default")
      (node (ref "R63") (pin "2") (pinfunction "2_2") (pintype "passive"))
      (node (ref "U23") (pin "1") (pinfunction "B(2)_1") (pintype "input"))
    )
    (net (code "123") (name "Net-(U24-B(2))") (class "Default")
      (node (ref "R64") (pin "2") (pinfunction "2_2") (pintype "passive"))
      (node (ref "U24") (pin "1") (pinfunction "B(2)_1") (pintype "input"))
    )
    (net (code "124") (name "Net-(U25-B(2))") (class "Default")
      (node (ref "R68") (pin "2") (pinfunction "2_2") (pintype "passive"))
      (node (ref "U25") (pin "1") (pinfunction "B(2)_1") (pintype "input"))
    )
    (net (code "125") (name "Net-(U26-B(2))") (class "Default")
      (node (ref "R69") (pin "2") (pinfunction "2_2") (pintype "passive"))
      (node (ref "U26") (pin "1") (pinfunction "B(2)_1") (pintype "input"))
    )
    (net (code "126") (name "Net-(U27-B(2))") (class "Default")
      (node (ref "R70") (pin "2") (pinfunction "2_2") (pintype "passive"))
      (node (ref "U27") (pin "1") (pinfunction "B(2)_1") (pintype "input"))
    )
    (net (code "127") (name "Net-(U34-B(2))") (class "Default")
      (node (ref "R86") (pin "2") (pinfunction "2_2") (pintype "passive"))
      (node (ref "U34") (pin "1") (pinfunction "B(2)_1") (pintype "input"))
    )
    (net (code "128") (name "Net-(U35-B(2))") (class "Default")
      (node (ref "R87") (pin "2") (pinfunction "2_2") (pintype "passive"))
      (node (ref "U35") (pin "1") (pinfunction "B(2)_1") (pintype "input"))
    )
    (net (code "129") (name "Net-(U36-B(2))") (class "Default")
      (node (ref "R88") (pin "2") (pinfunction "2_2") (pintype "passive"))
      (node (ref "U36") (pin "1") (pinfunction "B(2)_1") (pintype "input"))
    )
    (net (code "130") (name "Net-(U37-B(2))") (class "Default")
      (node (ref "R92") (pin "2") (pinfunction "2_2") (pintype "passive"))
      (node (ref "U37") (pin "1") (pinfunction "B(2)_1") (pintype "input"))
    )
    (net (code "131") (name "Net-(U38-B(2))") (class "Default")
      (node (ref "R93") (pin "2") (pinfunction "2_2") (pintype "passive"))
      (node (ref "U38") (pin "1") (pinfunction "B(2)_1") (pintype "input"))
    )
    (net (code "132") (name "Net-(U39-B(2))") (class "Default")
      (node (ref "R94") (pin "2") (pinfunction "2_2") (pintype "passive"))
      (node (ref "U39") (pin "1") (pinfunction "B(2)_1") (pintype "input"))
    )
    (net (code "133") (name "Net-(U46-B(2))") (class "Default")
      (node (ref "R110") (pin "2") (pinfunction "2_2") (pintype "passive"))
      (node (ref "U46") (pin "1") (pinfunction "B(2)_1") (pintype "input"))
    )
    (net (code "134") (name "Net-(U47-B(2))") (class "Default")
      (node (ref "R111") (pin "2") (pinfunction "2_2") (pintype "passive"))
      (node (ref "U47") (pin "1") (pinfunction "B(2)_1") (pintype "input"))
    )
    (net (code "135") (name "Net-(U48-B(2))") (class "Default")
      (node (ref "R112") (pin "2") (pinfunction "2_2") (pintype "passive"))
      (node (ref "U48") (pin "1") (pinfunction "B(2)_1") (pintype "input"))
    )
    (net (code "136") (name "Net-(U49-B(2))") (class "Default")
      (node (ref "R116") (pin "2") (pinfunction "2_2") (pintype "passive"))
      (node (ref "U49") (pin "1") (pinfunction "B(2)_1") (pintype "input"))
    )
    (net (code "137") (name "Net-(U50-B(2))") (class "Default")
      (node (ref "R117") (pin "2") (pinfunction "2_2") (pintype "passive"))
      (node (ref "U50") (pin "1") (pinfunction "B(2)_1") (pintype "input"))
    )
    (net (code "138") (name "Net-(U51-B(2))") (class "Default")
      (node (ref "R118") (pin "2") (pinfunction "2_2") (pintype "passive"))
      (node (ref "U51") (pin "1") (pinfunction "B(2)_1") (pintype "input"))
    )
    (net (code "139") (name "Net-(U58-B(2))") (class "Default")
      (node (ref "R134") (pin "2") (pinfunction "2_2") (pintype "passive"))
      (node (ref "U58") (pin "1") (pinfunction "B(2)_1") (pintype "input"))
    )
    (net (code "140") (name "Net-(U59-B(2))") (class "Default")
      (node (ref "R135") (pin "2") (pinfunction "2_2") (pintype "passive"))
      (node (ref "U59") (pin "1") (pinfunction "B(2)_1") (pintype "input"))
    )
    (net (code "141") (name "Net-(U60-B(2))") (class "Default")
      (node (ref "R136") (pin "2") (pinfunction "2_2") (pintype "passive"))
      (node (ref "U60") (pin "1") (pinfunction "B(2)_1") (pintype "input"))
    )
    (net (code "142") (name "Net-(U61-B(2))") (class "Default")
      (node (ref "R140") (pin "2") (pinfunction "2_2") (pintype "passive"))
      (node (ref "U61") (pin "1") (pinfunction "B(2)_1") (pintype "input"))
    )
    (net (code "143") (name "Net-(U62-B(2))") (class "Default")
      (node (ref "R141") (pin "2") (pinfunction "2_2") (pintype "passive"))
      (node (ref "U62") (pin "1") (pinfunction "B(2)_1") (pintype "input"))
    )
    (net (code "144") (name "Net-(U63-B(2))") (class "Default")
      (node (ref "R142") (pin "2") (pinfunction "2_2") (pintype "passive"))
      (node (ref "U63") (pin "1") (pinfunction "B(2)_1") (pintype "input"))
    )
    (net (code "145") (name "Net-(U70-B(2))") (class "Default")
      (node (ref "R158") (pin "2") (pinfunction "2_2") (pintype "passive"))
      (node (ref "U70") (pin "1") (pinfunction "B(2)_1") (pintype "input"))
    )
    (net (code "146") (name "Net-(U71-B(2))") (class "Default")
      (node (ref "R159") (pin "2") (pinfunction "2_2") (pintype "passive"))
      (node (ref "U71") (pin "1") (pinfunction "B(2)_1") (pintype "input"))
    )
    (net (code "147") (name "Net-(U72-B(2))") (class "Default")
      (node (ref "R160") (pin "2") (pinfunction "2_2") (pintype "passive"))
      (node (ref "U72") (pin "1") (pinfunction "B(2)_1") (pintype "input"))
    )
    (net (code "148") (name "Net-(U73-B(2))") (class "Default")
      (node (ref "R164") (pin "2") (pinfunction "2_2") (pintype "passive"))
      (node (ref "U73") (pin "1") (pinfunction "B(2)_1") (pintype "input"))
    )
    (net (code "149") (name "Net-(U74-B(2))") (class "Default")
      (node (ref "R165") (pin "2") (pinfunction "2_2") (pintype "passive"))
      (node (ref "U74") (pin "1") (pinfunction "B(2)_1") (pintype "input"))
    )
    (net (code "150") (name "Net-(U75-B(2))") (class "Default")
      (node (ref "R166") (pin "2") (pinfunction "2_2") (pintype "passive"))
      (node (ref "U75") (pin "1") (pinfunction "B(2)_1") (pintype "input"))
    )
    (net (code "151") (name "P0_00") (class "Default")
      (node (ref "J4") (pin "P$2") (pinfunction "P$2_P$2") (pintype "bidirectional"))
      (node (ref "U3") (pin "169") (pinfunction "P0_0/AN0\\00_169") (pintype "bidirectional"))
    )
    (net (code "152") (name "P0_01") (class "Default")
      (node (ref "J4") (pin "P$1") (pinfunction "P$1_P$1") (pintype "bidirectional"))
      (node (ref "U3") (pin "168") (pinfunction "P0_1/AN001_168") (pintype "bidirectional"))
    )
    (net (code "153") (name "P0_02") (class "Default")
      (node (ref "J39") (pin "P$20") (pinfunction "P$20_P$20") (pintype "bidirectional"))
      (node (ref "R25") (pin "P$1") (pinfunction "1_P$1") (pintype "passive"))
      (node (ref "U3") (pin "167") (pinfunction "P0_2/AN002_167") (pintype "bidirectional"))
    )
    (net (code "154") (name "P0_03") (class "Default")
      (node (ref "J39") (pin "P$18") (pinfunction "P$18_P$18") (pintype "bidirectional"))
      (node (ref "R26") (pin "P$1") (pinfunction "1_P$1") (pintype "passive"))
      (node (ref "U3") (pin "166") (pinfunction "P0_3/PGAVSS000_166") (pintype "bidirectional"))
    )
    (net (code "155") (name "P0_04") (class "Default")
      (node (ref "J39") (pin "P$16") (pinfunction "P$16_P$16") (pintype "bidirectional"))
      (node (ref "R27") (pin "P$1") (pinfunction "1_P$1") (pintype "passive"))
      (node (ref "U3") (pin "165") (pinfunction "P0_4/AN100_165") (pintype "bidirectional"))
    )
    (net (code "156") (name "P0_05") (class "Default")
      (node (ref "J39") (pin "P$14") (pinfunction "P$14_P$14") (pintype "bidirectional"))
      (node (ref "R102") (pin "P$1") (pinfunction "1_P$1") (pintype "passive"))
      (node (ref "U3") (pin "164") (pinfunction "P0_5/AN101_164") (pintype "bidirectional"))
    )
    (net (code "157") (name "P0_06") (class "Default")
      (node (ref "J39") (pin "P$12") (pinfunction "P$12_P$12") (pintype "bidirectional"))
      (node (ref "R103") (pin "P$1") (pinfunction "1_P$1") (pintype "passive"))
      (node (ref "U3") (pin "163") (pinfunction "P0_6/AN102_163") (pintype "bidirectional"))
    )
    (net (code "158") (name "P0_07") (class "Default")
      (node (ref "J39") (pin "P$10") (pinfunction "P$10_P$10") (pintype "bidirectional"))
      (node (ref "R104") (pin "P$1") (pinfunction "1_P$1") (pintype "passive"))
      (node (ref "U3") (pin "162") (pinfunction "P0_7/PGVSS100_162") (pintype "bidirectional"))
    )
    (net (code "159") (name "P0_08") (class "Default")
      (node (ref "J39") (pin "P$8") (pinfunction "P$8_P$8") (pintype "bidirectional"))
      (node (ref "R105") (pin "P$1") (pinfunction "1_P$1") (pintype "passive"))
      (node (ref "U3") (pin "161") (pinfunction "P0_8/AN003_161") (pintype "bidirectional"))
    )
    (net (code "160") (name "P0_09") (class "Default")
      (node (ref "J39") (pin "P$6") (pinfunction "P$6_P$6") (pintype "bidirectional"))
      (node (ref "R106") (pin "P$1") (pinfunction "1_P$1") (pintype "passive"))
      (node (ref "U3") (pin "160") (pinfunction "P0_9/AN004_160") (pintype "bidirectional"))
    )
    (net (code "161") (name "P0_14") (class "Default")
      (node (ref "J39") (pin "P$4") (pinfunction "P$4_P$4") (pintype "bidirectional"))
      (node (ref "R107") (pin "P$1") (pinfunction "1_P$1") (pintype "passive"))
      (node (ref "U3") (pin "152") (pinfunction "P0_14/DA0/AN005/AN105_152") (pintype "bidirectional"))
    )
    (net (code "162") (name "P0_15") (class "Default")
      (node (ref "J39") (pin "P$2") (pinfunction "P$2_P$2") (pintype "bidirectional"))
      (node (ref "R108") (pin "P$1") (pinfunction "1_P$1") (pintype "passive"))
      (node (ref "U3") (pin "151") (pinfunction "P0_15/DA1/AN006/AN106_151") (pintype "bidirectional"))
    )
    (net (code "163") (name "P1_02") (class "Default")
      (node (ref "J8") (pin "P$10") (pinfunction "P$10_P$10") (pintype "bidirectional"))
      (node (ref "U3") (pin "130") (pinfunction "P1_2_130") (pintype "bidirectional"))
    )
    (net (code "164") (name "P1_03") (class "Default")
      (node (ref "J8") (pin "P$9") (pinfunction "P$9_P$9") (pintype "bidirectional"))
      (node (ref "U3") (pin "129") (pinfunction "P1_3_129") (pintype "bidirectional"))
    )
    (net (code "165") (name "P1_04") (class "Default")
      (node (ref "J8") (pin "P$11") (pinfunction "P$11_P$11") (pintype "bidirectional"))
      (node (ref "U3") (pin "128") (pinfunction "P1_4_128") (pintype "bidirectional"))
    )
    (net (code "166") (name "P1_05") (class "Default")
      (node (ref "J8") (pin "P$13") (pinfunction "P$13_P$13") (pintype "bidirectional"))
      (node (ref "U3") (pin "127") (pinfunction "P1_5_127") (pintype "bidirectional"))
    )
    (net (code "167") (name "P1_06") (class "Default")
      (node (ref "J8") (pin "P$15") (pinfunction "P$15_P$15") (pintype "bidirectional"))
      (node (ref "U3") (pin "126") (pinfunction "P1_6_126") (pintype "bidirectional"))
    )
    (net (code "168") (name "P1_07") (class "Default")
      (node (ref "J8") (pin "P$17") (pinfunction "P$17_P$17") (pintype "bidirectional"))
      (node (ref "U3") (pin "125") (pinfunction "P1_7_125") (pintype "bidirectional"))
    )
    (net (code "169") (name "P4_00") (class "Default")
      (node (ref "J4") (pin "P$7") (pinfunction "P$7_P$7") (pintype "bidirectional"))
      (node (ref "U3") (pin "1") (pinfunction "P4_0_1") (pintype "bidirectional"))
    )
    (net (code "170") (name "P4_01") (class "Default")
      (node (ref "J4") (pin "P$8") (pinfunction "P$8_P$8") (pintype "bidirectional"))
      (node (ref "U3") (pin "2") (pinfunction "P4_1_2") (pintype "bidirectional"))
    )
    (net (code "171") (name "P4_02") (class "Default")
      (node (ref "J4") (pin "P$9") (pinfunction "P$9_P$9") (pintype "bidirectional"))
      (node (ref "U3") (pin "3") (pinfunction "P4_2_3") (pintype "bidirectional"))
    )
    (net (code "172") (name "P4_08") (class "Default")
      (node (ref "J4") (pin "P$20") (pinfunction "P$20_P$20") (pintype "bidirectional"))
      (node (ref "U3") (pin "43") (pinfunction "P4_8_43") (pintype "bidirectional"))
    )
    (net (code "173") (name "P4_09") (class "Default")
      (node (ref "J4") (pin "P$19") (pinfunction "P$19_P$19") (pintype "bidirectional"))
      (node (ref "U3") (pin "42") (pinfunction "P4_9_42") (pintype "bidirectional"))
    )
    (net (code "174") (name "P4_10") (class "Default")
      (node (ref "J4") (pin "P$18") (pinfunction "P$18_P$18") (pintype "bidirectional"))
      (node (ref "U3") (pin "41") (pinfunction "P4_10_41") (pintype "bidirectional"))
    )
    (net (code "175") (name "P4_11") (class "Default")
      (node (ref "J4") (pin "P$17") (pinfunction "P$17_P$17") (pintype "bidirectional"))
      (node (ref "U3") (pin "40") (pinfunction "P4_11_40") (pintype "bidirectional"))
    )
    (net (code "176") (name "P4_12") (class "Default")
      (node (ref "J4") (pin "P$16") (pinfunction "P$16_P$16") (pintype "bidirectional"))
      (node (ref "U3") (pin "39") (pinfunction "P4_12_39") (pintype "bidirectional"))
    )
    (net (code "177") (name "P4_13") (class "Default")
      (node (ref "J4") (pin "P$15") (pinfunction "P$15_P$15") (pintype "bidirectional"))
      (node (ref "U3") (pin "38") (pinfunction "P4_13_38") (pintype "bidirectional"))
    )
    (net (code "178") (name "P4_14") (class "Default")
      (node (ref "J4") (pin "P$14") (pinfunction "P$14_P$14") (pintype "bidirectional"))
      (node (ref "U3") (pin "37") (pinfunction "P4_14_37") (pintype "bidirectional"))
    )
    (net (code "179") (name "P4_15") (class "Default")
      (node (ref "J4") (pin "P$13") (pinfunction "P$13_P$13") (pintype "bidirectional"))
      (node (ref "U3") (pin "36") (pinfunction "P4_15_36") (pintype "bidirectional"))
    )
    (net (code "180") (name "P5_11") (class "Default")
      (node (ref "J4") (pin "P$6") (pinfunction "P$6_P$6") (pintype "bidirectional"))
      (node (ref "U3") (pin "176") (pinfunction "P5_11_176") (pintype "bidirectional"))
    )
    (net (code "181") (name "P5_12") (class "Default")
      (node (ref "J4") (pin "P$5") (pinfunction "P$5_P$5") (pintype "bidirectional"))
      (node (ref "U3") (pin "175") (pinfunction "P5_12_175") (pintype "bidirectional"))
    )
    (net (code "182") (name "P5_13") (class "Default")
      (node (ref "J4") (pin "P$4") (pinfunction "P$4_P$4") (pintype "bidirectional"))
      (node (ref "U3") (pin "174") (pinfunction "P5_13_174") (pintype "bidirectional"))
    )
    (net (code "183") (name "P6_00") (class "Default")
      (node (ref "J8") (pin "P$19") (pinfunction "P$19_P$19") (pintype "bidirectional"))
      (node (ref "U3") (pin "122") (pinfunction "P6_0_122") (pintype "bidirectional"))
    )
    (net (code "184") (name "P7_06") (class "Default")
      (node (ref "J4") (pin "P$10") (pinfunction "P$10_P$10") (pintype "bidirectional"))
      (node (ref "U3") (pin "14") (pinfunction "P7_6_14") (pintype "bidirectional"))
    )
    (net (code "185") (name "P7_07") (class "Default")
      (node (ref "J4") (pin "P$11") (pinfunction "P$11_P$11") (pintype "bidirectional"))
      (node (ref "U3") (pin "15") (pinfunction "P7_7_15") (pintype "bidirectional"))
    )
    (net (code "186") (name "P8_00") (class "Default")
      (node (ref "J8") (pin "P$5") (pinfunction "P$5_P$5") (pintype "bidirectional"))
      (node (ref "U3") (pin "133") (pinfunction "P8_0_133") (pintype "bidirectional"))
    )
    (net (code "187") (name "P8_01") (class "Default")
      (node (ref "J8") (pin "P$3") (pinfunction "P$3_P$3") (pintype "bidirectional"))
      (node (ref "U3") (pin "134") (pinfunction "P8_1_134") (pintype "bidirectional"))
    )
    (net (code "188") (name "P8_02") (class "Default")
      (node (ref "J8") (pin "P$4") (pinfunction "P$4_P$4") (pintype "bidirectional"))
      (node (ref "U3") (pin "135") (pinfunction "P8_2_135") (pintype "bidirectional"))
    )
    (net (code "189") (name "P8_03") (class "Default")
      (node (ref "J8") (pin "P$1") (pinfunction "P$1_P$1") (pintype "bidirectional"))
      (node (ref "U3") (pin "136") (pinfunction "P8_3_136") (pintype "bidirectional"))
    )
    (net (code "190") (name "P8_04") (class "Default")
      (node (ref "J8") (pin "P$2") (pinfunction "P$2_P$2") (pintype "bidirectional"))
      (node (ref "U3") (pin "137") (pinfunction "P8_4_137") (pintype "bidirectional"))
    )
    (net (code "191") (name "P8_05") (class "Default")
      (node (ref "J4") (pin "P$3") (pinfunction "P$3_P$3") (pintype "bidirectional"))
      (node (ref "U3") (pin "173") (pinfunction "P8_5_173") (pintype "bidirectional"))
    )
    (net (code "192") (name "PB_00") (class "Default")
      (node (ref "J4") (pin "P$12") (pinfunction "P$12_P$12") (pintype "bidirectional"))
      (node (ref "U3") (pin "16") (pinfunction "PB_0_16") (pintype "bidirectional"))
    )
    (net (code "193") (name "R51") (class "Default")
      (node (ref "R7") (pin "P$1") (pinfunction "1_P$1") (pintype "passive"))
      (node (ref "RJ1") (pin "12") (pinfunction "YHI_12") (pintype "bidirectional"))
    )
    (net (code "194") (name "R52") (class "Default")
      (node (ref "R8") (pin "P$1") (pinfunction "1_P$1") (pintype "passive"))
      (node (ref "RJ1") (pin "9") (pinfunction "GHI_9") (pintype "bidirectional"))
    )
    (net (code "195") (name "RELAY_1") (class "Default")
      (node (ref "R29") (pin "P$1") (pinfunction "1_P$1") (pintype "passive"))
      (node (ref "U3") (pin "56") (pinfunction "P3_14_56") (pintype "bidirectional"))
    )
    (net (code "196") (name "RELAY_2") (class "Default")
      (node (ref "R30") (pin "P$1") (pinfunction "1_P$1") (pintype "passive"))
      (node (ref "U3") (pin "55") (pinfunction "P3_13_55") (pintype "bidirectional"))
    )
    (net (code "197") (name "RELAY_3") (class "Default")
      (node (ref "R49") (pin "P$1") (pinfunction "1_P$1") (pintype "passive"))
      (node (ref "U3") (pin "52") (pinfunction "P2_4_52") (pintype "bidirectional"))
    )
    (net (code "198") (name "RELAY_4") (class "Default")
      (node (ref "R50") (pin "P$1") (pinfunction "1_P$1") (pintype "passive"))
      (node (ref "U3") (pin "49") (pinfunction "P2_7_49") (pintype "bidirectional"))
    )
    (net (code "199") (name "RESET") (class "Default")
      (node (ref "C16") (pin "P$1") (pinfunction "1_P$1") (pintype "passive"))
      (node (ref "J3") (pin "9") (pinfunction "9_9") (pintype "passive"))
      (node (ref "R13") (pin "P$1") (pinfunction "1_P$1") (pintype "passive"))
      (node (ref "U3") (pin "67") (pinfunction "RES#_67") (pintype "bidirectional"))
    )
    (net (code "200") (name "REXT") (class "Default")
      (node (ref "C3") (pin "P$1") (pinfunction "1_P$1") (pintype "passive"))
      (node (ref "R1") (pin "P$2") (pinfunction "2_P$2") (pintype "passive"))
      (node (ref "U1") (pin "9") (pinfunction "REXT_9") (pintype "input"))
    )
    (net (code "201") (name "RO_NEG_1") (class "Default")
      (node (ref "J15") (pin "P$2") (pinfunction "P$2_P$2") (pintype "bidirectional"))
      (node (ref "U$1") (pin "P$3") (pinfunction "VO-_P$3") (pintype "bidirectional"))
    )
    (net (code "202") (name "RO_NEG_2") (class "Default")
      (node (ref "J16") (pin "P$2") (pinfunction "P$2_P$2") (pintype "bidirectional"))
      (node (ref "U$2") (pin "P$3") (pinfunction "VO-_P$3") (pintype "bidirectional"))
    )
    (net (code "203") (name "RO_NEG_3") (class "Default")
      (node (ref "J23") (pin "P$2") (pinfunction "P$2_P$2") (pintype "bidirectional"))
      (node (ref "U$7") (pin "P$3") (pinfunction "VO-_P$3") (pintype "bidirectional"))
    )
    (net (code "204") (name "RO_NEG_4") (class "Default")
      (node (ref "J24") (pin "P$2") (pinfunction "P$2_P$2") (pintype "bidirectional"))
      (node (ref "U$8") (pin "P$3") (pinfunction "VO-_P$3") (pintype "bidirectional"))
    )
    (net (code "205") (name "RO_POS_1") (class "Default")
      (node (ref "J15") (pin "P$1") (pinfunction "P$1_P$1") (pintype "bidirectional"))
      (node (ref "U$1") (pin "P$4") (pinfunction "VO+_P$4") (pintype "bidirectional"))
    )
    (net (code "206") (name "RO_POS_2") (class "Default")
      (node (ref "J16") (pin "P$1") (pinfunction "P$1_P$1") (pintype "bidirectional"))
      (node (ref "U$2") (pin "P$4") (pinfunction "VO+_P$4") (pintype "bidirectional"))
    )
    (net (code "207") (name "RO_POS_3") (class "Default")
      (node (ref "J23") (pin "P$1") (pinfunction "P$1_P$1") (pintype "bidirectional"))
      (node (ref "U$7") (pin "P$4") (pinfunction "VO+_P$4") (pintype "bidirectional"))
    )
    (net (code "208") (name "RO_POS_4") (class "Default")
      (node (ref "J24") (pin "P$1") (pinfunction "P$1_P$1") (pintype "bidirectional"))
      (node (ref "U$8") (pin "P$4") (pinfunction "VO+_P$4") (pintype "bidirectional"))
    )
    (net (code "209") (name "RXD0") (class "Default")
      (node (ref "R10") (pin "P$2") (pinfunction "2_P$2") (pintype "passive"))
      (node (ref "U1") (pin "13") (pinfunction "RXD0_13") (pintype "bidirectional"))
    )
    (net (code "210") (name "RXD1") (class "Default")
      (node (ref "R9") (pin "P$2") (pinfunction "2_P$2") (pintype "passive"))
      (node (ref "U1") (pin "12") (pinfunction "RXD1_12") (pintype "bidirectional"))
    )
    (net (code "211") (name "RXER") (class "Default")
      (node (ref "R11") (pin "P$2") (pinfunction "2_P$2") (pintype "passive"))
      (node (ref "U1") (pin "17") (pinfunction "RXER_17") (pintype "bidirectional"))
    )
    (net (code "212") (name "RXM") (class "Default")
      (node (ref "RJ1") (pin "6") (pinfunction "RD-_6") (pintype "bidirectional"))
      (node (ref "U1") (pin "3") (pinfunction "RXM_3") (pintype "bidirectional"))
    )
    (net (code "213") (name "RXP") (class "Default")
      (node (ref "RJ1") (pin "3") (pinfunction "RD+_3") (pintype "bidirectional"))
      (node (ref "U1") (pin "4") (pinfunction "RXP_4") (pintype "bidirectional"))
    )
    (net (code "214") (name "SD1_CD") (class "Default")
      (node (ref "J1") (pin "10") (pinfunction "CD_SWITCH2_10") (pintype "bidirectional"))
      (node (ref "U3") (pin "146") (pinfunction "P5_6/AN019_146") (pintype "bidirectional"))
    )
    (net (code "215") (name "SD1_CLK") (class "Default")
      (node (ref "J1") (pin "5") (pinfunction "CLOCK_5") (pintype "bidirectional"))
      (node (ref "U3") (pin "140") (pinfunction "P5_0/AN016_140") (pintype "bidirectional"))
    )
    (net (code "216") (name "SD1_CMD") (class "Default")
      (node (ref "J1") (pin "3") (pinfunction "COMMAND/RESPONSE_3") (pintype "bidirectional"))
      (node (ref "U3") (pin "141") (pinfunction "P5_1/AN116_141") (pintype "bidirectional"))
    )
    (net (code "217") (name "SD1_DAT0") (class "Default")
      (node (ref "J1") (pin "7") (pinfunction "DATA_LINE[BIT_0]_7") (pintype "bidirectional"))
      (node (ref "U3") (pin "142") (pinfunction "P5_2/AN017_142") (pintype "bidirectional"))
    )
    (net (code "218") (name "SD1_DAT1") (class "Default")
      (node (ref "J1") (pin "8") (pinfunction "DATA_LINE[BIT_1]_8") (pintype "bidirectional"))
      (node (ref "U3") (pin "143") (pinfunction "P5_3/AN117_143") (pintype "bidirectional"))
    )
    (net (code "219") (name "SD1_DAT2") (class "Default")
      (node (ref "J1") (pin "1") (pinfunction "DATA_LINE[BIT_2]_1") (pintype "bidirectional"))
      (node (ref "U3") (pin "144") (pinfunction "P5_4/AN018_144") (pintype "bidirectional"))
    )
    (net (code "220") (name "SD1_DAT3") (class "Default")
      (node (ref "J1") (pin "2") (pinfunction "CARD_DETECT/DATA_LINE[BIT_3]_2") (pintype "bidirectional"))
      (node (ref "U3") (pin "145") (pinfunction "P5_5/AN118_145") (pintype "bidirectional"))
    )
    (net (code "221") (name "SD1_WP") (class "Default")
      (node (ref "J1") (pin "9") (pinfunction "CD_SWITCH1_9") (pintype "bidirectional"))
      (node (ref "U3") (pin "147") (pinfunction "P5_7/AN119_147") (pintype "bidirectional"))
    )
    (net (code "222") (name "TCK") (class "Default")
      (node (ref "J3") (pin "7") (pinfunction "7_7") (pintype "passive"))
      (node (ref "U3") (pin "88") (pinfunction "P3_0_88") (pintype "bidirectional"))
    )
    (net (code "223") (name "TDI") (class "Default")
      (node (ref "J3") (pin "1") (pinfunction "1_1") (pintype "passive"))
      (node (ref "U3") (pin "91") (pinfunction "P1_10_91") (pintype "bidirectional"))
    )
    (net (code "224") (name "TDO") (class "Default")
      (node (ref "J3") (pin "3") (pinfunction "3_3") (pintype "passive"))
      (node (ref "U3") (pin "90") (pinfunction "P1_9_90") (pintype "bidirectional"))
    )
    (net (code "225") (name "TMS") (class "Default")
      (node (ref "J3") (pin "5") (pinfunction "5_5") (pintype "passive"))
      (node (ref "U3") (pin "89") (pinfunction "P1_8_89") (pintype "bidirectional"))
    )
    (net (code "226") (name "TXM") (class "Default")
      (node (ref "RJ1") (pin "2") (pinfunction "TD-_2") (pintype "bidirectional"))
      (node (ref "U1") (pin "5") (pinfunction "TXM_5") (pintype "bidirectional"))
    )
    (net (code "227") (name "TXP") (class "Default")
      (node (ref "RJ1") (pin "1") (pinfunction "TD+_1") (pintype "bidirectional"))
      (node (ref "U1") (pin "6") (pinfunction "TXP_6") (pintype "bidirectional"))
    )
    (net (code "228") (name "USBHS_FAULT") (class "Default")
      (node (ref "R19") (pin "P$1") (pinfunction "1_P$1") (pintype "passive"))
      (node (ref "U2") (pin "3") (pinfunction "FLG_3") (pintype "input"))
      (node (ref "U3") (pin "78") (pinfunction "P3_8_78") (pintype "bidirectional"))
    )
    (net (code "229") (name "USBHS_N") (class "Default")
      (node (ref "J6") (pin "D-") (pinfunction "D-_D-") (pintype "bidirectional"))
      (node (ref "U3") (pin "31") (pinfunction "USBHS_DM_31") (pintype "bidirectional"))
    )
    (net (code "230") (name "USBHS_P") (class "Default")
      (node (ref "J6") (pin "D+") (pinfunction "D+_D+") (pintype "bidirectional"))
      (node (ref "U3") (pin "32") (pinfunction "USBHS_DP_32") (pintype "bidirectional"))
    )
    (net (code "231") (name "USBHS_VBUS") (class "Default")
      (node (ref "C29") (pin "P$1") (pinfunction "1_P$1") (pintype "passive"))
      (node (ref "C31") (pin "1") (pinfunction "1_1") (pintype "passive"))
      (node (ref "J6") (pin "VBUS") (pinfunction "VBUS_VBUS") (pintype "power_in"))
      (node (ref "U2") (pin "5") (pinfunction "OUT_5") (pintype "input"))
      (node (ref "U3") (pin "17") (pinfunction "PB_1_17") (pintype "bidirectional"))
    )
    (net (code "232") (name "USBHS_VBUSEN") (class "Default")
      (node (ref "R20") (pin "P$1") (pinfunction "1_P$1") (pintype "passive"))
      (node (ref "U2") (pin "1") (pinfunction "EN_1") (pintype "input"))
    )
    (net (code "233") (name "USB_N") (class "Default")
      (node (ref "R17") (pin "P$1") (pinfunction "1_P$1") (pintype "passive"))
      (node (ref "U3") (pin "46") (pinfunction "USB_DM_46") (pintype "bidirectional"))
    )
    (net (code "234") (name "USB_P") (class "Default")
      (node (ref "R18") (pin "P$1") (pinfunction "1_P$1") (pintype "passive"))
      (node (ref "U3") (pin "47") (pinfunction "USB_DP_47") (pintype "bidirectional"))
    )
    (net (code "235") (name "USB_VBUS_B") (class "Default")
      (node (ref "R16") (pin "P$1") (pinfunction "1_P$1") (pintype "passive"))
      (node (ref "U3") (pin "44") (pinfunction "P4_7_44") (pintype "bidirectional"))
    )
    (net (code "236") (name "VCL_F(FLASH)") (class "Default")
      (node (ref "C34") (pin "P$2") (pinfunction "2_P$2") (pintype "passive"))
      (node (ref "U3") (pin "112") (pinfunction "VCL_F(FLASH)_112") (pintype "bidirectional"))
    )
    (net (code "237") (name "VDD") (class "Default")
      (node (ref "C14") (pin "P$1") (pinfunction "1_P$1") (pintype "passive"))
      (node (ref "C15") (pin "P$1") (pinfunction "1_P$1") (pintype "passive"))
      (node (ref "C19") (pin "P$2") (pinfunction "2_P$2") (pintype "passive"))
      (node (ref "C20") (pin "P$2") (pinfunction "2_P$2") (pintype "passive"))
      (node (ref "C21") (pin "P$2") (pinfunction "2_P$2") (pintype "passive"))
      (node (ref "C22") (pin "P$2") (pinfunction "2_P$2") (pintype "passive"))
      (node (ref "C25") (pin "P$2") (pinfunction "2_P$2") (pintype "passive"))
      (node (ref "C27") (pin "P$2") (pinfunction "2_P$2") (pintype "passive"))
      (node (ref "C30") (pin "P$2") (pinfunction "2_P$2") (pintype "passive"))
      (node (ref "C35") (pin "P$2") (pinfunction "2_P$2") (pintype "passive"))
      (node (ref "C36") (pin "P$1") (pinfunction "1_P$1") (pintype "passive"))
      (node (ref "C38") (pin "P$2") (pinfunction "2_P$2") (pintype "passive"))
      (node (ref "C39") (pin "P$1") (pinfunction "1_P$1") (pintype "passive"))
      (node (ref "C4") (pin "P$1") (pinfunction "1_P$1") (pintype "passive"))
      (node (ref "C40") (pin "P$1") (pinfunction "1_P$1") (pintype "passive"))
      (node (ref "C41") (pin "P$1") (pinfunction "1_P$1") (pintype "passive"))
      (node (ref "C43") (pin "P$2") (pinfunction "2_P$2") (pintype "passive"))
      (node (ref "C5") (pin "P$1") (pinfunction "1_P$1") (pintype "passive"))
      (node (ref "C7") (pin "P$1") (pinfunction "1_P$1") (pintype "passive"))
      (node (ref "FB1") (pin "1") (pinfunction "P$1_1") (pintype "bidirectional"))
      (node (ref "J1") (pin "4") (pinfunction "SUPPLY_VOLTAGE_4") (pintype "power_in"))
      (node (ref "J3") (pin "2") (pinfunction "2_2") (pintype "passive"))
      (node (ref "J3") (pin "4") (pinfunction "4_4") (pintype "passive"))
      (node (ref "L1") (pin "2") (pinfunction "P$2_2") (pintype "bidirectional"))
      (node (ref "R102") (pin "P$2") (pinfunction "2_P$2") (pintype "passive"))
      (node (ref "R103") (pin "P$2") (pinfunction "2_P$2") (pintype "passive"))
      (node (ref "R104") (pin "P$2") (pinfunction "2_P$2") (pintype "passive"))
      (node (ref "R105") (pin "P$2") (pinfunction "2_P$2") (pintype "passive"))
      (node (ref "R106") (pin "P$2") (pinfunction "2_P$2") (pintype "passive"))
      (node (ref "R107") (pin "P$2") (pinfunction "2_P$2") (pintype "passive"))
      (node (ref "R108") (pin "P$2") (pinfunction "2_P$2") (pintype "passive"))
      (node (ref "R13") (pin "P$2") (pinfunction "2_P$2") (pintype "passive"))
      (node (ref "R14") (pin "P$1") (pinfunction "1_P$1") (pintype "passive"))
      (node (ref "R15") (pin "P$1") (pinfunction "1_P$1") (pintype "passive"))
      (node (ref "R2") (pin "P$2") (pinfunction "2_P$2") (pintype "passive"))
      (node (ref "R25") (pin "P$2") (pinfunction "2_P$2") (pintype "passive"))
      (node (ref "R26") (pin "P$2") (pinfunction "2_P$2") (pintype "passive"))
      (node (ref "R27") (pin "P$2") (pinfunction "2_P$2") (pintype "passive"))
      (node (ref "R3") (pin "P$2") (pinfunction "2_P$2") (pintype "passive"))
      (node (ref "R4") (pin "P$2") (pinfunction "2_P$2") (pintype "passive"))
      (node (ref "R5") (pin "P$2") (pinfunction "2_P$2") (pintype "passive"))
      (node (ref "R6") (pin "P$2") (pinfunction "2_P$2") (pintype "passive"))
      (node (ref "R7") (pin "P$2") (pinfunction "2_P$2") (pintype "passive"))
      (node (ref "R8") (pin "P$2") (pinfunction "2_P$2") (pintype "passive"))
      (node (ref "U1") (pin "14") (pinfunction "VDDIO_14") (pintype "power_in"))
      (node (ref "U18") (pin "3") (pinfunction "C(3)_3") (pintype "input"))
      (node (ref "U19") (pin "3") (pinfunction "C(3)_3") (pintype "input"))
      (node (ref "U20") (pin "3") (pinfunction "C(3)_3") (pintype "input"))
      (node (ref "U21") (pin "3") (pinfunction "C(3)_3") (pintype "input"))
      (node (ref "U28") (pin "3") (pinfunction "C(3)_3") (pintype "input"))
      (node (ref "U29") (pin "3") (pinfunction "C(3)_3") (pintype "input"))
      (node (ref "U3") (pin "110") (pinfunction "VCC(IO)5_110") (pintype "bidirectional"))
      (node (ref "U3") (pin "123") (pinfunction "VCC(IO)6_123") (pintype "bidirectional"))
      (node (ref "U3") (pin "138") (pinfunction "VCC(IO)7_138") (pintype "bidirectional"))
      (node (ref "U3") (pin "149") (pinfunction "VCC(IO)8_149") (pintype "bidirectional"))
      (node (ref "U3") (pin "154") (pinfunction "VREFH_154") (pintype "bidirectional"))
      (node (ref "U3") (pin "155") (pinfunction "AVCC0_155") (pintype "bidirectional"))
      (node (ref "U3") (pin "158") (pinfunction "VREFH0_158") (pintype "bidirectional"))
      (node (ref "U3") (pin "171") (pinfunction "VCC(IO)9_171") (pintype "bidirectional"))
      (node (ref "U3") (pin "25") (pinfunction "VCC1_25") (pintype "bidirectional"))
      (node (ref "U3") (pin "26") (pinfunction "AVCC_SUBHS_26") (pintype "bidirectional"))
      (node (ref "U3") (pin "34") (pinfunction "VCC_USBHS_34") (pintype "bidirectional"))
      (node (ref "U3") (pin "48") (pinfunction "VCC_USB_48") (pintype "bidirectional"))
      (node (ref "U3") (pin "61") (pinfunction "VCC(IO)2_61") (pintype "bidirectional"))
      (node (ref "U3") (pin "84") (pinfunction "VCC(IO)3_84") (pintype "bidirectional"))
      (node (ref "U3") (pin "97") (pinfunction "VCC(IO)4_97") (pintype "bidirectional"))
      (node (ref "U30") (pin "3") (pinfunction "C(3)_3") (pintype "input"))
      (node (ref "U5") (pin "3") (pinfunction "C(3)_3") (pintype "input"))
      (node (ref "U8") (pin "3") (pinfunction "C(3)_3") (pintype "input"))
      (node (ref "U9") (pin "3") (pinfunction "C(3)_3") (pintype "input"))
    )
    (net (code "238") (name "VDD5") (class "Default")
      (node (ref "C23") (pin "P$1") (pinfunction "1_P$1") (pintype "passive"))
      (node (ref "C26") (pin "P$1") (pinfunction "1_P$1") (pintype "passive"))
      (node (ref "J2") (pin "P$3") (pinfunction "P$3_P$3") (pintype "bidirectional"))
      (node (ref "R19") (pin "P$2") (pinfunction "2_P$2") (pintype "passive"))
      (node (ref "R20") (pin "P$2") (pinfunction "2_P$2") (pintype "passive"))
      (node (ref "R31") (pin "P$2") (pinfunction "2_P$2") (pintype "passive"))
      (node (ref "R32") (pin "P$2") (pinfunction "2_P$2") (pintype "passive"))
      (node (ref "R51") (pin "P$2") (pinfunction "2_P$2") (pintype "passive"))
      (node (ref "R52") (pin "P$2") (pinfunction "2_P$2") (pintype "passive"))
      (node (ref "U$1") (pin "P$2") (pinfunction "VC+_P$2") (pintype "bidirectional"))
      (node (ref "U$2") (pin "P$2") (pinfunction "VC+_P$2") (pintype "bidirectional"))
      (node (ref "U$7") (pin "P$2") (pinfunction "VC+_P$2") (pintype "bidirectional"))
      (node (ref "U$8") (pin "P$2") (pinfunction "VC+_P$2") (pintype "bidirectional"))
      (node (ref "U2") (pin "4") (pinfunction "VIN_4") (pintype "input"))
    )
    (net (code "239") (name "VDD12") (class "Default")
      (node (ref "J10") (pin "3") (pinfunction "3_3") (pintype "passive"))
      (node (ref "J11") (pin "3") (pinfunction "3_3") (pintype "passive"))
      (node (ref "J12") (pin "3") (pinfunction "3_3") (pintype "passive"))
      (node (ref "J13") (pin "1") (pinfunction "1-HLFB+_1") (pintype "passive"))
      (node (ref "J13") (pin "2") (pinfunction "2-INPUT_B+_2") (pintype "passive"))
      (node (ref "J13") (pin "3") (pinfunction "3-INPUT_A+_3") (pintype "passive"))
      (node (ref "J13") (pin "4") (pinfunction "4-ENABLE+_4") (pintype "passive"))
      (node (ref "J14") (pin "1") (pinfunction "1-HLFB+_1") (pintype "passive"))
      (node (ref "J14") (pin "2") (pinfunction "2-INPUT_B+_2") (pintype "passive"))
      (node (ref "J14") (pin "3") (pinfunction "3-INPUT_A+_3") (pintype "passive"))
      (node (ref "J14") (pin "4") (pinfunction "4-ENABLE+_4") (pintype "passive"))
      (node (ref "J17") (pin "1") (pinfunction "1-HLFB+_1") (pintype "passive"))
      (node (ref "J17") (pin "2") (pinfunction "2-INPUT_B+_2") (pintype "passive"))
      (node (ref "J17") (pin "3") (pinfunction "3-INPUT_A+_3") (pintype "passive"))
      (node (ref "J17") (pin "4") (pinfunction "4-ENABLE+_4") (pintype "passive"))
      (node (ref "J18") (pin "1") (pinfunction "1-HLFB+_1") (pintype "passive"))
      (node (ref "J18") (pin "2") (pinfunction "2-INPUT_B+_2") (pintype "passive"))
      (node (ref "J18") (pin "3") (pinfunction "3-INPUT_A+_3") (pintype "passive"))
      (node (ref "J18") (pin "4") (pinfunction "4-ENABLE+_4") (pintype "passive"))
      (node (ref "J19") (pin "3") (pinfunction "3_3") (pintype "passive"))
      (node (ref "J20") (pin "3") (pinfunction "3_3") (pintype "passive"))
      (node (ref "J21") (pin "1") (pinfunction "1-HLFB+_1") (pintype "passive"))
      (node (ref "J21") (pin "2") (pinfunction "2-INPUT_B+_2") (pintype "passive"))
      (node (ref "J21") (pin "3") (pinfunction "3-INPUT_A+_3") (pintype "passive"))
      (node (ref "J21") (pin "4") (pinfunction "4-ENABLE+_4") (pintype "passive"))
      (node (ref "J22") (pin "1") (pinfunction "1-HLFB+_1") (pintype "passive"))
      (node (ref "J22") (pin "2") (pinfunction "2-INPUT_B+_2") (pintype "passive"))
      (node (ref "J22") (pin "3") (pinfunction "3-INPUT_A+_3") (pintype "passive"))
      (node (ref "J22") (pin "4") (pinfunction "4-ENABLE+_4") (pintype "passive"))
      (node (ref "J25") (pin "1") (pinfunction "1-HLFB+_1") (pintype "passive"))
      (node (ref "J25") (pin "2") (pinfunction "2-INPUT_B+_2") (pintype "passive"))
      (node (ref "J25") (pin "3") (pinfunction "3-INPUT_A+_3") (pintype "passive"))
      (node (ref "J25") (pin "4") (pinfunction "4-ENABLE+_4") (pintype "passive"))
      (node (ref "J26") (pin "1") (pinfunction "1-HLFB+_1") (pintype "passive"))
      (node (ref "J26") (pin "2") (pinfunction "2-INPUT_B+_2") (pintype "passive"))
      (node (ref "J26") (pin "3") (pinfunction "3-INPUT_A+_3") (pintype "passive"))
      (node (ref "J26") (pin "4") (pinfunction "4-ENABLE+_4") (pintype "passive"))
      (node (ref "J27") (pin "3") (pinfunction "3_3") (pintype "passive"))
      (node (ref "J28") (pin "3") (pinfunction "3_3") (pintype "passive"))
      (node (ref "J29") (pin "1") (pinfunction "1-HLFB+_1") (pintype "passive"))
      (node (ref "J29") (pin "2") (pinfunction "2-INPUT_B+_2") (pintype "passive"))
      (node (ref "J29") (pin "3") (pinfunction "3-INPUT_A+_3") (pintype "passive"))
      (node (ref "J29") (pin "4") (pinfunction "4-ENABLE+_4") (pintype "passive"))
      (node (ref "J30") (pin "1") (pinfunction "1-HLFB+_1") (pintype "passive"))
      (node (ref "J30") (pin "2") (pinfunction "2-INPUT_B+_2") (pintype "passive"))
      (node (ref "J30") (pin "3") (pinfunction "3-INPUT_A+_3") (pintype "passive"))
      (node (ref "J30") (pin "4") (pinfunction "4-ENABLE+_4") (pintype "passive"))
      (node (ref "J31") (pin "3") (pinfunction "3_3") (pintype "passive"))
      (node (ref "J32") (pin "3") (pinfunction "3_3") (pintype "passive"))
      (node (ref "J33") (pin "1") (pinfunction "1-HLFB+_1") (pintype "passive"))
      (node (ref "J33") (pin "2") (pinfunction "2-INPUT_B+_2") (pintype "passive"))
      (node (ref "J33") (pin "3") (pinfunction "3-INPUT_A+_3") (pintype "passive"))
      (node (ref "J33") (pin "4") (pinfunction "4-ENABLE+_4") (pintype "passive"))
      (node (ref "J34") (pin "1") (pinfunction "1-HLFB+_1") (pintype "passive"))
      (node (ref "J34") (pin "2") (pinfunction "2-INPUT_B+_2") (pintype "passive"))
      (node (ref "J34") (pin "3") (pinfunction "3-INPUT_A+_3") (pintype "passive"))
      (node (ref "J34") (pin "4") (pinfunction "4-ENABLE+_4") (pintype "passive"))
      (node (ref "J5") (pin "3") (pinfunction "3_3") (pintype "passive"))
      (node (ref "J9") (pin "P$1") (pinfunction "P$1_P$1") (pintype "bidirectional"))
      (node (ref "J9") (pin "P$2") (pinfunction "P$2_P$2") (pintype "bidirectional"))
      (node (ref "R109") (pin "2") (pinfunction "2_2") (pintype "passive"))
      (node (ref "R113") (pin "2") (pinfunction "2_2") (pintype "passive"))
      (node (ref "R114") (pin "2") (pinfunction "2_2") (pintype "passive"))
      (node (ref "R115") (pin "2") (pinfunction "2_2") (pintype "passive"))
      (node (ref "R119") (pin "2") (pinfunction "2_2") (pintype "passive"))
      (node (ref "R120") (pin "2") (pinfunction "2_2") (pintype "passive"))
      (node (ref "R133") (pin "2") (pinfunction "2_2") (pintype "passive"))
      (node (ref "R137") (pin "2") (pinfunction "2_2") (pintype "passive"))
      (node (ref "R138") (pin "2") (pinfunction "2_2") (pintype "passive"))
      (node (ref "R139") (pin "2") (pinfunction "2_2") (pintype "passive"))
      (node (ref "R143") (pin "2") (pinfunction "2_2") (pintype "passive"))
      (node (ref "R144") (pin "2") (pinfunction "2_2") (pintype "passive"))
      (node (ref "R157") (pin "2") (pinfunction "2_2") (pintype "passive"))
      (node (ref "R161") (pin "2") (pinfunction "2_2") (pintype "passive"))
      (node (ref "R162") (pin "2") (pinfunction "2_2") (pintype "passive"))
      (node (ref "R163") (pin "2") (pinfunction "2_2") (pintype "passive"))
      (node (ref "R167") (pin "2") (pinfunction "2_2") (pintype "passive"))
      (node (ref "R168") (pin "2") (pinfunction "2_2") (pintype "passive"))
      (node (ref "R37") (pin "2") (pinfunction "2_2") (pintype "passive"))
      (node (ref "R41") (pin "2") (pinfunction "2_2") (pintype "passive"))
      (node (ref "R42") (pin "2") (pinfunction "2_2") (pintype "passive"))
      (node (ref "R43") (pin "2") (pinfunction "2_2") (pintype "passive"))
      (node (ref "R47") (pin "2") (pinfunction "2_2") (pintype "passive"))
      (node (ref "R48") (pin "2") (pinfunction "2_2") (pintype "passive"))
      (node (ref "R61") (pin "2") (pinfunction "2_2") (pintype "passive"))
      (node (ref "R65") (pin "2") (pinfunction "2_2") (pintype "passive"))
      (node (ref "R66") (pin "2") (pinfunction "2_2") (pintype "passive"))
      (node (ref "R67") (pin "2") (pinfunction "2_2") (pintype "passive"))
      (node (ref "R71") (pin "2") (pinfunction "2_2") (pintype "passive"))
      (node (ref "R72") (pin "2") (pinfunction "2_2") (pintype "passive"))
      (node (ref "R85") (pin "2") (pinfunction "2_2") (pintype "passive"))
      (node (ref "R89") (pin "2") (pinfunction "2_2") (pintype "passive"))
      (node (ref "R90") (pin "2") (pinfunction "2_2") (pintype "passive"))
      (node (ref "R91") (pin "2") (pinfunction "2_2") (pintype "passive"))
      (node (ref "R95") (pin "2") (pinfunction "2_2") (pintype "passive"))
      (node (ref "R96") (pin "2") (pinfunction "2_2") (pintype "passive"))
    )
    (net (code "240") (name "VDDIN") (class "Default")
      (node (ref "J2") (pin "P$2") (pinfunction "P$2_P$2") (pintype "bidirectional"))
      (node (ref "L1") (pin "1") (pinfunction "P$1_1") (pintype "bidirectional"))
    )
    (net (code "241") (name "VDD_1.2") (class "Default")
      (node (ref "C10") (pin "P$1") (pinfunction "1_P$1") (pintype "passive"))
      (node (ref "C11") (pin "P$1") (pinfunction "1_P$1") (pintype "passive"))
      (node (ref "U1") (pin "1") (pinfunction "VDD_1.2_1") (pintype "power_in"))
    )
    (net (code "242") (name "WF_A_DIR") (class "Default")
      (node (ref "R159") (pin "1") (pinfunction "1_1") (pintype "passive"))
      (node (ref "U3") (pin "99") (pinfunction "P6_8_99") (pintype "bidirectional"))
    )
    (net (code "243") (name "WF_A_ENABLE") (class "Default")
      (node (ref "R160") (pin "1") (pinfunction "1_1") (pintype "passive"))
      (node (ref "U3") (pin "96") (pinfunction "P1_15_96") (pintype "bidirectional"))
    )
    (net (code "244") (name "WF_A_HLFB_OUT") (class "Default")
      (node (ref "J33") (pin "5") (pinfunction "5-HLFB-_5") (pintype "passive"))
    )
    (net (code "245") (name "WF_A_MI_DIR") (class "Default")
      (node (ref "J33") (pin "7") (pinfunction "7-INPUT_A-_7") (pintype "passive"))
      (node (ref "R161") (pin "1") (pinfunction "1_1") (pintype "passive"))
      (node (ref "U71") (pin "3") (pinfunction "C(3)_3") (pintype "input"))
    )
    (net (code "246") (name "WF_A_MI_ENABLE") (class "Default")
      (node (ref "J33") (pin "8") (pinfunction "8-ENABLE-_8") (pintype "passive"))
      (node (ref "R162") (pin "1") (pinfunction "1_1") (pintype "passive"))
      (node (ref "U72") (pin "3") (pinfunction "C(3)_3") (pintype "input"))
    )
    (net (code "247") (name "WF_A_MI_STEP") (class "Default")
      (node (ref "J33") (pin "6") (pinfunction "6-INPUT_B-_6") (pintype "passive"))
      (node (ref "R157") (pin "1") (pinfunction "1_1") (pintype "passive"))
      (node (ref "U70") (pin "3") (pinfunction "C(3)_3") (pintype "input"))
    )
    (net (code "248") (name "WF_A_STEP") (class "Default")
      (node (ref "R158") (pin "1") (pinfunction "1_1") (pintype "passive"))
      (node (ref "U3") (pin "100") (pinfunction "P6_9_100") (pintype "bidirectional"))
    )
    (net (code "249") (name "WF_B_DIR") (class "Default")
      (node (ref "R165") (pin "1") (pinfunction "1_1") (pintype "passive"))
      (node (ref "U3") (pin "94") (pinfunction "P1_13_94") (pintype "bidirectional"))
    )
    (net (code "250") (name "WF_B_ENABLE") (class "Default")
      (node (ref "R166") (pin "1") (pinfunction "1_1") (pintype "passive"))
      (node (ref "U3") (pin "93") (pinfunction "P1_12_93") (pintype "bidirectional"))
    )
    (net (code "251") (name "WF_B_HLFB_OUT") (class "Default")
      (node (ref "J34") (pin "5") (pinfunction "5-HLFB-_5") (pintype "passive"))
    )
    (net (code "252") (name "WF_B_MI_ENABLE") (class "Default")
      (node (ref "J34") (pin "8") (pinfunction "8-ENABLE-_8") (pintype "passive"))
      (node (ref "R168") (pin "1") (pinfunction "1_1") (pintype "passive"))
      (node (ref "U75") (pin "3") (pinfunction "C(3)_3") (pintype "input"))
    )
    (net (code "253") (name "WF_B_MI_STEP") (class "Default")
      (node (ref "J34") (pin "6") (pinfunction "6-INPUT_B-_6") (pintype "passive"))
      (node (ref "R163") (pin "1") (pinfunction "1_1") (pintype "passive"))
      (node (ref "U73") (pin "3") (pinfunction "C(3)_3") (pintype "input"))
    )
    (net (code "254") (name "WF_B_STEP") (class "Default")
      (node (ref "R164") (pin "1") (pinfunction "1_1") (pintype "passive"))
      (node (ref "U3") (pin "95") (pinfunction "P1_14_95") (pintype "bidirectional"))
    )
    (net (code "255") (name "XCIN") (class "Default")
      (node (ref "C32") (pin "P$1") (pinfunction "1_P$1") (pintype "passive"))
      (node (ref "U3") (pin "20") (pinfunction "XCIN_20") (pintype "bidirectional"))
      (node (ref "X3") (pin "P$1") (pinfunction "P$1_P$1") (pintype "bidirectional"))
    )
    (net (code "256") (name "XCOUT") (class "Default")
      (node (ref "C37") (pin "P$1") (pinfunction "1_P$1") (pintype "passive"))
      (node (ref "U3") (pin "21") (pinfunction "XCOUT_21") (pintype "bidirectional"))
      (node (ref "X3") (pin "P$2") (pinfunction "P$2_P$2") (pintype "bidirectional"))
    )
    (net (code "257") (name "XII") (class "Default")
      (node (ref "C1") (pin "P$1") (pinfunction "1_P$1") (pintype "passive"))
      (node (ref "U1") (pin "8") (pinfunction "XI_8") (pintype "input"))
      (node (ref "X1") (pin "1") (pinfunction "1_1") (pintype "bidirectional"))
    )
    (net (code "258") (name "XOO") (class "Default")
      (node (ref "C2") (pin "P$1") (pinfunction "1_P$1") (pintype "passive"))
      (node (ref "U1") (pin "7") (pinfunction "XO_7") (pintype "output"))
      (node (ref "X1") (pin "3") (pinfunction "3_3") (pintype "bidirectional"))
    )
    (net (code "259") (name "XTAL1") (class "Default")
      (node (ref "C17") (pin "P$1") (pinfunction "1_P$1") (pintype "passive"))
      (node (ref "U3") (pin "23") (pinfunction "P2_13/XTAL_23") (pintype "bidirectional"))
      (node (ref "X2") (pin "1") (pinfunction "1_1") (pintype "bidirectional"))
    )
    (net (code "260") (name "XTAL2") (class "Default")
      (node (ref "C18") (pin "P$1") (pinfunction "1_P$1") (pintype "passive"))
      (node (ref "U3") (pin "24") (pinfunction "P2_12/EXTAL_24") (pintype "bidirectional"))
      (node (ref "X2") (pin "3") (pinfunction "3_3") (pintype "bidirectional"))
    )
    (net (code "261") (name "X_A_DIR") (class "Default")
      (node (ref "R39") (pin "1") (pinfunction "1_1") (pintype "passive"))
      (node (ref "U3") (pin "117") (pinfunction "P6_5_117") (pintype "bidirectional"))
    )
    (net (code "262") (name "X_A_ENABLE") (class "Default")
      (node (ref "R40") (pin "1") (pinfunction "1_1") (pintype "passive"))
      (node (ref "U3") (pin "116") (pinfunction "P6_6_116") (pintype "bidirectional"))
    )
    (net (code "263") (name "X_A_HLFB_OUT") (class "Default")
      (node (ref "J13") (pin "5") (pinfunction "5-HLFB-_5") (pintype "passive"))
    )
    (net (code "264") (name "X_A_MI_DIR") (class "Default")
      (node (ref "J13") (pin "7") (pinfunction "7-INPUT_A-_7") (pintype "passive"))
      (node (ref "R41") (pin "1") (pinfunction "1_1") (pintype "passive"))
      (node (ref "U11") (pin "3") (pinfunction "C(3)_3") (pintype "input"))
    )
    (net (code "265") (name "X_A_MI_ENABLE") (class "Default")
      (node (ref "J13") (pin "8") (pinfunction "8-ENABLE-_8") (pintype "passive"))
      (node (ref "R42") (pin "1") (pinfunction "1_1") (pintype "passive"))
      (node (ref "U12") (pin "3") (pinfunction "C(3)_3") (pintype "input"))
    )
    (net (code "266") (name "X_A_MI_STEP") (class "Default")
      (node (ref "J13") (pin "6") (pinfunction "6-INPUT_B-_6") (pintype "passive"))
      (node (ref "R37") (pin "1") (pinfunction "1_1") (pintype "passive"))
      (node (ref "U10") (pin "3") (pinfunction "C(3)_3") (pintype "input"))
    )
    (net (code "267") (name "X_A_STEP") (class "Default")
      (node (ref "R38") (pin "1") (pinfunction "1_1") (pintype "passive"))
      (node (ref "U3") (pin "118") (pinfunction "P6_4_118") (pintype "bidirectional"))
    )
    (net (code "268") (name "X_B_DIR") (class "Default")
      (node (ref "R45") (pin "1") (pinfunction "1_1") (pintype "passive"))
      (node (ref "U3") (pin "120") (pinfunction "P6_2_120") (pintype "bidirectional"))
    )
    (net (code "269") (name "X_B_ENABLE") (class "Default")
      (node (ref "R46") (pin "1") (pinfunction "1_1") (pintype "passive"))
      (node (ref "U3") (pin "119") (pinfunction "P6_3_119") (pintype "bidirectional"))
    )
    (net (code "270") (name "X_B_HLFB_OUT") (class "Default")
      (node (ref "J14") (pin "5") (pinfunction "5-HLFB-_5") (pintype "passive"))
    )
    (net (code "271") (name "X_B_MI_DIR") (class "Default")
      (node (ref "J14") (pin "7") (pinfunction "7-INPUT_A-_7") (pintype "passive"))
      (node (ref "R47") (pin "1") (pinfunction "1_1") (pintype "passive"))
      (node (ref "U14") (pin "3") (pinfunction "C(3)_3") (pintype "input"))
    )
    (net (code "272") (name "X_B_MI_ENABLE") (class "Default")
      (node (ref "J14") (pin "8") (pinfunction "8-ENABLE-_8") (pintype "passive"))
      (node (ref "R48") (pin "1") (pinfunction "1_1") (pintype "passive"))
      (node (ref "U15") (pin "3") (pinfunction "C(3)_3") (pintype "input"))
    )
    (net (code "273") (name "X_B_MI_STEP") (class "Default")
      (node (ref "J14") (pin "6") (pinfunction "6-INPUT_B-_6") (pintype "passive"))
      (node (ref "R43") (pin "1") (pinfunction "1_1") (pintype "passive"))
      (node (ref "U13") (pin "3") (pinfunction "C(3)_3") (pintype "input"))
    )
    (net (code "274") (name "X_B_STEP") (class "Default")
      (node (ref "R44") (pin "1") (pinfunction "1_1") (pintype "passive"))
      (node (ref "U3") (pin "121") (pinfunction "P6_1_121") (pintype "bidirectional"))
    )
    (net (code "275") (name "Y_A_DIR") (class "Default")
      (node (ref "R63") (pin "1") (pinfunction "1_1") (pintype "passive"))
      (node (ref "U3") (pin "114") (pinfunction "PA_0_114") (pintype "bidirectional"))
    )
    (net (code "276") (name "Y_A_ENABLE") (class "Default")
      (node (ref "R64") (pin "1") (pinfunction "1_1") (pintype "passive"))
      (node (ref "U3") (pin "113") (pinfunction "PA_1_113") (pintype "bidirectional"))
    )
    (net (code "277") (name "Y_A_HLFB_OUT") (class "Default")
      (node (ref "J17") (pin "5") (pinfunction "5-HLFB-_5") (pintype "passive"))
    )
    (net (code "278") (name "Y_A_MI_DIR") (class "Default")
      (node (ref "J17") (pin "7") (pinfunction "7-INPUT_A-_7") (pintype "passive"))
      (node (ref "R65") (pin "1") (pinfunction "1_1") (pintype "passive"))
      (node (ref "U23") (pin "3") (pinfunction "C(3)_3") (pintype "input"))
    )
    (net (code "279") (name "Y_A_MI_ENABLE") (class "Default")
      (node (ref "J17") (pin "8") (pinfunction "8-ENABLE-_8") (pintype "passive"))
      (node (ref "R66") (pin "1") (pinfunction "1_1") (pintype "passive"))
      (node (ref "U24") (pin "3") (pinfunction "C(3)_3") (pintype "input"))
    )
    (net (code "280") (name "Y_A_MI_STEP") (class "Default")
      (node (ref "J17") (pin "6") (pinfunction "6-INPUT_B-_6") (pintype "passive"))
      (node (ref "R61") (pin "1") (pinfunction "1_1") (pintype "passive"))
      (node (ref "U22") (pin "3") (pinfunction "C(3)_3") (pintype "input"))
    )
    (net (code "281") (name "Y_A_STEP") (class "Default")
      (node (ref "R62") (pin "1") (pinfunction "1_1") (pintype "passive"))
      (node (ref "U3") (pin "115") (pinfunction "P6_7_115") (pintype "bidirectional"))
    )
    (net (code "282") (name "Y_B_DIR") (class "Default")
      (node (ref "R69") (pin "1") (pinfunction "1_1") (pintype "passive"))
      (node (ref "U3") (pin "108") (pinfunction "PA_9_108") (pintype "bidirectional"))
    )
    (net (code "283") (name "Y_B_ENABLE") (class "Default")
      (node (ref "R70") (pin "1") (pinfunction "1_1") (pintype "passive"))
      (node (ref "U3") (pin "107") (pinfunction "PA_8_107") (pintype "bidirectional"))
    )
    (net (code "284") (name "Y_B_HLFB_OUT") (class "Default")
      (node (ref "J18") (pin "5") (pinfunction "5-HLFB-_5") (pintype "passive"))
    )
    (net (code "285") (name "Y_B_MI_DIR") (class "Default")
      (node (ref "J18") (pin "7") (pinfunction "7-INPUT_A-_7") (pintype "passive"))
      (node (ref "R71") (pin "1") (pinfunction "1_1") (pintype "passive"))
      (node (ref "U26") (pin "3") (pinfunction "C(3)_3") (pintype "input"))
    )
    (net (code "286") (name "Y_B_MI_ENABLE") (class "Default")
      (node (ref "J18") (pin "8") (pinfunction "8-ENABLE-_8") (pintype "passive"))
      (node (ref "R72") (pin "1") (pinfunction "1_1") (pintype "passive"))
      (node (ref "U27") (pin "3") (pinfunction "C(3)_3") (pintype "input"))
    )
    (net (code "287") (name "Y_B_MI_STEP") (class "Default")
      (node (ref "J18") (pin "6") (pinfunction "6-INPUT_B-_6") (pintype "passive"))
      (node (ref "R67") (pin "1") (pinfunction "1_1") (pintype "passive"))
      (node (ref "U25") (pin "3") (pinfunction "C(3)_3") (pintype "input"))
    )
    (net (code "288") (name "Y_B_STEP") (class "Default")
      (node (ref "R68") (pin "1") (pinfunction "1_1") (pintype "passive"))
      (node (ref "U3") (pin "109") (pinfunction "PA_10_109") (pintype "bidirectional"))
    )
    (net (code "289") (name "Z_A_DIR") (class "Default")
      (node (ref "R87") (pin "1") (pinfunction "1_1") (pintype "passive"))
      (node (ref "U3") (pin "105") (pinfunction "P6_14_105") (pintype "bidirectional"))
    )
    (net (code "290") (name "Z_A_ENABLE") (class "Default")
      (node (ref "R88") (pin "1") (pinfunction "1_1") (pintype "passive"))
      (node (ref "U3") (pin "104") (pinfunction "P6_13_104") (pintype "bidirectional"))
    )
    (net (code "291") (name "Z_A_HLFB_OUT") (class "Default")
      (node (ref "J21") (pin "5") (pinfunction "5-HLFB-_5") (pintype "passive"))
    )
    (net (code "292") (name "Z_A_MI_DIR") (class "Default")
      (node (ref "J21") (pin "7") (pinfunction "7-INPUT_A-_7") (pintype "passive"))
      (node (ref "R89") (pin "1") (pinfunction "1_1") (pintype "passive"))
      (node (ref "U35") (pin "3") (pinfunction "C(3)_3") (pintype "input"))
    )
    (net (code "293") (name "Z_A_MI_ENABLE") (class "Default")
      (node (ref "J21") (pin "8") (pinfunction "8-ENABLE-_8") (pintype "passive"))
      (node (ref "R90") (pin "1") (pinfunction "1_1") (pintype "passive"))
      (node (ref "U36") (pin "3") (pinfunction "C(3)_3") (pintype "input"))
    )
    (net (code "294") (name "Z_A_MI_STEP") (class "Default")
      (node (ref "J21") (pin "6") (pinfunction "6-INPUT_B-_6") (pintype "passive"))
      (node (ref "R85") (pin "1") (pinfunction "1_1") (pintype "passive"))
      (node (ref "U34") (pin "3") (pinfunction "C(3)_3") (pintype "input"))
    )
    (net (code "295") (name "Z_A_STEP") (class "Default")
      (node (ref "R86") (pin "1") (pinfunction "1_1") (pintype "passive"))
      (node (ref "U3") (pin "106") (pinfunction "P6_15_106") (pintype "bidirectional"))
    )
    (net (code "296") (name "Z_B_DIR") (class "Default")
      (node (ref "R93") (pin "1") (pinfunction "1_1") (pintype "passive"))
      (node (ref "U3") (pin "102") (pinfunction "P6_11_102") (pintype "bidirectional"))
    )
    (net (code "297") (name "Z_B_ENABLE") (class "Default")
      (node (ref "R94") (pin "1") (pinfunction "1_1") (pintype "passive"))
      (node (ref "U3") (pin "101") (pinfunction "P6_10_101") (pintype "bidirectional"))
    )
    (net (code "298") (name "Z_B_HLFB_OUT") (class "Default")
      (node (ref "J22") (pin "5") (pinfunction "5-HLFB-_5") (pintype "passive"))
    )
    (net (code "299") (name "Z_B_MI_DIR") (class "Default")
      (node (ref "J22") (pin "7") (pinfunction "7-INPUT_A-_7") (pintype "passive"))
      (node (ref "R95") (pin "1") (pinfunction "1_1") (pintype "passive"))
      (node (ref "U38") (pin "3") (pinfunction "C(3)_3") (pintype "input"))
    )
    (net (code "300") (name "Z_B_MI_ENABLE") (class "Default")
      (node (ref "J22") (pin "8") (pinfunction "8-ENABLE-_8") (pintype "passive"))
      (node (ref "R96") (pin "1") (pinfunction "1_1") (pintype "passive"))
      (node (ref "U39") (pin "3") (pinfunction "C(3)_3") (pintype "input"))
    )
    (net (code "301") (name "Z_B_MI_STEP") (class "Default")
      (node (ref "J22") (pin "6") (pinfunction "6-INPUT_B-_6") (pintype "passive"))
      (node (ref "R91") (pin "1") (pinfunction "1_1") (pintype "passive"))
      (node (ref "U37") (pin "3") (pinfunction "C(3)_3") (pintype "input"))
    )
    (net (code "302") (name "Z_B_STEP") (class "Default")
      (node (ref "R92") (pin "1") (pinfunction "1_1") (pintype "passive"))
      (node (ref "U3") (pin "103") (pinfunction "P6_12_103") (pintype "bidirectional"))
    )
    (net (code "303") (name "unconnected-(U3-VBAT-Pad18)") (class "Default")
      (node (ref "U3") (pin "18") (pinfunction "VBAT_18") (pintype "bidirectional"))
    )
  )
)
